# elk-board.net
KiCad netlist of a schematic drawn in EAGLE
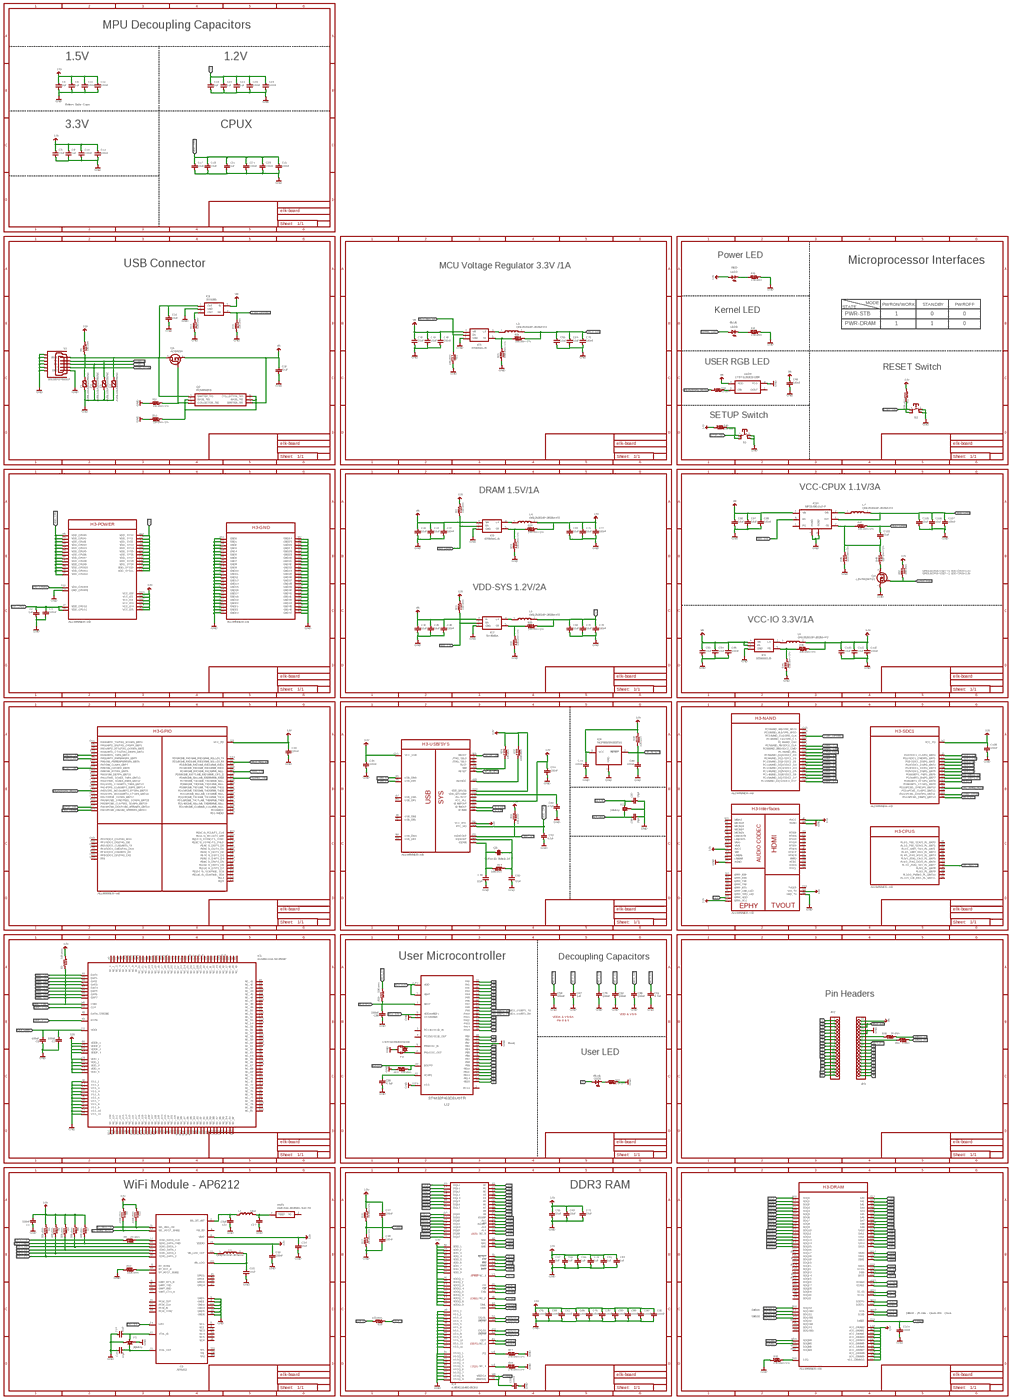
[diagram p0: schematic, sheet 1, overview]
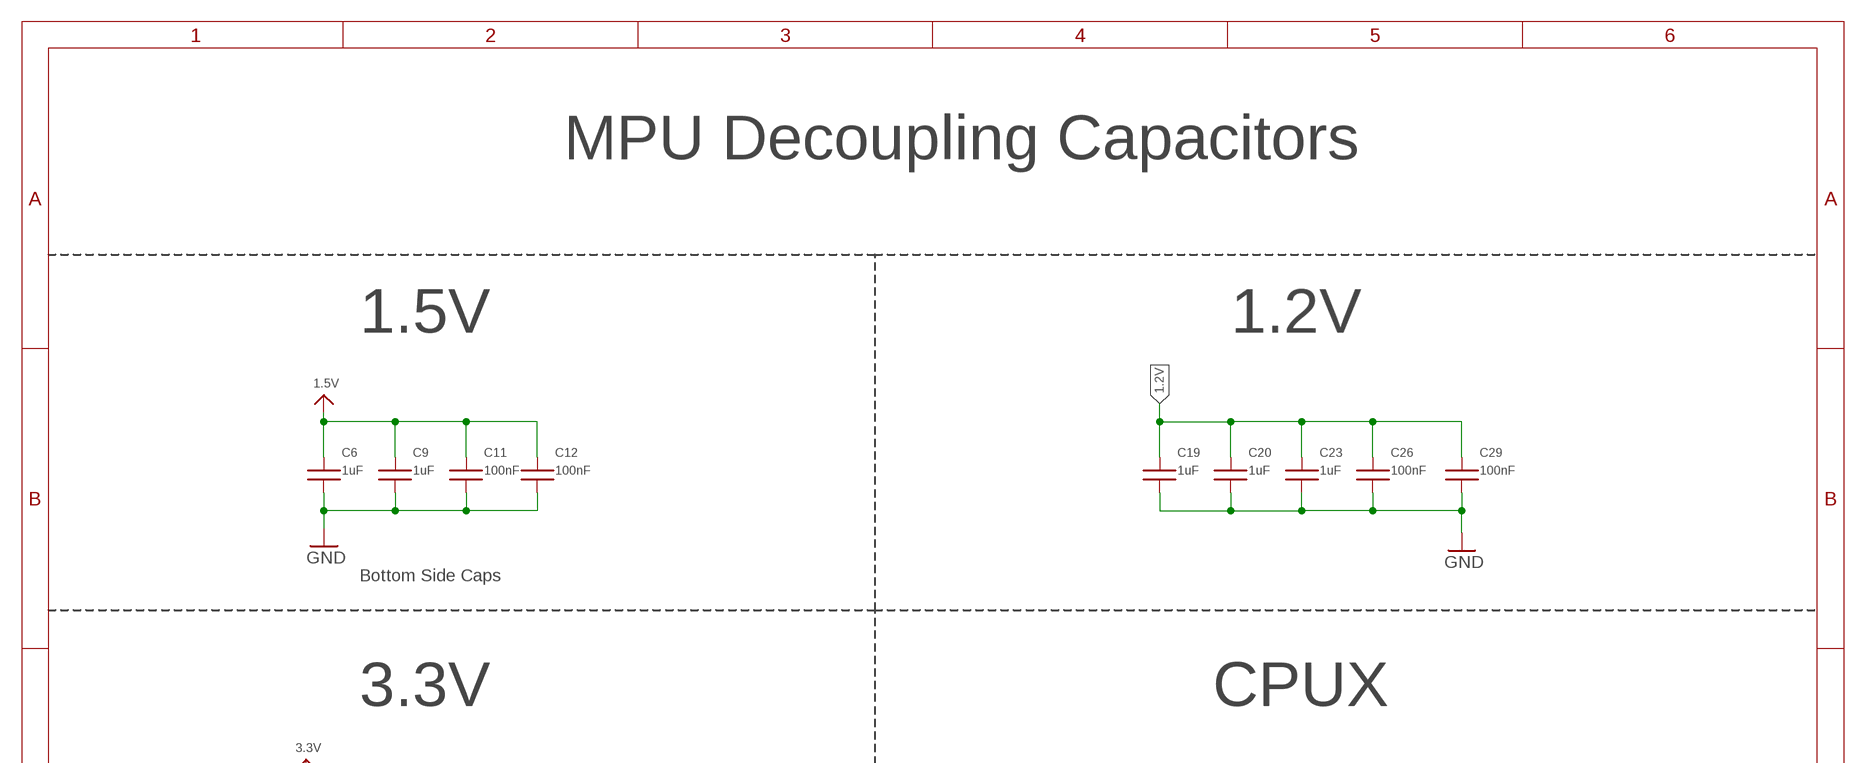
[diagram p1: schematic, sheet 1, part 1 of 7]
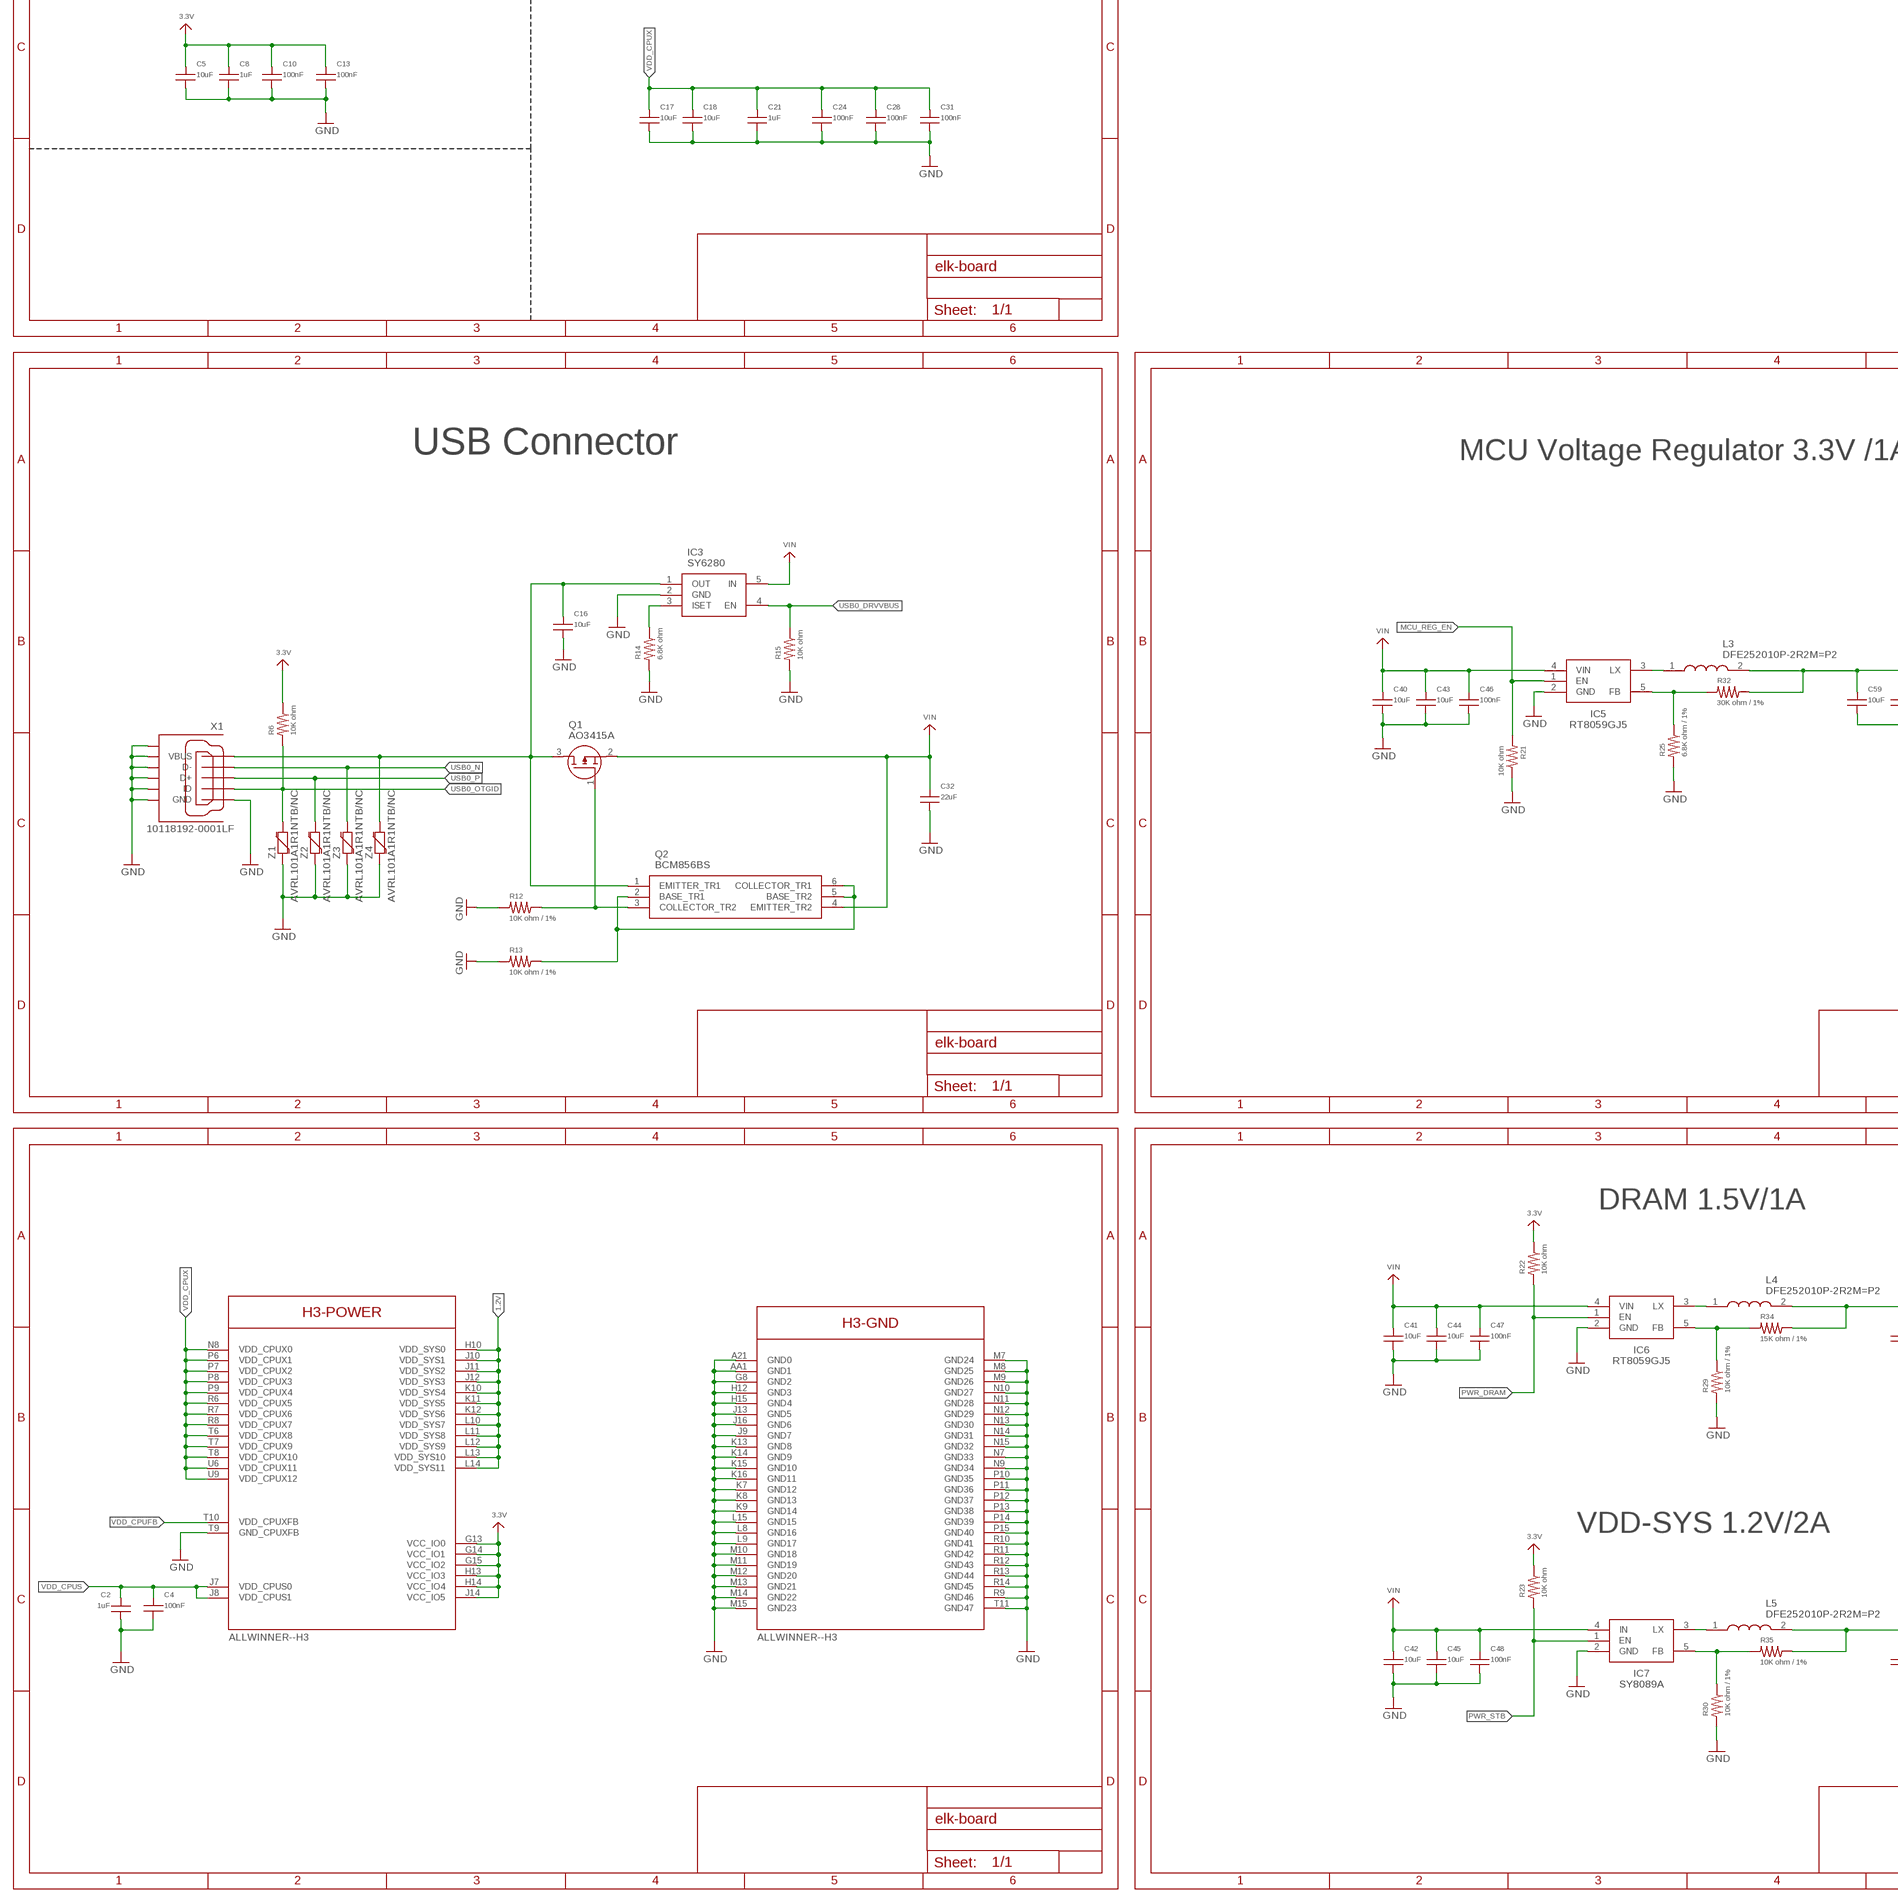
[diagram p2: schematic, sheet 1, part 2 of 7]
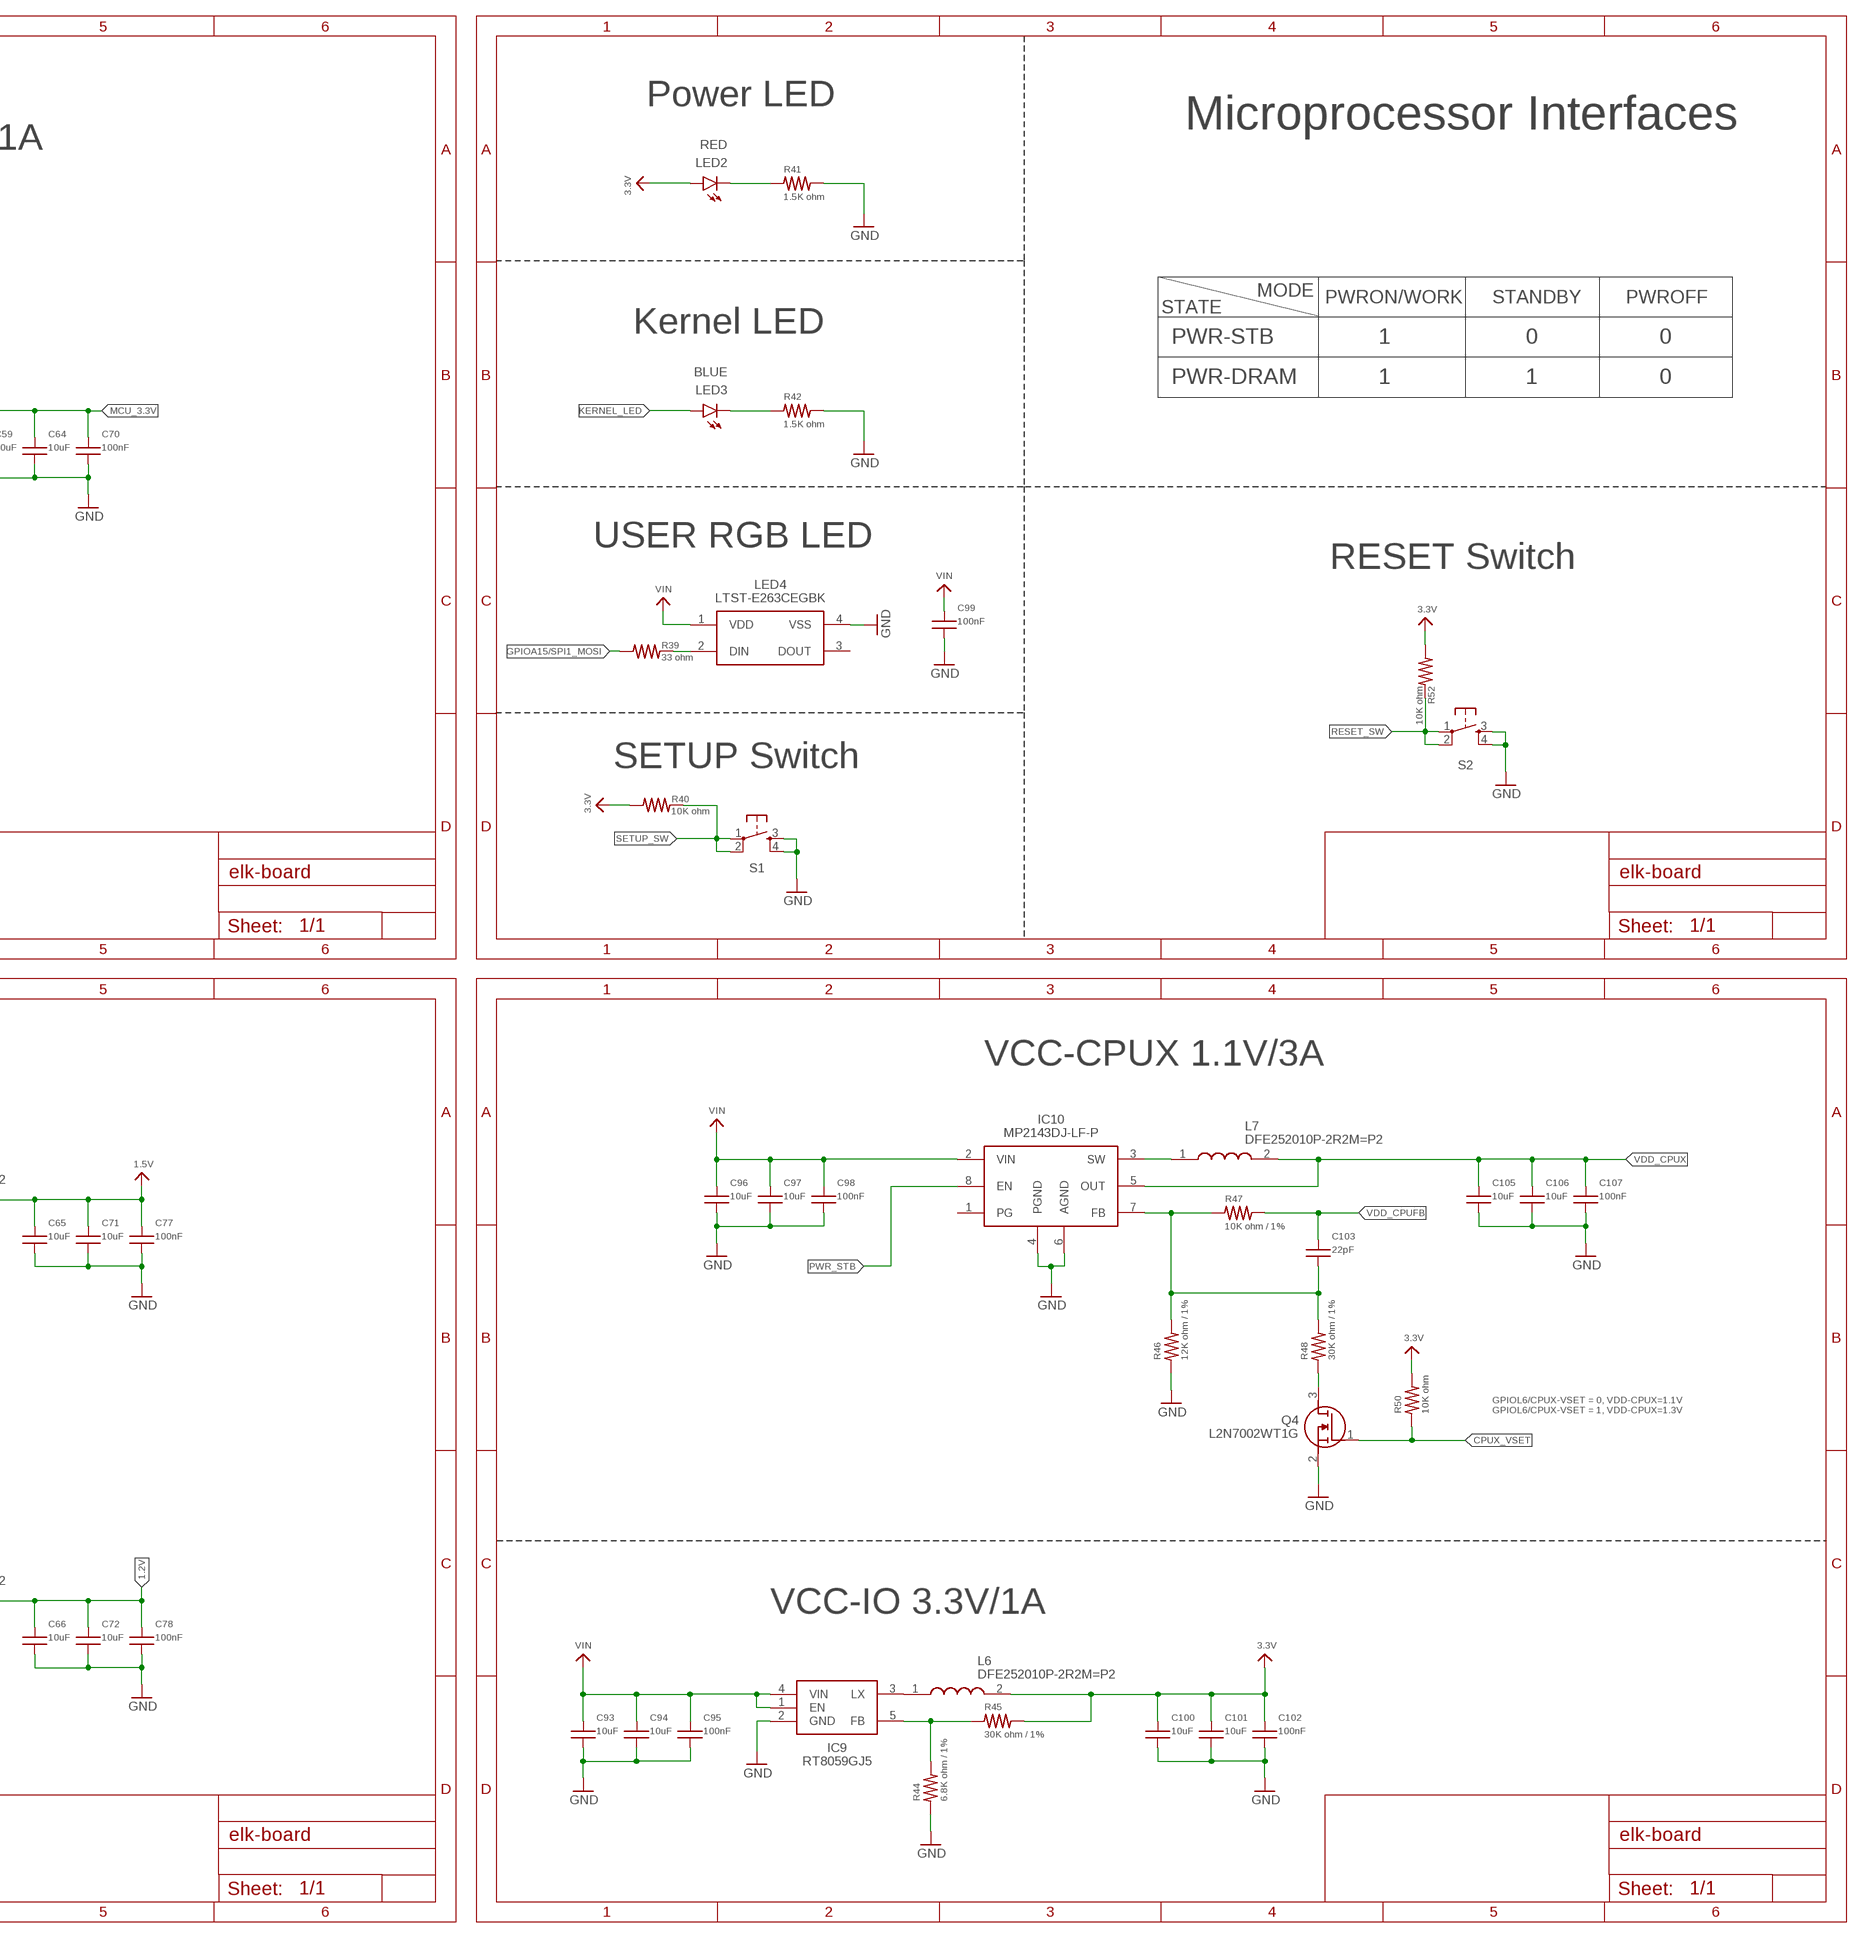
[diagram p3: schematic, sheet 1, part 3 of 7]
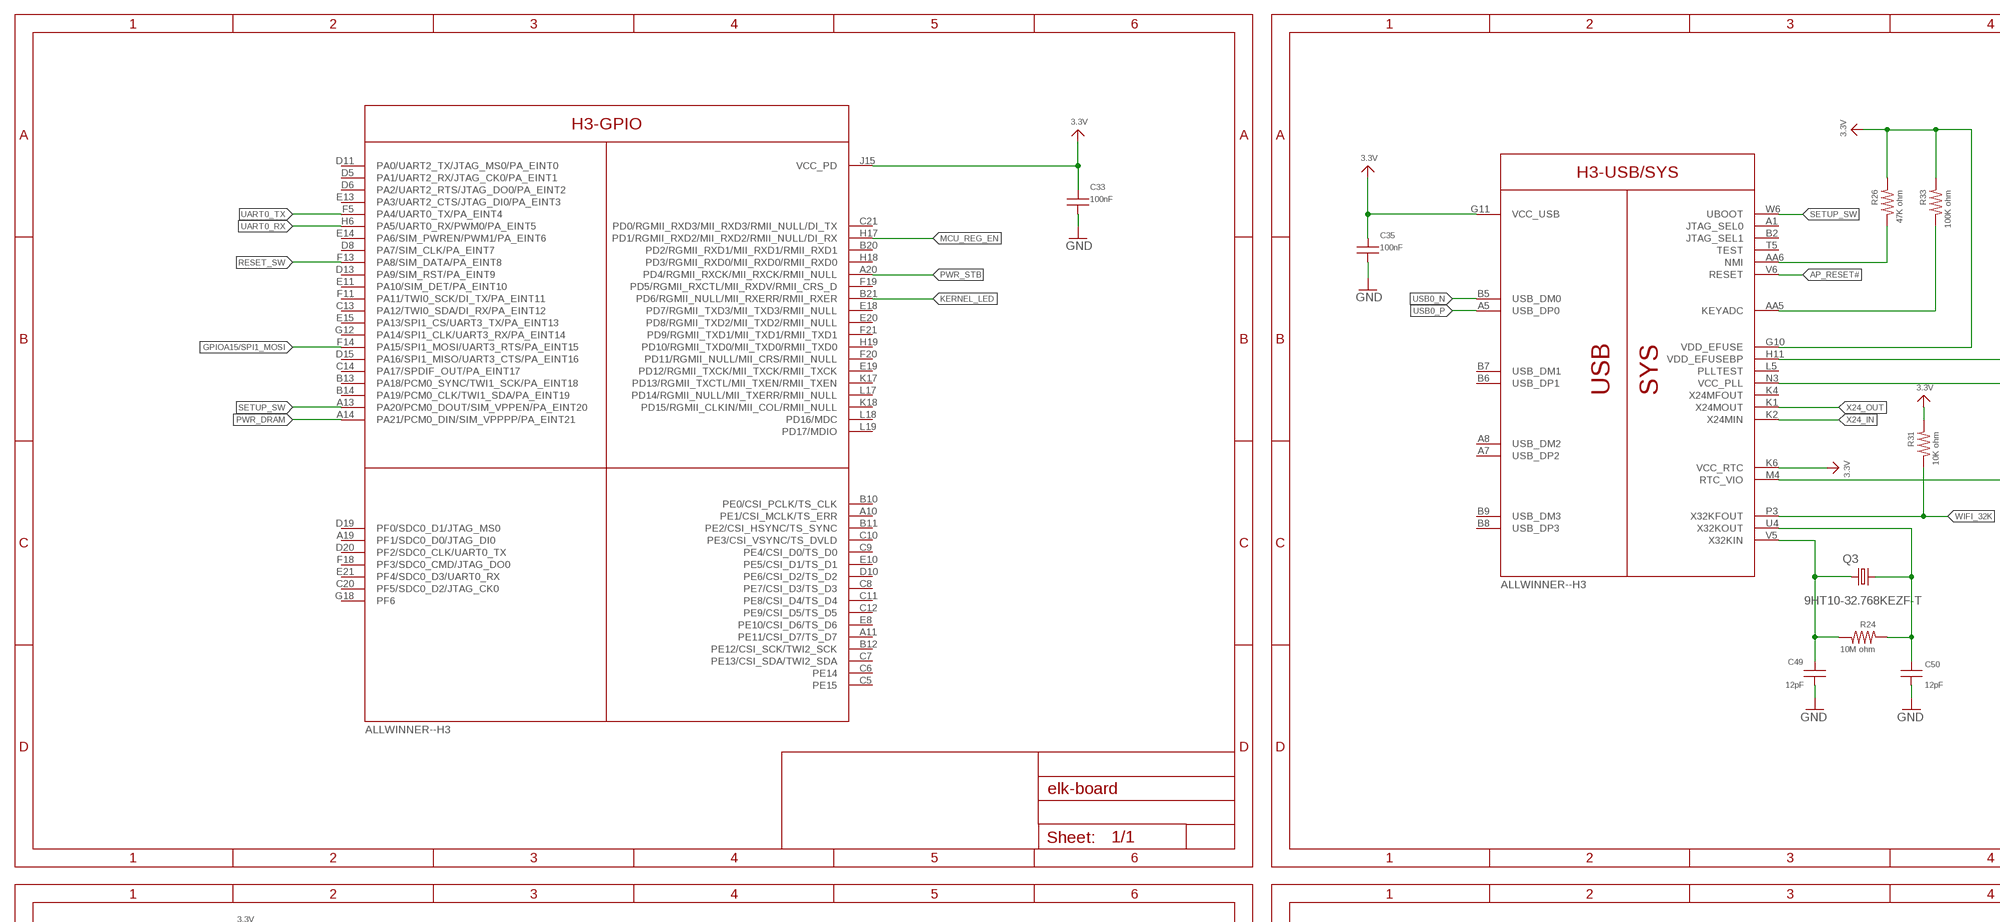
[diagram p4: schematic, sheet 1, part 4 of 7]
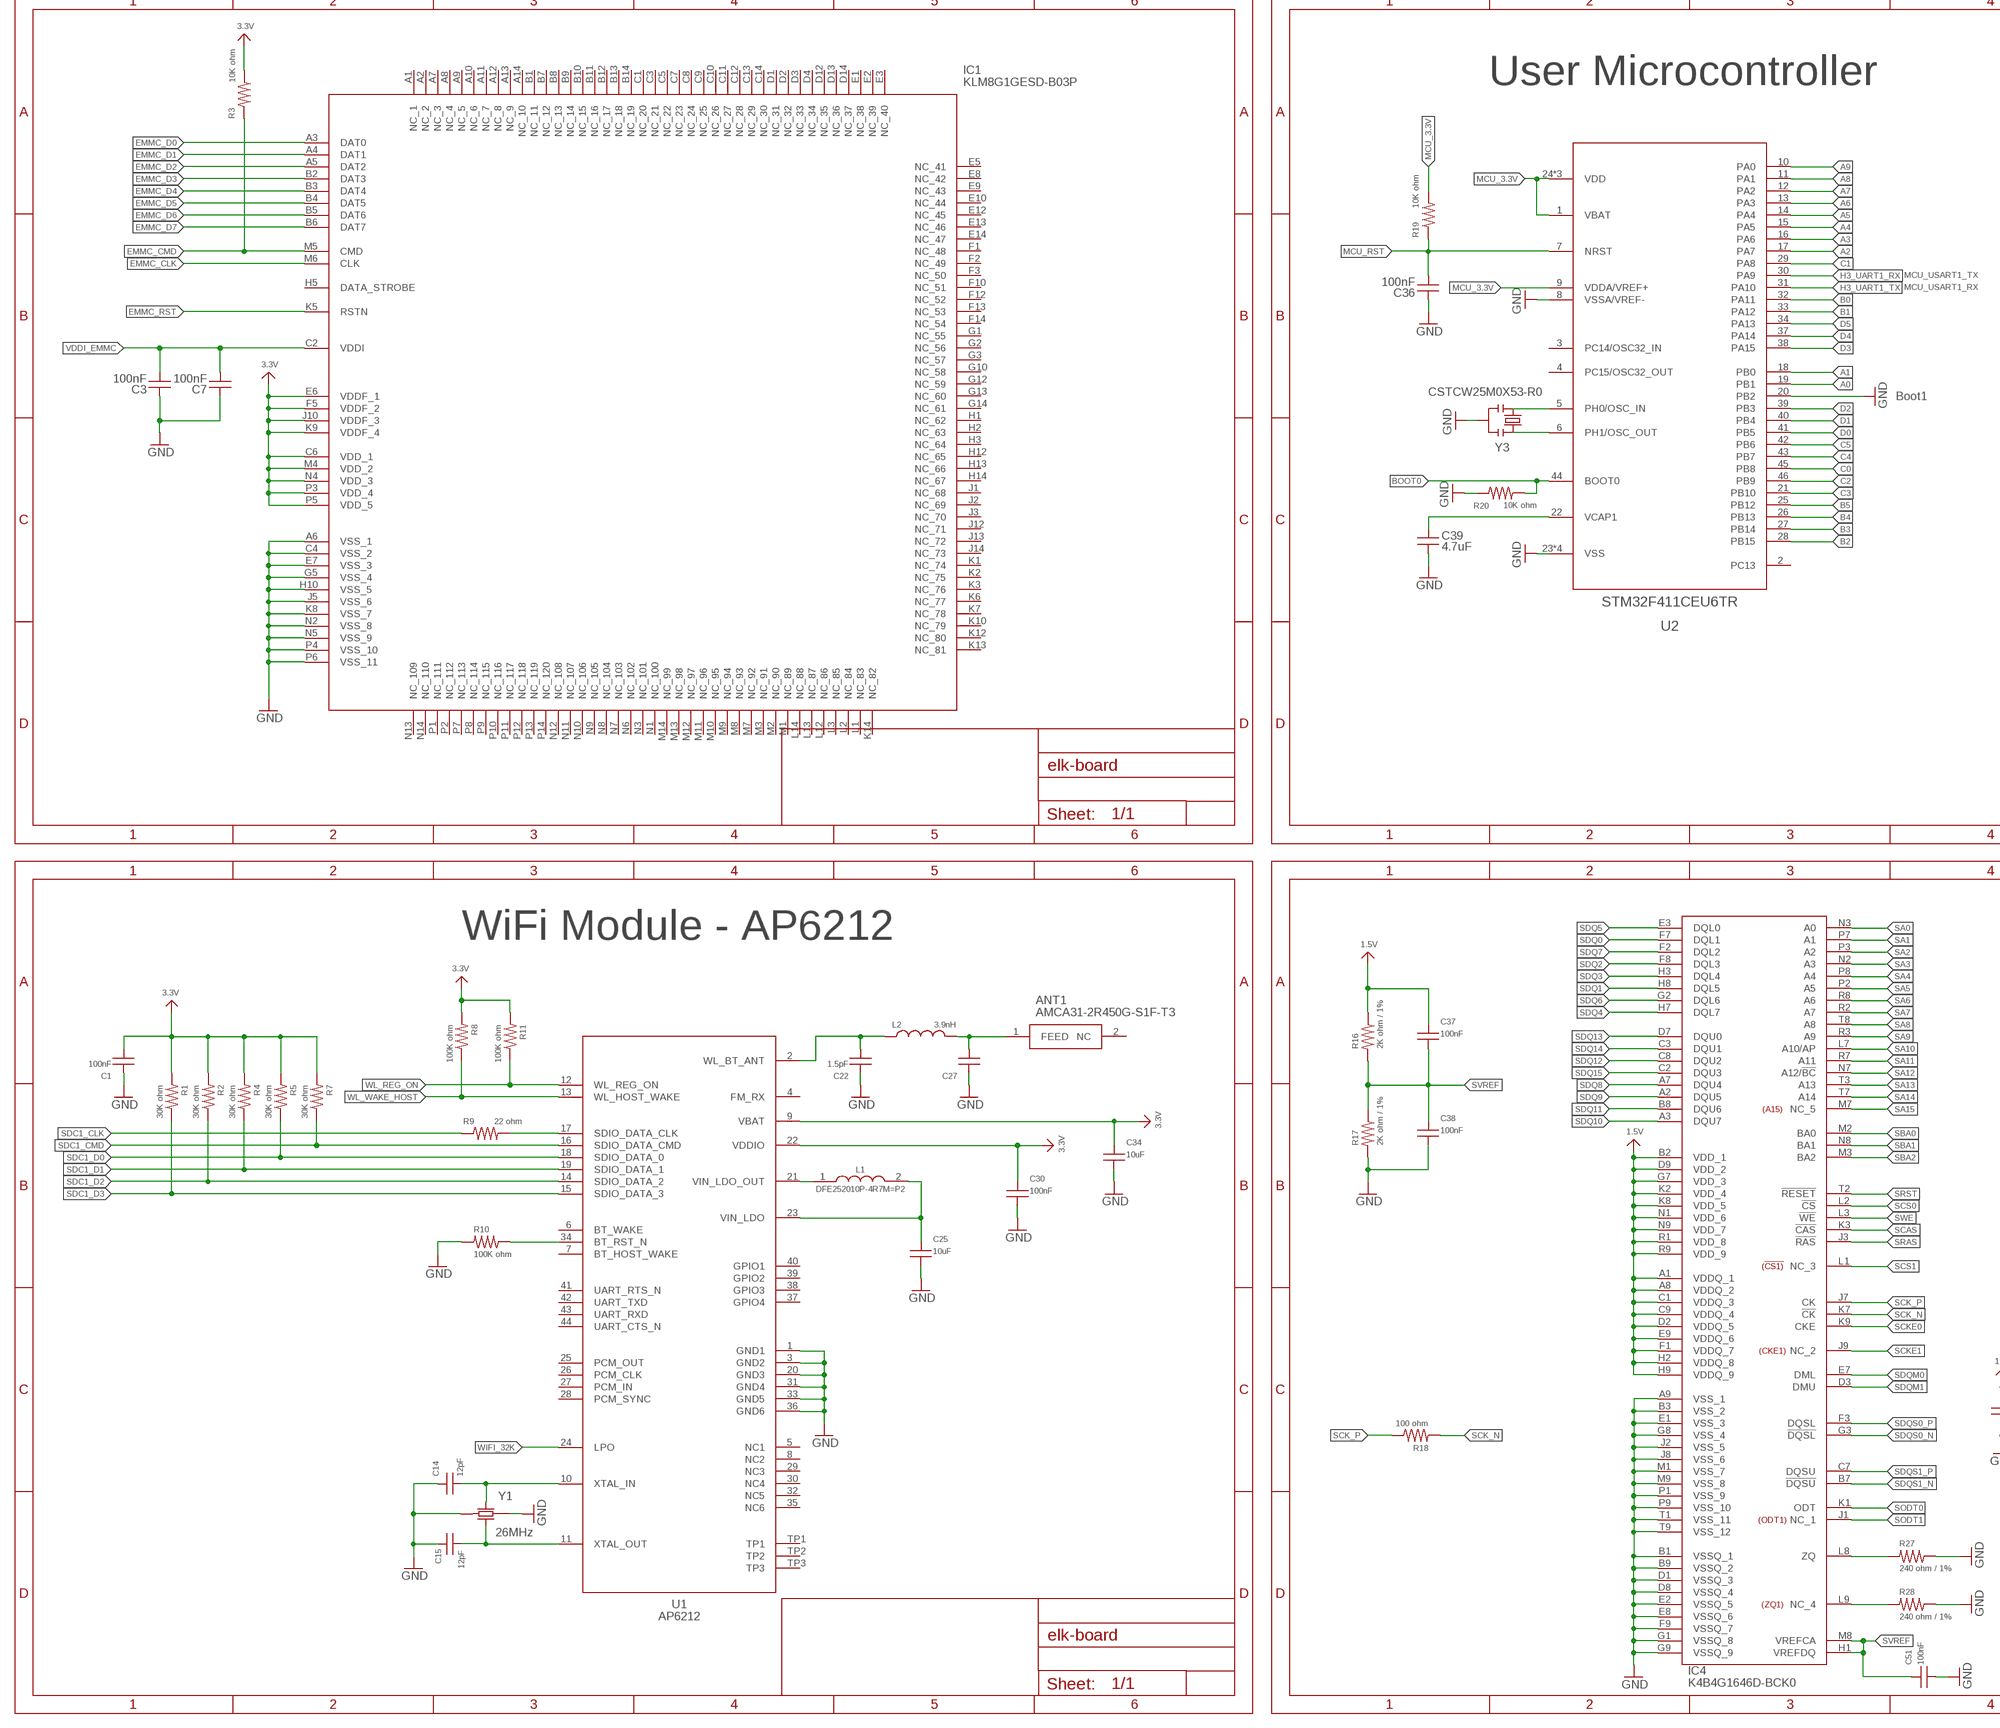
[diagram p5: schematic, sheet 1, part 5 of 7]
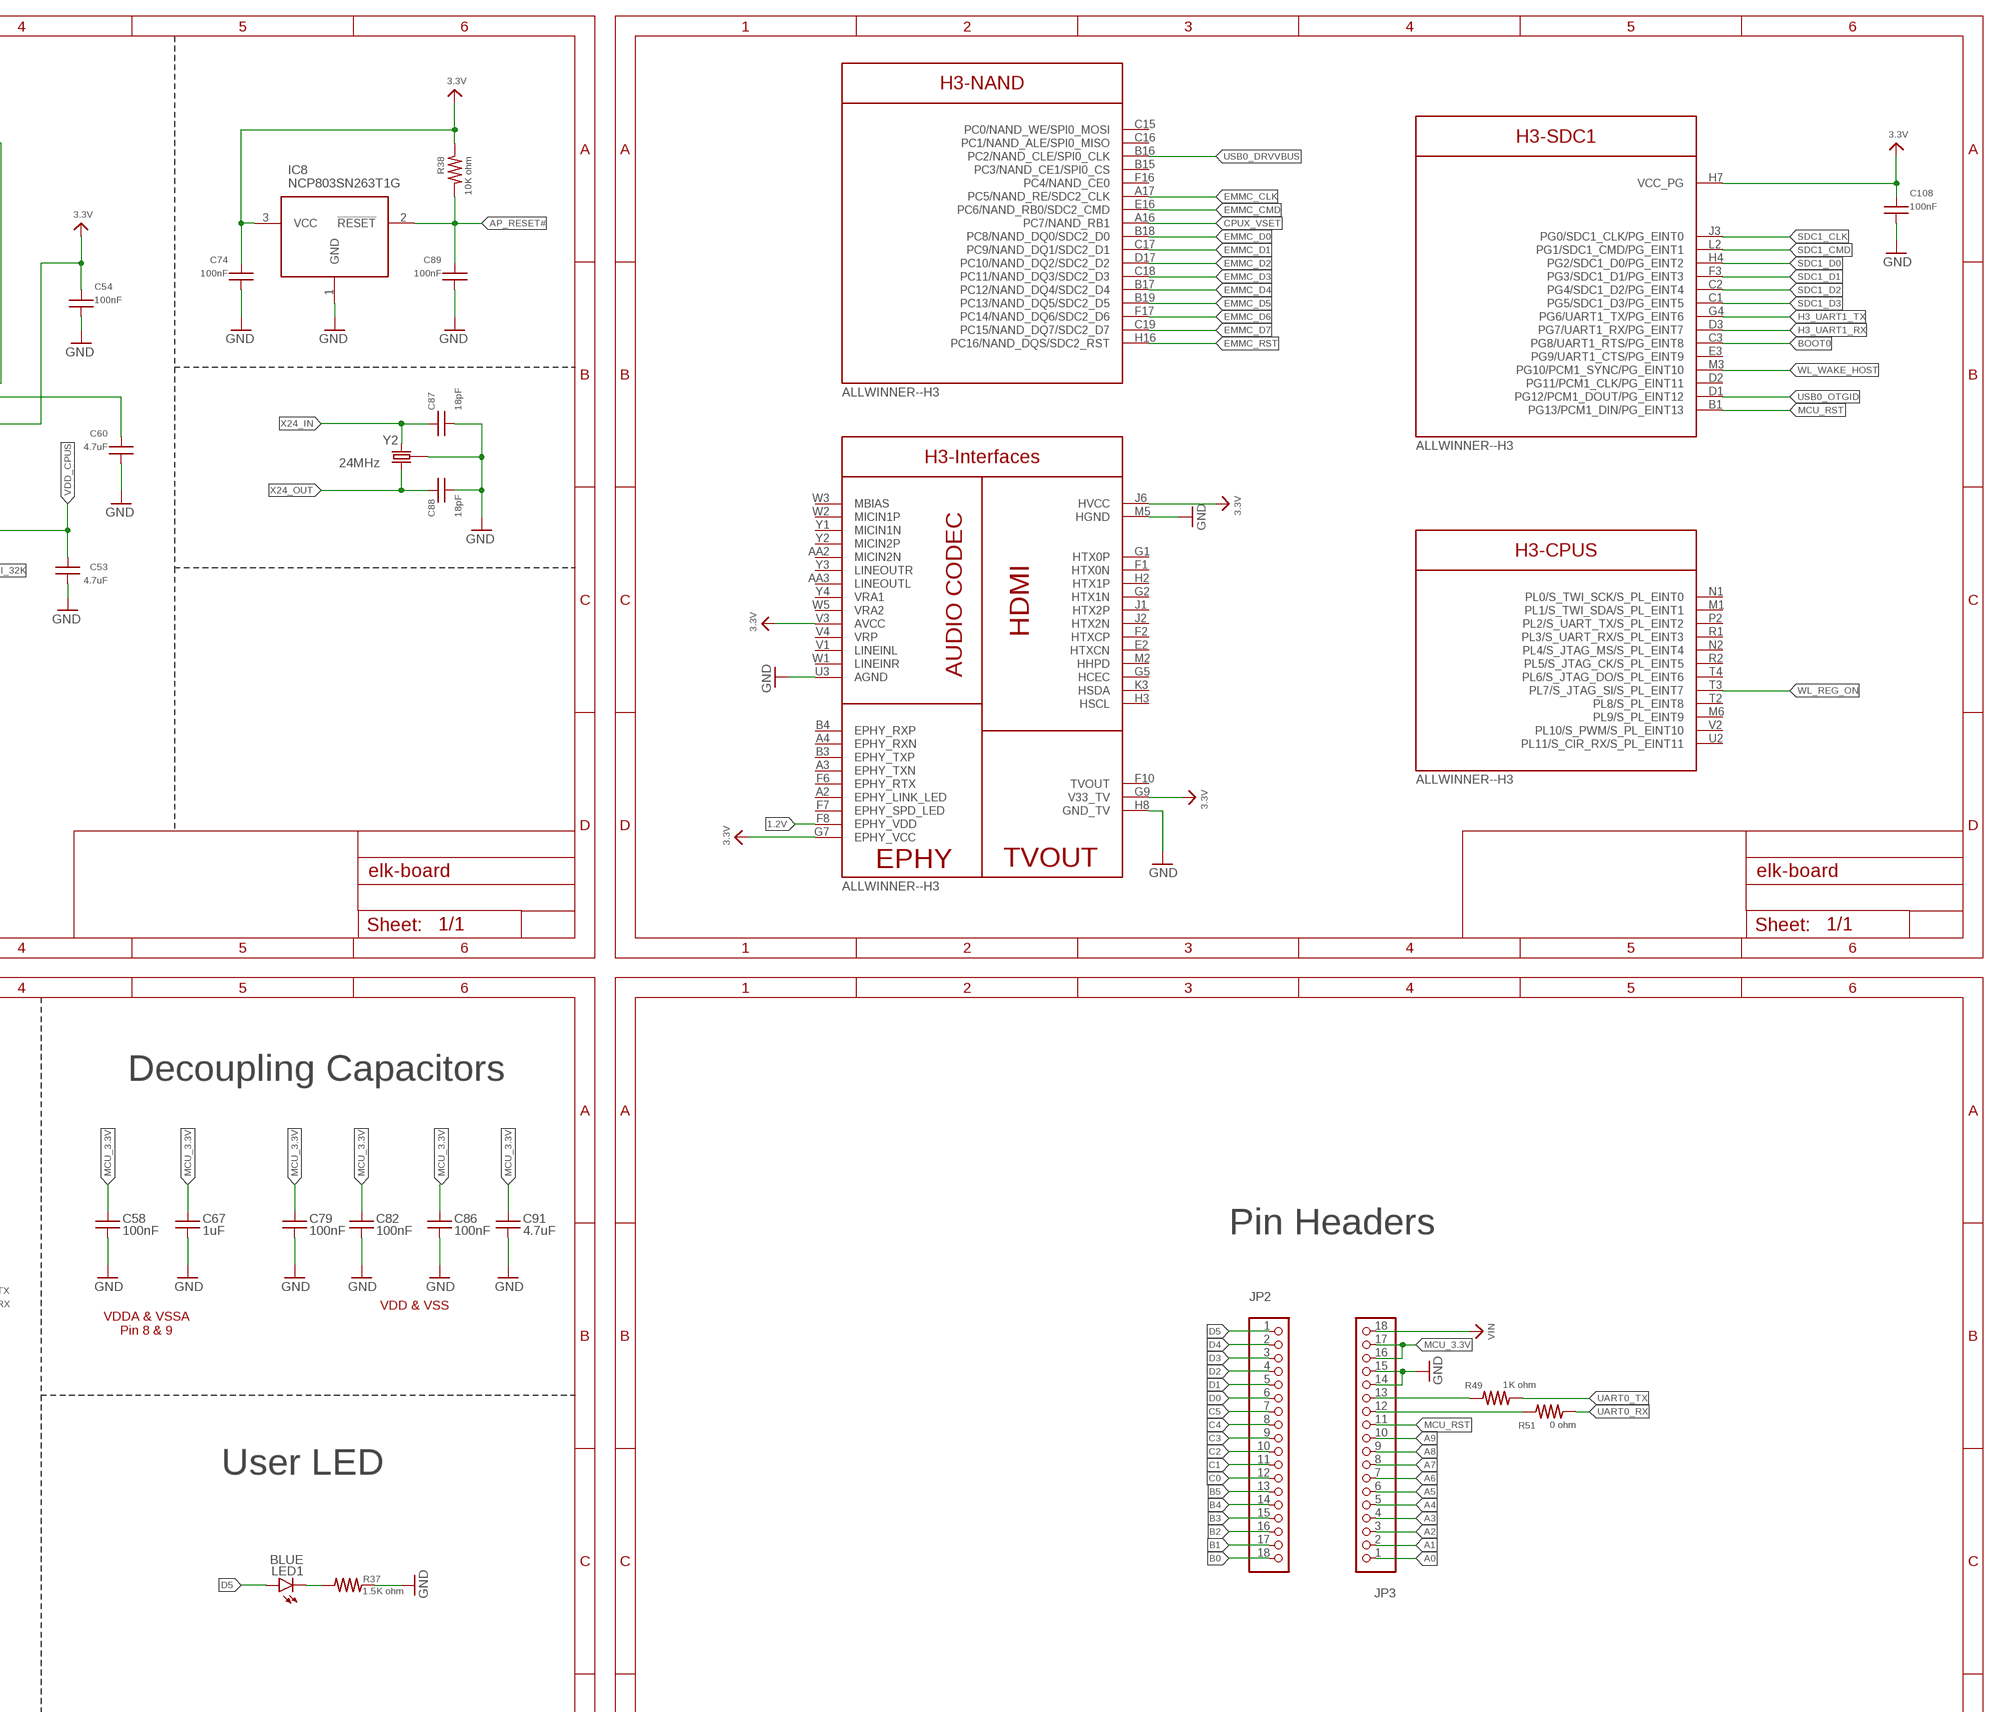
[diagram p6: schematic, sheet 1, part 6 of 7]
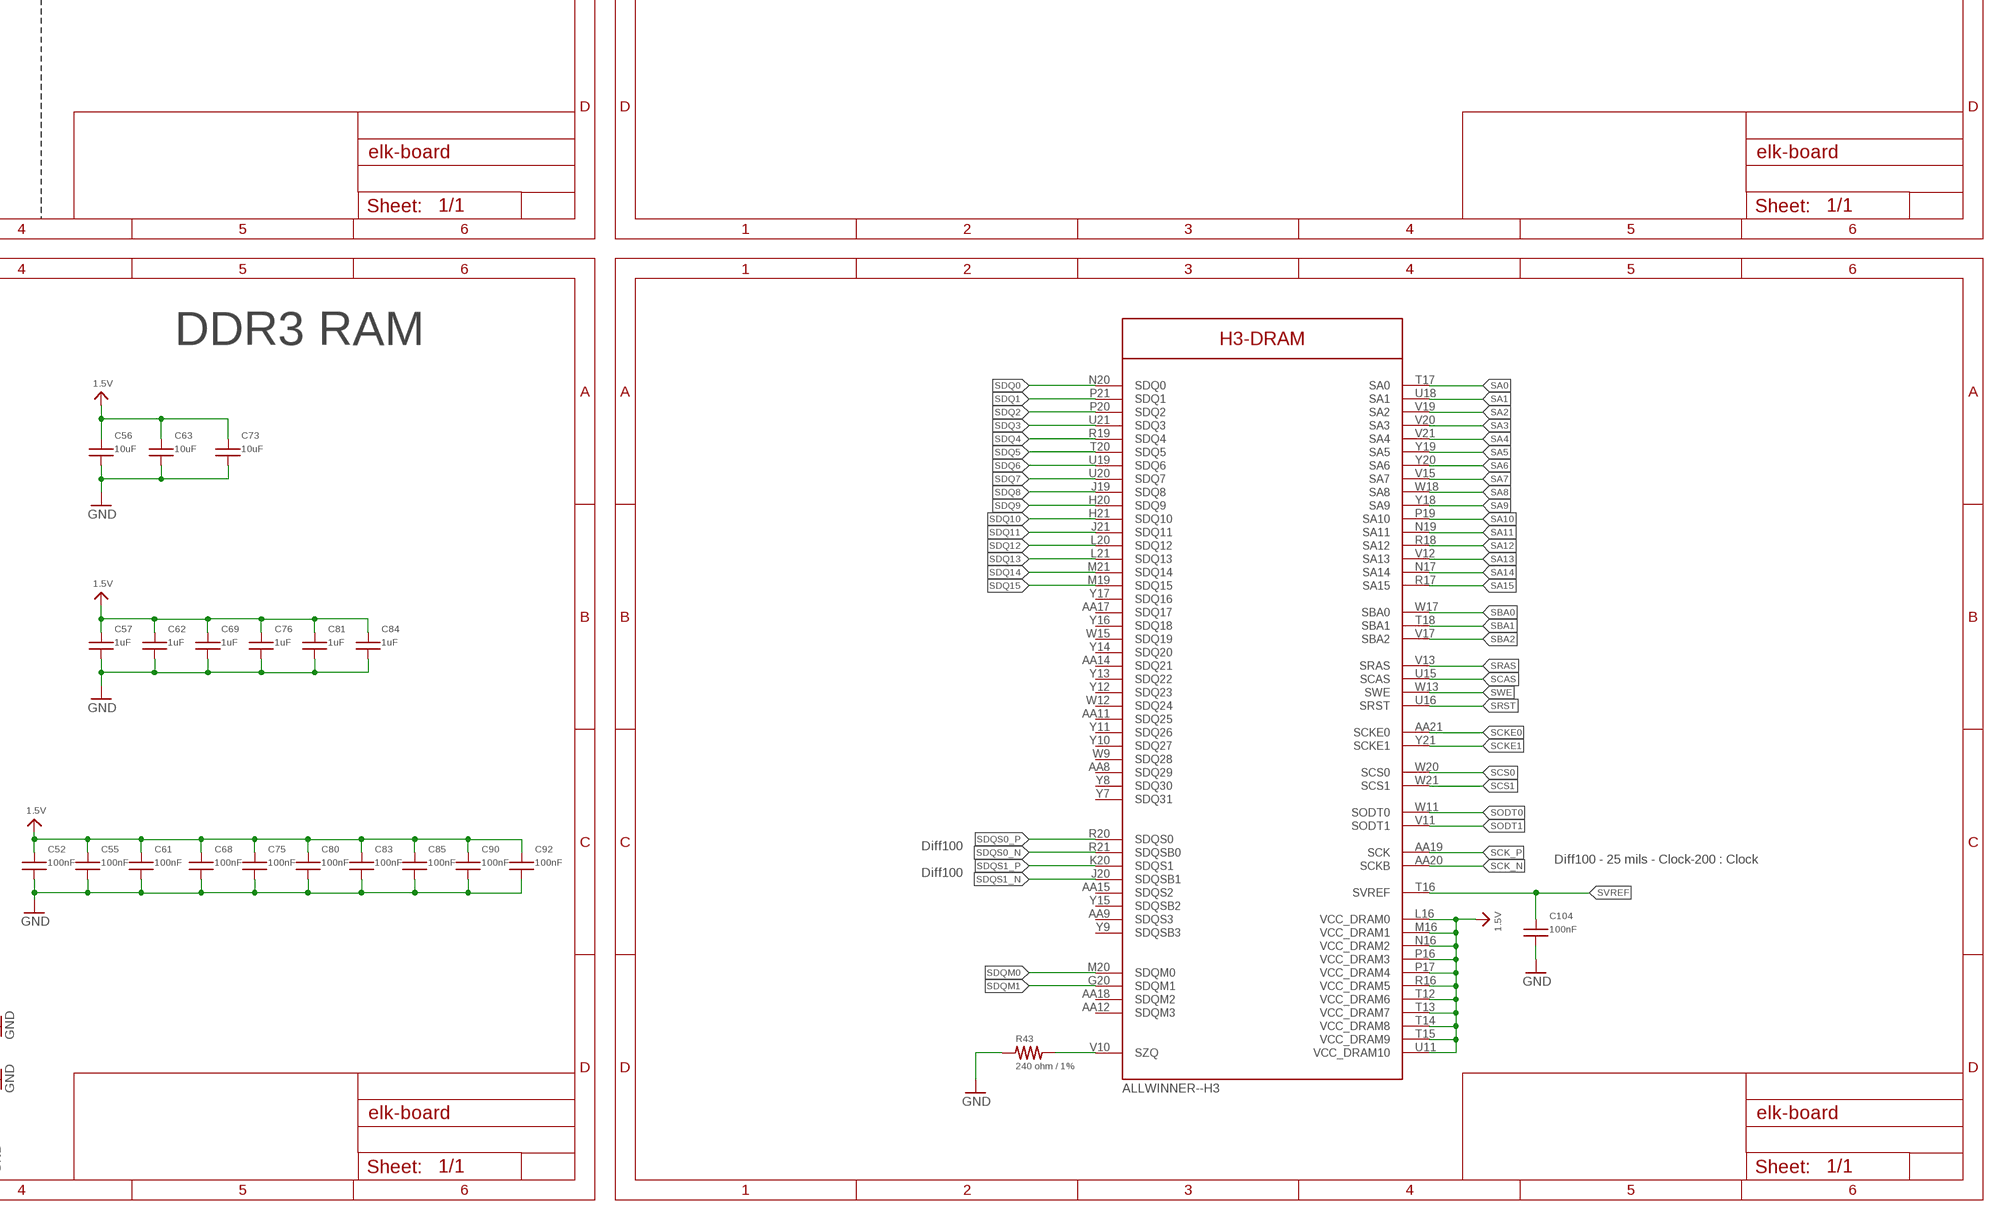
[diagram p7: schematic, sheet 1, part 7 of 7]

(export (version "E")
  (design (tool "Eeschema 10.0.6"))
  (components
    (comp (ref "ANT1")
      (value "AMCA31-2R450G-S1F-T3")
      (footprint "eagle-import:ANTC3216X140N")
      (fields (field (name "MOUSER_PART_NUMBER") "815-CA312R450GS1FT3"))
      (libsource (lib "eagle-import") (part "AMCA31-2R450G-S1F-T3"))
    )
    (comp (ref "C1")
      (value "100nF")
      (footprint "eagle-import:0402")
      (libsource (lib "eagle-import") (part "CAPACITOR-(INCH)-0402"))
    )
    (comp (ref "C2")
      (value "1uF")
      (footprint "eagle-import:0402")
      (libsource (lib "eagle-import") (part "CAPACITOR-(INCH)-0402"))
    )
    (comp (ref "C3")
      (value "100nF")
      (footprint "eagle-import:0402")
      (libsource (lib "eagle-import") (part "CAPACITOR-(INCH)-0402"))
    )
    (comp (ref "C4")
      (value "100nF")
      (footprint "eagle-import:0402")
      (libsource (lib "eagle-import") (part "CAPACITOR-(INCH)-0402"))
    )
    (comp (ref "C5")
      (value "10uF")
      (footprint "eagle-import:0603")
      (libsource (lib "eagle-import") (part "CAPACITOR-(INCH)-0603"))
    )
    (comp (ref "C6")
      (value "1uF")
      (footprint "eagle-import:0402")
      (libsource (lib "eagle-import") (part "CAPACITOR-(INCH)-0402"))
    )
    (comp (ref "C7")
      (value "100nF")
      (footprint "eagle-import:0402")
      (libsource (lib "eagle-import") (part "CAPACITOR-(INCH)-0402"))
    )
    (comp (ref "C8")
      (value "1uF")
      (footprint "eagle-import:0402")
      (libsource (lib "eagle-import") (part "CAPACITOR-(INCH)-0402"))
    )
    (comp (ref "C9")
      (value "1uF")
      (footprint "eagle-import:0402")
      (libsource (lib "eagle-import") (part "CAPACITOR-(INCH)-0402"))
    )
    (comp (ref "C10")
      (value "100nF")
      (footprint "eagle-import:0402")
      (libsource (lib "eagle-import") (part "CAPACITOR-(INCH)-0402"))
    )
    (comp (ref "C11")
      (value "100nF")
      (footprint "eagle-import:0402")
      (libsource (lib "eagle-import") (part "CAPACITOR-(INCH)-0402"))
    )
    (comp (ref "C12")
      (value "100nF")
      (footprint "eagle-import:0402")
      (libsource (lib "eagle-import") (part "CAPACITOR-(INCH)-0402"))
    )
    (comp (ref "C13")
      (value "100nF")
      (footprint "eagle-import:0402")
      (libsource (lib "eagle-import") (part "CAPACITOR-(INCH)-0402"))
    )
    (comp (ref "C14")
      (value "12pF")
      (footprint "eagle-import:0402")
      (libsource (lib "eagle-import") (part "CAPACITOR-(INCH)-0402"))
    )
    (comp (ref "C15")
      (value "12pF")
      (footprint "eagle-import:0402")
      (libsource (lib "eagle-import") (part "CAPACITOR-(INCH)-0402"))
    )
    (comp (ref "C16")
      (value "10uF")
      (footprint "eagle-import:0603")
      (libsource (lib "eagle-import") (part "CAPACITOR-(INCH)-0603"))
    )
    (comp (ref "C17")
      (value "10uF")
      (footprint "eagle-import:TOLBA_0603")
      (libsource (lib "eagle-import") (part "TOLBA_CAP"))
    )
    (comp (ref "C18")
      (value "10uF")
      (footprint "eagle-import:TOLBA_0603")
      (libsource (lib "eagle-import") (part "TOLBA_CAP"))
    )
    (comp (ref "C19")
      (value "1uF")
      (footprint "eagle-import:0402")
      (libsource (lib "eagle-import") (part "CAPACITOR-(INCH)-0402"))
    )
    (comp (ref "C20")
      (value "1uF")
      (footprint "eagle-import:0402")
      (libsource (lib "eagle-import") (part "CAPACITOR-(INCH)-0402"))
    )
    (comp (ref "C21")
      (value "1uF")
      (footprint "eagle-import:0402")
      (libsource (lib "eagle-import") (part "CAPACITOR-(INCH)-0402"))
    )
    (comp (ref "C22")
      (value "1.5pF")
      (footprint "eagle-import:0402")
      (libsource (lib "eagle-import") (part "CAPACITOR-(INCH)-0402"))
    )
    (comp (ref "C23")
      (value "1uF")
      (footprint "eagle-import:0402")
      (libsource (lib "eagle-import") (part "CAPACITOR-(INCH)-0402"))
    )
    (comp (ref "C24")
      (value "100nF")
      (footprint "eagle-import:0402")
      (libsource (lib "eagle-import") (part "CAPACITOR-(INCH)-0402"))
    )
    (comp (ref "C25")
      (value "10uF")
      (footprint "eagle-import:0603")
      (libsource (lib "eagle-import") (part "CAPACITOR-(INCH)-0603"))
    )
    (comp (ref "C26")
      (value "100nF")
      (footprint "eagle-import:0402")
      (libsource (lib "eagle-import") (part "CAPACITOR-(INCH)-0402"))
    )
    (comp (ref "C27")
      (value "CAPACITOR-(INCH)-0402")
      (footprint "eagle-import:0402")
      (libsource (lib "eagle-import") (part "CAPACITOR-(INCH)-0402"))
    )
    (comp (ref "C28")
      (value "100nF")
      (footprint "eagle-import:0402")
      (libsource (lib "eagle-import") (part "CAPACITOR-(INCH)-0402"))
    )
    (comp (ref "C29")
      (value "100nF")
      (footprint "eagle-import:0402")
      (libsource (lib "eagle-import") (part "CAPACITOR-(INCH)-0402"))
    )
    (comp (ref "C30")
      (value "100nF")
      (footprint "eagle-import:0402")
      (libsource (lib "eagle-import") (part "CAPACITOR-(INCH)-0402"))
    )
    (comp (ref "C31")
      (value "100nF")
      (footprint "eagle-import:0402")
      (libsource (lib "eagle-import") (part "CAPACITOR-(INCH)-0402"))
    )
    (comp (ref "C32")
      (value "22uF")
      (footprint "eagle-import:0603")
      (libsource (lib "eagle-import") (part "CAPACITOR-(INCH)-0603"))
    )
    (comp (ref "C33")
      (value "100nF")
      (footprint "eagle-import:0402")
      (libsource (lib "eagle-import") (part "CAPACITOR-(INCH)-0402"))
    )
    (comp (ref "C34")
      (value "10uF")
      (footprint "eagle-import:0603")
      (libsource (lib "eagle-import") (part "CAPACITOR-(INCH)-0603"))
    )
    (comp (ref "C35")
      (value "100nF")
      (footprint "eagle-import:0402")
      (libsource (lib "eagle-import") (part "CAPACITOR-(INCH)-0402"))
    )
    (comp (ref "C36")
      (value "100nF")
      (footprint "eagle-import:0402")
      (libsource (lib "eagle-import") (part "CAPACITOR-(INCH)-0402"))
    )
    (comp (ref "C37")
      (value "100nF")
      (footprint "eagle-import:0402")
      (libsource (lib "eagle-import") (part "CAPACITOR-(INCH)-0402"))
    )
    (comp (ref "C38")
      (value "100nF")
      (footprint "eagle-import:0402")
      (libsource (lib "eagle-import") (part "CAPACITOR-(INCH)-0402"))
    )
    (comp (ref "C39")
      (value "4.7uF")
      (footprint "eagle-import:0402")
      (libsource (lib "eagle-import") (part "CAPACITOR-(INCH)-0402"))
    )
    (comp (ref "C40")
      (value "10uF")
      (footprint "eagle-import:0603")
      (libsource (lib "eagle-import") (part "CAPACITOR-(INCH)-0603"))
    )
    (comp (ref "C41")
      (value "10uF")
      (footprint "eagle-import:0603")
      (libsource (lib "eagle-import") (part "CAPACITOR-(INCH)-0603"))
    )
    (comp (ref "C42")
      (value "10uF")
      (footprint "eagle-import:0603")
      (libsource (lib "eagle-import") (part "CAPACITOR-(INCH)-0603"))
    )
    (comp (ref "C43")
      (value "10uF")
      (footprint "eagle-import:0603")
      (libsource (lib "eagle-import") (part "CAPACITOR-(INCH)-0603"))
    )
    (comp (ref "C44")
      (value "10uF")
      (footprint "eagle-import:0603")
      (libsource (lib "eagle-import") (part "CAPACITOR-(INCH)-0603"))
    )
    (comp (ref "C45")
      (value "10uF")
      (footprint "eagle-import:0603")
      (libsource (lib "eagle-import") (part "CAPACITOR-(INCH)-0603"))
    )
    (comp (ref "C46")
      (value "100nF")
      (footprint "eagle-import:0402")
      (libsource (lib "eagle-import") (part "CAPACITOR-(INCH)-0402"))
    )
    (comp (ref "C47")
      (value "100nF")
      (footprint "eagle-import:0402")
      (libsource (lib "eagle-import") (part "CAPACITOR-(INCH)-0402"))
    )
    (comp (ref "C48")
      (value "100nF")
      (footprint "eagle-import:0402")
      (libsource (lib "eagle-import") (part "CAPACITOR-(INCH)-0402"))
    )
    (comp (ref "C49")
      (value "12pF")
      (footprint "eagle-import:0402")
      (libsource (lib "eagle-import") (part "CAPACITOR-(INCH)-0402"))
    )
    (comp (ref "C50")
      (value "12pF")
      (footprint "eagle-import:0402")
      (libsource (lib "eagle-import") (part "CAPACITOR-(INCH)-0402"))
    )
    (comp (ref "C51")
      (value "100nF")
      (footprint "eagle-import:0402")
      (libsource (lib "eagle-import") (part "CAPACITOR-(INCH)-0402"))
    )
    (comp (ref "C52")
      (value "100nF")
      (footprint "eagle-import:0402")
      (libsource (lib "eagle-import") (part "CAPACITOR-(INCH)-0402"))
    )
    (comp (ref "C53")
      (value "4.7uF")
      (footprint "eagle-import:0402")
      (libsource (lib "eagle-import") (part "CAPACITOR-(INCH)-0402"))
    )
    (comp (ref "C54")
      (value "100nF")
      (footprint "eagle-import:0402")
      (libsource (lib "eagle-import") (part "CAPACITOR-(INCH)-0402"))
    )
    (comp (ref "C55")
      (value "100nF")
      (footprint "eagle-import:0402")
      (libsource (lib "eagle-import") (part "CAPACITOR-(INCH)-0402"))
    )
    (comp (ref "C56")
      (value "10uF")
      (footprint "eagle-import:0603")
      (libsource (lib "eagle-import") (part "CAPACITOR-(INCH)-0603"))
    )
    (comp (ref "C57")
      (value "1uF")
      (footprint "eagle-import:0402")
      (libsource (lib "eagle-import") (part "CAPACITOR-(INCH)-0402"))
    )
    (comp (ref "C58")
      (value "100nF")
      (footprint "eagle-import:0402")
      (libsource (lib "eagle-import") (part "CAPACITOR-(INCH)-0402"))
    )
    (comp (ref "C59")
      (value "10uF")
      (footprint "eagle-import:0603")
      (libsource (lib "eagle-import") (part "CAPACITOR-(INCH)-0603"))
    )
    (comp (ref "C60")
      (value "4.7uF")
      (footprint "eagle-import:0402")
      (libsource (lib "eagle-import") (part "CAPACITOR-(INCH)-0402"))
    )
    (comp (ref "C61")
      (value "100nF")
      (footprint "eagle-import:0402")
      (libsource (lib "eagle-import") (part "CAPACITOR-(INCH)-0402"))
    )
    (comp (ref "C62")
      (value "1uF")
      (footprint "eagle-import:0402")
      (libsource (lib "eagle-import") (part "CAPACITOR-(INCH)-0402"))
    )
    (comp (ref "C63")
      (value "10uF")
      (footprint "eagle-import:0603")
      (libsource (lib "eagle-import") (part "CAPACITOR-(INCH)-0603"))
    )
    (comp (ref "C64")
      (value "10uF")
      (footprint "eagle-import:0603")
      (libsource (lib "eagle-import") (part "CAPACITOR-(INCH)-0603"))
    )
    (comp (ref "C65")
      (value "10uF")
      (footprint "eagle-import:0603")
      (libsource (lib "eagle-import") (part "CAPACITOR-(INCH)-0603"))
    )
    (comp (ref "C66")
      (value "10uF")
      (footprint "eagle-import:0603")
      (libsource (lib "eagle-import") (part "CAPACITOR-(INCH)-0603"))
    )
    (comp (ref "C67")
      (value "1uF")
      (footprint "eagle-import:0402")
      (libsource (lib "eagle-import") (part "CAPACITOR-(INCH)-0402"))
    )
    (comp (ref "C68")
      (value "100nF")
      (footprint "eagle-import:0402")
      (libsource (lib "eagle-import") (part "CAPACITOR-(INCH)-0402"))
    )
    (comp (ref "C69")
      (value "1uF")
      (footprint "eagle-import:0402")
      (libsource (lib "eagle-import") (part "CAPACITOR-(INCH)-0402"))
    )
    (comp (ref "C70")
      (value "100nF")
      (footprint "eagle-import:0402")
      (libsource (lib "eagle-import") (part "CAPACITOR-(INCH)-0402"))
    )
    (comp (ref "C71")
      (value "10uF")
      (footprint "eagle-import:0603")
      (libsource (lib "eagle-import") (part "CAPACITOR-(INCH)-0603"))
    )
    (comp (ref "C72")
      (value "10uF")
      (footprint "eagle-import:0603")
      (libsource (lib "eagle-import") (part "CAPACITOR-(INCH)-0603"))
    )
    (comp (ref "C73")
      (value "10uF")
      (footprint "eagle-import:0603")
      (libsource (lib "eagle-import") (part "CAPACITOR-(INCH)-0603"))
    )
    (comp (ref "C74")
      (value "100nF")
      (footprint "eagle-import:0402")
      (libsource (lib "eagle-import") (part "CAPACITOR-(INCH)-0402"))
    )
    (comp (ref "C75")
      (value "100nF")
      (footprint "eagle-import:0402")
      (libsource (lib "eagle-import") (part "CAPACITOR-(INCH)-0402"))
    )
    (comp (ref "C76")
      (value "1uF")
      (footprint "eagle-import:0402")
      (libsource (lib "eagle-import") (part "CAPACITOR-(INCH)-0402"))
    )
    (comp (ref "C77")
      (value "100nF")
      (footprint "eagle-import:0402")
      (libsource (lib "eagle-import") (part "CAPACITOR-(INCH)-0402"))
    )
    (comp (ref "C78")
      (value "100nF")
      (footprint "eagle-import:0402")
      (libsource (lib "eagle-import") (part "CAPACITOR-(INCH)-0402"))
    )
    (comp (ref "C79")
      (value "100nF")
      (footprint "eagle-import:0402")
      (libsource (lib "eagle-import") (part "CAPACITOR-(INCH)-0402"))
    )
    (comp (ref "C80")
      (value "100nF")
      (footprint "eagle-import:0402")
      (libsource (lib "eagle-import") (part "CAPACITOR-(INCH)-0402"))
    )
    (comp (ref "C81")
      (value "1uF")
      (footprint "eagle-import:0402")
      (libsource (lib "eagle-import") (part "CAPACITOR-(INCH)-0402"))
    )
    (comp (ref "C82")
      (value "100nF")
      (footprint "eagle-import:0402")
      (libsource (lib "eagle-import") (part "CAPACITOR-(INCH)-0402"))
    )
    (comp (ref "C83")
      (value "100nF")
      (footprint "eagle-import:0402")
      (libsource (lib "eagle-import") (part "CAPACITOR-(INCH)-0402"))
    )
    (comp (ref "C84")
      (value "1uF")
      (footprint "eagle-import:0402")
      (libsource (lib "eagle-import") (part "CAPACITOR-(INCH)-0402"))
    )
    (comp (ref "C85")
      (value "100nF")
      (footprint "eagle-import:0402")
      (libsource (lib "eagle-import") (part "CAPACITOR-(INCH)-0402"))
    )
    (comp (ref "C86")
      (value "100nF")
      (footprint "eagle-import:0402")
      (libsource (lib "eagle-import") (part "CAPACITOR-(INCH)-0402"))
    )
    (comp (ref "C87")
      (value "18pF")
      (footprint "eagle-import:0402")
      (libsource (lib "eagle-import") (part "CAPACITOR-(INCH)-0402"))
    )
    (comp (ref "C88")
      (value "18pF")
      (footprint "eagle-import:0402")
      (libsource (lib "eagle-import") (part "CAPACITOR-(INCH)-0402"))
    )
    (comp (ref "C89")
      (value "100nF")
      (footprint "eagle-import:0402")
      (libsource (lib "eagle-import") (part "CAPACITOR-(INCH)-0402"))
    )
    (comp (ref "C90")
      (value "100nF")
      (footprint "eagle-import:0402")
      (libsource (lib "eagle-import") (part "CAPACITOR-(INCH)-0402"))
    )
    (comp (ref "C91")
      (value "4.7uF")
      (footprint "eagle-import:0402")
      (libsource (lib "eagle-import") (part "CAPACITOR-(INCH)-0402"))
    )
    (comp (ref "C92")
      (value "100nF")
      (footprint "eagle-import:0402")
      (libsource (lib "eagle-import") (part "CAPACITOR-(INCH)-0402"))
    )
    (comp (ref "C93")
      (value "10uF")
      (footprint "eagle-import:0603")
      (libsource (lib "eagle-import") (part "CAPACITOR-(INCH)-0603"))
    )
    (comp (ref "C94")
      (value "10uF")
      (footprint "eagle-import:0603")
      (libsource (lib "eagle-import") (part "CAPACITOR-(INCH)-0603"))
    )
    (comp (ref "C95")
      (value "100nF")
      (footprint "eagle-import:0402")
      (libsource (lib "eagle-import") (part "CAPACITOR-(INCH)-0402"))
    )
    (comp (ref "C96")
      (value "10uF")
      (footprint "eagle-import:0603")
      (libsource (lib "eagle-import") (part "CAPACITOR-(INCH)-0603"))
    )
    (comp (ref "C97")
      (value "10uF")
      (footprint "eagle-import:0603")
      (libsource (lib "eagle-import") (part "CAPACITOR-(INCH)-0603"))
    )
    (comp (ref "C98")
      (value "100nF")
      (footprint "eagle-import:0402")
      (libsource (lib "eagle-import") (part "CAPACITOR-(INCH)-0402"))
    )
    (comp (ref "C99")
      (value "100nF")
      (footprint "eagle-import:0402")
      (libsource (lib "eagle-import") (part "CAPACITOR-(INCH)-0402"))
    )
    (comp (ref "C100")
      (value "10uF")
      (footprint "eagle-import:0603")
      (libsource (lib "eagle-import") (part "CAPACITOR-(INCH)-0603"))
    )
    (comp (ref "C101")
      (value "10uF")
      (footprint "eagle-import:0603")
      (libsource (lib "eagle-import") (part "CAPACITOR-(INCH)-0603"))
    )
    (comp (ref "C102")
      (value "100nF")
      (footprint "eagle-import:0402")
      (libsource (lib "eagle-import") (part "CAPACITOR-(INCH)-0402"))
    )
    (comp (ref "C103")
      (value "22pF")
      (footprint "eagle-import:0402")
      (libsource (lib "eagle-import") (part "CAPACITOR-(INCH)-0402"))
    )
    (comp (ref "C104")
      (value "100nF")
      (footprint "eagle-import:0402")
      (libsource (lib "eagle-import") (part "CAPACITOR-(INCH)-0402"))
    )
    (comp (ref "C105")
      (value "10uF")
      (footprint "eagle-import:TOLBA_0603")
      (libsource (lib "eagle-import") (part "TOLBA_CAP"))
    )
    (comp (ref "C106")
      (value "10uF")
      (footprint "eagle-import:TOLBA_0603")
      (libsource (lib "eagle-import") (part "TOLBA_CAP"))
    )
    (comp (ref "C107")
      (value "100nF")
      (footprint "eagle-import:0402")
      (libsource (lib "eagle-import") (part "CAPACITOR-(INCH)-0402"))
    )
    (comp (ref "C108")
      (value "100nF")
      (footprint "eagle-import:0402")
      (libsource (lib "eagle-import") (part "CAPACITOR-(INCH)-0402"))
    )
    (comp (ref "IC1")
      (value "KLM8G1GESD-B03P")
      (footprint "eagle-import:BGA153C50P14X14_1150X1300X80")
      (libsource (lib "eagle-import") (part "KLM8G1GESD-B03P"))
    )
    (comp (ref "IC2")
      (value "ALLWINNER--H3")
      (footprint "eagle-import:BGA347C65P21X21_1400X1400X118")
      (fields (field (name "MANUFACTURER_PART_NUMBER") "Allwinner H3"))
      (libsource (lib "eagle-import") (part "ALLWINNER--H3"))
    )
    (comp (ref "IC3")
      (value "SY6280")
      (footprint "eagle-import:SOT95P285X140-5N")
      (libsource (lib "eagle-import") (part "SY6280"))
    )
    (comp (ref "IC4")
      (value "K4B4G1646D-BCK0")
      (footprint "eagle-import:BGA96C80P9X16_1000X1330X120")
      (fields (field (name "MANUFACTURER_PART_NUMBER") "K4B4G1646B-BCK0"))
      (libsource (lib "eagle-import") (part "K4B4G1646B-BCK0"))
    )
    (comp (ref "IC5")
      (value "RT8059GJ5")
      (footprint "eagle-import:SOT94P280X100-5N")
      (libsource (lib "eagle-import") (part "RT8059GJ5"))
    )
    (comp (ref "IC6")
      (value "RT8059GJ5")
      (footprint "eagle-import:SOT94P280X100-5N")
      (libsource (lib "eagle-import") (part "RT8059GJ5"))
    )
    (comp (ref "IC7")
      (value "SY8089A")
      (footprint "eagle-import:SOT95P285X140-5N")
      (libsource (lib "eagle-import") (part "SY8089A"))
    )
    (comp (ref "IC8")
      (value "NCP803SN263T1G")
      (footprint "eagle-import:SOT96P237X111-3N")
      (fields
        (field (name "MOUSER_PART_NUMBER") "863-NCP803SN263T1G")
        (field (name "RS_PART_NUMBER") "8024341P")
      )
      (libsource (lib "eagle-import") (part "NCP803SN263T1G"))
    )
    (comp (ref "IC9")
      (value "RT8059GJ5")
      (footprint "eagle-import:SOT94P280X100-5N")
      (libsource (lib "eagle-import") (part "RT8059GJ5"))
    )
    (comp (ref "IC10")
      (value "MP2143DJ-LF-P")
      (footprint "eagle-import:SOT65P280X100-8N")
      (fields (field (name "MOUSER_PART_NUMBER") "946-MP2143DJLFP"))
      (libsource (lib "eagle-import") (part "MP2143DJ-LF-P"))
    )
    (comp (ref "JP2")
      (value "PINHD-1X18_2.54-S")
      (footprint "eagle-import:1X18-S")
      (libsource (lib "eagle-import") (part "PINHD-1X18_2.54-S"))
    )
    (comp (ref "JP3")
      (value "PINHD-1X18_2.54-S")
      (footprint "eagle-import:1X18-S")
      (libsource (lib "eagle-import") (part "PINHD-1X18_2.54-S"))
    )
    (comp (ref "L1")
      (value "DFE252010P-4R7M=P2")
      (footprint "eagle-import:INDC2520X100N")
      (libsource (lib "eagle-import") (part "DFE252010P-4R7M=P2"))
    )
    (comp (ref "L2")
      (value "3.9nH")
      (footprint "eagle-import:RESC0402_L")
      (libsource (lib "eagle-import") (part "INDUCTOR_0402_L"))
    )
    (comp (ref "L3")
      (value "DFE252010P-2R2M=P2")
      (footprint "eagle-import:INDC2520X100N")
      (fields
        (field (name "MOUSER_PART_NUMBER") "81-DFE252010P-2R2MP2")
        (field (name "RS_PART_NUMBER") "1670595")
      )
      (libsource (lib "eagle-import") (part "DFE252010P-2R2M=P2"))
    )
    (comp (ref "L4")
      (value "DFE252010P-2R2M=P2")
      (footprint "eagle-import:INDC2520X100N")
      (fields
        (field (name "MOUSER_PART_NUMBER") "81-DFE252010P-2R2MP2")
        (field (name "RS_PART_NUMBER") "1670595")
      )
      (libsource (lib "eagle-import") (part "DFE252010P-2R2M=P2"))
    )
    (comp (ref "L5")
      (value "DFE252010P-2R2M=P2")
      (footprint "eagle-import:INDC2520X100N")
      (fields
        (field (name "MOUSER_PART_NUMBER") "81-DFE252010P-2R2MP2")
        (field (name "RS_PART_NUMBER") "1670595")
      )
      (libsource (lib "eagle-import") (part "DFE252010P-2R2M=P2"))
    )
    (comp (ref "L6")
      (value "DFE252010P-2R2M=P2")
      (footprint "eagle-import:INDC2520X100N")
      (fields
        (field (name "MOUSER_PART_NUMBER") "81-DFE252010P-2R2MP2")
        (field (name "RS_PART_NUMBER") "1670595")
      )
      (libsource (lib "eagle-import") (part "DFE252010P-2R2M=P2"))
    )
    (comp (ref "L7")
      (value "DFE252010P-2R2M=P2")
      (footprint "eagle-import:INDC2520X100N")
      (fields
        (field (name "MOUSER_PART_NUMBER") "81-DFE252010P-2R2MP2")
        (field (name "RS_PART_NUMBER") "1670595")
      )
      (libsource (lib "eagle-import") (part "DFE252010P-2R2M=P2"))
    )
    (comp (ref "LED1")
      (value "BLUE")
      (footprint "eagle-import:0603-LED")
      (libsource (lib "eagle-import") (part "LED-(INCH)-0603"))
    )
    (comp (ref "LED2")
      (value "RED")
      (footprint "eagle-import:0603-LED")
      (libsource (lib "eagle-import") (part "LED-(INCH)-0603"))
    )
    (comp (ref "LED3")
      (value "BLUE")
      (footprint "eagle-import:0603-LED")
      (libsource (lib "eagle-import") (part "LED-(INCH)-0603"))
    )
    (comp (ref "LED4")
      (value "LTST-E263CEGBK")
      (footprint "eagle-import:LTST-E263CEGBK")
      (libsource (lib "eagle-import") (part "LTST-E263CEGBK"))
    )
    (comp (ref "Q1")
      (value "AO3415A")
      (footprint "eagle-import:SOT95P280X125-3N")
      (libsource (lib "eagle-import") (part "AO3415A"))
    )
    (comp (ref "Q2")
      (value "BCM856BS")
      (footprint "eagle-import:SOT65P210X110-6N")
      (fields (field (name "RS_PART_NUMBER") "7816736"))
      (libsource (lib "eagle-import") (part "BCM856BS"))
    )
    (comp (ref "Q3")
      (value "9HT10-32.768KEZF-T")
      (footprint "eagle-import:3.2X1.5")
      (libsource (lib "eagle-import") (part "KX-327-NHT"))
    )
    (comp (ref "Q4")
      (value "L2N7002WT1G")
      (footprint "eagle-import:SOT65P220X100-3N")
      (libsource (lib "eagle-import") (part "L2N7002WT1G"))
    )
    (comp (ref "R1")
      (value "30K ohm")
      (footprint "eagle-import:0402")
      (libsource (lib "eagle-import") (part "RESISTOR-(INCH)-0402"))
    )
    (comp (ref "R2")
      (value "30K ohm")
      (footprint "eagle-import:0402")
      (libsource (lib "eagle-import") (part "RESISTOR-(INCH)-0402"))
    )
    (comp (ref "R3")
      (value "10K ohm")
      (footprint "eagle-import:0402")
      (libsource (lib "eagle-import") (part "RESISTOR-(INCH)-0402"))
    )
    (comp (ref "R4")
      (value "30K ohm")
      (footprint "eagle-import:0402")
      (libsource (lib "eagle-import") (part "RESISTOR-(INCH)-0402"))
    )
    (comp (ref "R5")
      (value "30K ohm")
      (footprint "eagle-import:0402")
      (libsource (lib "eagle-import") (part "RESISTOR-(INCH)-0402"))
    )
    (comp (ref "R6")
      (value "10K ohm")
      (footprint "eagle-import:0402")
      (libsource (lib "eagle-import") (part "RESISTOR-(INCH)-0402"))
    )
    (comp (ref "R7")
      (value "30K ohm")
      (footprint "eagle-import:0402")
      (libsource (lib "eagle-import") (part "RESISTOR-(INCH)-0402"))
    )
    (comp (ref "R8")
      (value "100K ohm")
      (footprint "eagle-import:0402")
      (libsource (lib "eagle-import") (part "RESISTOR-(INCH)-0402"))
    )
    (comp (ref "R9")
      (value "22 ohm")
      (footprint "eagle-import:0402")
      (libsource (lib "eagle-import") (part "RESISTOR-(INCH)-0402"))
    )
    (comp (ref "R10")
      (value "100K ohm")
      (footprint "eagle-import:0402")
      (libsource (lib "eagle-import") (part "RESISTOR-(INCH)-0402"))
    )
    (comp (ref "R11")
      (value "100K ohm")
      (footprint "eagle-import:0402")
      (libsource (lib "eagle-import") (part "RESISTOR-(INCH)-0402"))
    )
    (comp (ref "R12")
      (value "10K ohm / 1%")
      (footprint "eagle-import:0402")
      (libsource (lib "eagle-import") (part "RESISTOR-(INCH)-0402"))
    )
    (comp (ref "R13")
      (value "10K ohm / 1%")
      (footprint "eagle-import:0402")
      (libsource (lib "eagle-import") (part "RESISTOR-(INCH)-0402"))
    )
    (comp (ref "R14")
      (value "6.8K ohm")
      (footprint "eagle-import:0402")
      (libsource (lib "eagle-import") (part "RESISTOR-(INCH)-0402"))
    )
    (comp (ref "R15")
      (value "10K ohm")
      (footprint "eagle-import:0402")
      (libsource (lib "eagle-import") (part "RESISTOR-(INCH)-0402"))
    )
    (comp (ref "R16")
      (value "2K ohm / 1%")
      (footprint "eagle-import:0402")
      (libsource (lib "eagle-import") (part "RESISTOR-(INCH)-0402"))
    )
    (comp (ref "R17")
      (value "2K ohm / 1%")
      (footprint "eagle-import:0402")
      (libsource (lib "eagle-import") (part "RESISTOR-(INCH)-0402"))
    )
    (comp (ref "R18")
      (value "100 ohm")
      (footprint "eagle-import:0402")
      (libsource (lib "eagle-import") (part "RESISTOR-(INCH)-0402"))
    )
    (comp (ref "R19")
      (value "10K ohm")
      (footprint "eagle-import:0402")
      (libsource (lib "eagle-import") (part "RESISTOR-(INCH)-0402"))
    )
    (comp (ref "R20")
      (value "10K ohm")
      (footprint "eagle-import:0402")
      (libsource (lib "eagle-import") (part "RESISTOR-(INCH)-0402"))
    )
    (comp (ref "R21")
      (value "10K ohm")
      (footprint "eagle-import:0402")
      (libsource (lib "eagle-import") (part "RESISTOR-(INCH)-0402"))
    )
    (comp (ref "R22")
      (value "10K ohm")
      (footprint "eagle-import:0402")
      (libsource (lib "eagle-import") (part "RESISTOR-(INCH)-0402"))
    )
    (comp (ref "R23")
      (value "10K ohm")
      (footprint "eagle-import:0402")
      (libsource (lib "eagle-import") (part "RESISTOR-(INCH)-0402"))
    )
    (comp (ref "R24")
      (value "10M ohm")
      (footprint "eagle-import:0402")
      (libsource (lib "eagle-import") (part "RESISTOR-(INCH)-0402"))
    )
    (comp (ref "R25")
      (value "6.8K ohm / 1%")
      (footprint "eagle-import:0402")
      (libsource (lib "eagle-import") (part "RESISTOR-(INCH)-0402"))
    )
    (comp (ref "R26")
      (value "47K ohm")
      (footprint "eagle-import:0402")
      (libsource (lib "eagle-import") (part "RESISTOR-(INCH)-0402"))
    )
    (comp (ref "R27")
      (value "240 ohm / 1%")
      (footprint "eagle-import:0402")
      (libsource (lib "eagle-import") (part "RESISTOR-(INCH)-0402"))
    )
    (comp (ref "R28")
      (value "240 ohm / 1%")
      (footprint "eagle-import:0402")
      (libsource (lib "eagle-import") (part "RESISTOR-(INCH)-0402"))
    )
    (comp (ref "R29")
      (value "10K ohm / 1%")
      (footprint "eagle-import:0402")
      (libsource (lib "eagle-import") (part "RESISTOR-(INCH)-0402"))
    )
    (comp (ref "R30")
      (value "10K ohm / 1%")
      (footprint "eagle-import:0402")
      (libsource (lib "eagle-import") (part "RESISTOR-(INCH)-0402"))
    )
    (comp (ref "R31")
      (value "10K ohm")
      (footprint "eagle-import:0402")
      (libsource (lib "eagle-import") (part "RESISTOR-(INCH)-0402"))
    )
    (comp (ref "R32")
      (value "30K ohm / 1%")
      (footprint "eagle-import:0402")
      (libsource (lib "eagle-import") (part "RESISTOR-(INCH)-0402"))
    )
    (comp (ref "R33")
      (value "100K ohm")
      (footprint "eagle-import:0402")
      (libsource (lib "eagle-import") (part "RESISTOR-(INCH)-0402"))
    )
    (comp (ref "R34")
      (value "15K ohm / 1%")
      (footprint "eagle-import:0402")
      (libsource (lib "eagle-import") (part "RESISTOR-(INCH)-0402"))
    )
    (comp (ref "R35")
      (value "10K ohm / 1%")
      (footprint "eagle-import:0402")
      (libsource (lib "eagle-import") (part "RESISTOR-(INCH)-0402"))
    )
    (comp (ref "R37")
      (value "1.5K ohm")
      (footprint "eagle-import:0402")
      (libsource (lib "eagle-import") (part "RESISTOR-(INCH)-0402"))
    )
    (comp (ref "R38")
      (value "10K ohm")
      (footprint "eagle-import:0402")
      (libsource (lib "eagle-import") (part "RESISTOR-(INCH)-0402"))
    )
    (comp (ref "R39")
      (value "33 ohm")
      (footprint "eagle-import:0402")
      (libsource (lib "eagle-import") (part "RESISTOR-(INCH)-0402"))
    )
    (comp (ref "R40")
      (value "10K ohm")
      (footprint "eagle-import:0402")
      (libsource (lib "eagle-import") (part "RESISTOR-(INCH)-0402"))
    )
    (comp (ref "R41")
      (value "1.5K ohm")
      (footprint "eagle-import:0402")
      (libsource (lib "eagle-import") (part "RESISTOR-(INCH)-0402"))
    )
    (comp (ref "R42")
      (value "1.5K ohm")
      (footprint "eagle-import:0402")
      (libsource (lib "eagle-import") (part "RESISTOR-(INCH)-0402"))
    )
    (comp (ref "R43")
      (value "240 ohm / 1%")
      (footprint "eagle-import:0402")
      (libsource (lib "eagle-import") (part "RESISTOR-(INCH)-0402"))
    )
    (comp (ref "R44")
      (value "6.8K ohm / 1%")
      (footprint "eagle-import:0402")
      (libsource (lib "eagle-import") (part "RESISTOR-(INCH)-0402"))
    )
    (comp (ref "R45")
      (value "30K ohm / 1%")
      (footprint "eagle-import:0402")
      (libsource (lib "eagle-import") (part "RESISTOR-(INCH)-0402"))
    )
    (comp (ref "R46")
      (value "12K ohm / 1%")
      (footprint "eagle-import:0402")
      (libsource (lib "eagle-import") (part "RESISTOR-(INCH)-0402"))
    )
    (comp (ref "R47")
      (value "10K ohm / 1%")
      (footprint "eagle-import:0402")
      (libsource (lib "eagle-import") (part "RESISTOR-(INCH)-0402"))
    )
    (comp (ref "R48")
      (value "30K ohm / 1%")
      (footprint "eagle-import:0402")
      (libsource (lib "eagle-import") (part "RESISTOR-(INCH)-0402"))
    )
    (comp (ref "R49")
      (value "1K ohm")
      (footprint "eagle-import:0402")
      (libsource (lib "eagle-import") (part "RESISTOR-(INCH)-0402"))
    )
    (comp (ref "R50")
      (value "10K ohm")
      (footprint "eagle-import:0402")
      (libsource (lib "eagle-import") (part "RESISTOR-(INCH)-0402"))
    )
    (comp (ref "R51")
      (value "0 ohm")
      (footprint "eagle-import:0402")
      (libsource (lib "eagle-import") (part "RESISTOR-(INCH)-0402"))
    )
    (comp (ref "R52")
      (value "10K ohm")
      (footprint "eagle-import:0402")
      (libsource (lib "eagle-import") (part "RESISTOR-(INCH)-0402"))
    )
    (comp (ref "S1")
      (value "KMR231GLFS")
      (footprint "eagle-import:TACTILE_SWITCH_SMD")
      (libsource (lib "eagle-import") (part "TAC_SWITCHSMD"))
    )
    (comp (ref "S2")
      (value "KMR231GLFS")
      (footprint "eagle-import:TACTILE_SWITCH_SMD")
      (libsource (lib "eagle-import") (part "TAC_SWITCHSMD"))
    )
    (comp (ref "U1")
      (value "AP6212")
      (footprint "eagle-import:AP6212")
      (libsource (lib "eagle-import") (part "AP6212"))
    )
    (comp (ref "U2")
      (value "STM32F411CEU6TR")
      (footprint "eagle-import:UFQFPN-48")
      (libsource (lib "eagle-import") (part "STM32F411CEU6"))
    )
    (comp (ref "X1")
      (value "10118192-0001LF")
      (footprint "eagle-import:10118192-0001LF(MICRO-USB-B-AMPHENOL-FCI)")
      (libsource (lib "eagle-import") (part "10118192-0001LF"))
    )
    (comp (ref "Y1")
      (value "26MHz")
      (footprint "eagle-import:4-SMD-2X1.6MM")
      (libsource (lib "eagle-import") (part "FA-12826.0000MF10Z-W5"))
    )
    (comp (ref "Y2")
      (value "24MHz")
      (footprint "eagle-import:CRYSTAL-SMD-3.2X2.5MM-EPSON-TSX-3225")
      (libsource (lib "eagle-import") (part "CRYSTAL-24MHZ-EPSON-TSX-3225"))
    )
    (comp (ref "Y3")
      (value "CSTCW25M0X53-R0")
      (footprint "eagle-import:CSTCW25M0X53-R0")
      (libsource (lib "eagle-import") (part "CSTCW25M0X53-R0"))
    )
    (comp (ref "Z1")
      (value "AVRL101A1R1NTB/NC")
      (footprint "eagle-import:0402-RES")
      (libsource (lib "eagle-import") (part "VARISTOR-0402"))
    )
    (comp (ref "Z2")
      (value "AVRL101A1R1NTB/NC")
      (footprint "eagle-import:0402-RES")
      (libsource (lib "eagle-import") (part "VARISTOR-0402"))
    )
    (comp (ref "Z3")
      (value "AVRL101A1R1NTB/NC")
      (footprint "eagle-import:0402-RES")
      (libsource (lib "eagle-import") (part "VARISTOR-0402"))
    )
    (comp (ref "Z4")
      (value "AVRL101A1R1NTB/NC")
      (footprint "eagle-import:0402-RES")
      (libsource (lib "eagle-import") (part "VARISTOR-0402"))
    )
  )
  (nets
    (net (code "1") (name "1.2V") (class "Default")
      (node (ref "C19") (pin "1") (pinfunction "P$1_1") (pintype "bidirectional"))
      (node (ref "C20") (pin "1") (pinfunction "P$1_1") (pintype "bidirectional"))
      (node (ref "C23") (pin "1") (pinfunction "P$1_1") (pintype "bidirectional"))
      (node (ref "C26") (pin "1") (pinfunction "P$1_1") (pintype "bidirectional"))
      (node (ref "C29") (pin "1") (pinfunction "P$1_1") (pintype "bidirectional"))
      (node (ref "C66") (pin "1") (pinfunction "P$1_1") (pintype "bidirectional"))
      (node (ref "C72") (pin "1") (pinfunction "P$1_1") (pintype "bidirectional"))
      (node (ref "C78") (pin "1") (pinfunction "P$1_1") (pintype "bidirectional"))
      (node (ref "IC2") (pin "F8") (pinfunction "EPHY_VDD_F8") (pintype "bidirectional"))
      (node (ref "IC2") (pin "H10") (pinfunction "VDD_SYS0_H10") (pintype "bidirectional"))
      (node (ref "IC2") (pin "J10") (pinfunction "VDD_SYS1_J10") (pintype "bidirectional"))
      (node (ref "IC2") (pin "J11") (pinfunction "VDD_SYS2_J11") (pintype "bidirectional"))
      (node (ref "IC2") (pin "J12") (pinfunction "VDD_SYS3_J12") (pintype "bidirectional"))
      (node (ref "IC2") (pin "K10") (pinfunction "VDD_SYS4_K10") (pintype "bidirectional"))
      (node (ref "IC2") (pin "K11") (pinfunction "VDD_SYS5_K11") (pintype "bidirectional"))
      (node (ref "IC2") (pin "K12") (pinfunction "VDD_SYS6_K12") (pintype "bidirectional"))
      (node (ref "IC2") (pin "L10") (pinfunction "VDD_SYS7_L10") (pintype "bidirectional"))
      (node (ref "IC2") (pin "L11") (pinfunction "VDD_SYS8_L11") (pintype "bidirectional"))
      (node (ref "IC2") (pin "L12") (pinfunction "VDD_SYS9_L12") (pintype "bidirectional"))
      (node (ref "IC2") (pin "L13") (pinfunction "VDD_SYS10_L13") (pintype "bidirectional"))
      (node (ref "IC2") (pin "L14") (pinfunction "VDD_SYS11_L14") (pintype "bidirectional"))
      (node (ref "L5") (pin "2") (pinfunction "2_2") (pintype "bidirectional"))
      (node (ref "R35") (pin "2") (pinfunction "2_2") (pintype "bidirectional"))
    )
    (net (code "2") (name "1.5V") (class "Default")
      (node (ref "C11") (pin "1") (pinfunction "P$1_1") (pintype "bidirectional"))
      (node (ref "C12") (pin "1") (pinfunction "P$1_1") (pintype "bidirectional"))
      (node (ref "C37") (pin "1") (pinfunction "P$1_1") (pintype "bidirectional"))
      (node (ref "C52") (pin "1") (pinfunction "P$1_1") (pintype "bidirectional"))
      (node (ref "C55") (pin "1") (pinfunction "P$1_1") (pintype "bidirectional"))
      (node (ref "C56") (pin "1") (pinfunction "P$1_1") (pintype "bidirectional"))
      (node (ref "C57") (pin "1") (pinfunction "P$1_1") (pintype "bidirectional"))
      (node (ref "C6") (pin "1") (pinfunction "P$1_1") (pintype "bidirectional"))
      (node (ref "C61") (pin "1") (pinfunction "P$1_1") (pintype "bidirectional"))
      (node (ref "C62") (pin "1") (pinfunction "P$1_1") (pintype "bidirectional"))
      (node (ref "C63") (pin "1") (pinfunction "P$1_1") (pintype "bidirectional"))
      (node (ref "C65") (pin "1") (pinfunction "P$1_1") (pintype "bidirectional"))
      (node (ref "C68") (pin "1") (pinfunction "P$1_1") (pintype "bidirectional"))
      (node (ref "C69") (pin "1") (pinfunction "P$1_1") (pintype "bidirectional"))
      (node (ref "C71") (pin "1") (pinfunction "P$1_1") (pintype "bidirectional"))
      (node (ref "C73") (pin "1") (pinfunction "P$1_1") (pintype "bidirectional"))
      (node (ref "C75") (pin "1") (pinfunction "P$1_1") (pintype "bidirectional"))
      (node (ref "C76") (pin "1") (pinfunction "P$1_1") (pintype "bidirectional"))
      (node (ref "C77") (pin "1") (pinfunction "P$1_1") (pintype "bidirectional"))
      (node (ref "C80") (pin "1") (pinfunction "P$1_1") (pintype "bidirectional"))
      (node (ref "C81") (pin "1") (pinfunction "P$1_1") (pintype "bidirectional"))
      (node (ref "C83") (pin "1") (pinfunction "P$1_1") (pintype "bidirectional"))
      (node (ref "C84") (pin "1") (pinfunction "P$1_1") (pintype "bidirectional"))
      (node (ref "C85") (pin "1") (pinfunction "P$1_1") (pintype "bidirectional"))
      (node (ref "C9") (pin "1") (pinfunction "P$1_1") (pintype "bidirectional"))
      (node (ref "C90") (pin "1") (pinfunction "P$1_1") (pintype "bidirectional"))
      (node (ref "C92") (pin "1") (pinfunction "P$1_1") (pintype "bidirectional"))
      (node (ref "IC2") (pin "L16") (pinfunction "VCC_DRAM0_L16") (pintype "bidirectional"))
      (node (ref "IC2") (pin "M16") (pinfunction "VCC_DRAM1_M16") (pintype "bidirectional"))
      (node (ref "IC2") (pin "N16") (pinfunction "VCC_DRAM2_N16") (pintype "bidirectional"))
      (node (ref "IC2") (pin "P16") (pinfunction "VCC_DRAM3_P16") (pintype "bidirectional"))
      (node (ref "IC2") (pin "P17") (pinfunction "VCC_DRAM4_P17") (pintype "bidirectional"))
      (node (ref "IC2") (pin "R16") (pinfunction "VCC_DRAM5_R16") (pintype "bidirectional"))
      (node (ref "IC2") (pin "T12") (pinfunction "VCC_DRAM6_T12") (pintype "bidirectional"))
      (node (ref "IC2") (pin "T13") (pinfunction "VCC_DRAM7_T13") (pintype "bidirectional"))
      (node (ref "IC2") (pin "T14") (pinfunction "VCC_DRAM8_T14") (pintype "bidirectional"))
      (node (ref "IC2") (pin "T15") (pinfunction "VCC_DRAM9_T15") (pintype "bidirectional"))
      (node (ref "IC2") (pin "U11") (pinfunction "VCC_DRAM10_U11") (pintype "bidirectional"))
      (node (ref "IC4") (pin "A1") (pinfunction "VDDQ_1_A1") (pintype "bidirectional"))
      (node (ref "IC4") (pin "A8") (pinfunction "VDDQ_2_A8") (pintype "bidirectional"))
      (node (ref "IC4") (pin "B2") (pinfunction "VDD_1_B2") (pintype "bidirectional"))
      (node (ref "IC4") (pin "C1") (pinfunction "VDDQ_3_C1") (pintype "bidirectional"))
      (node (ref "IC4") (pin "C9") (pinfunction "VDDQ_4_C9") (pintype "bidirectional"))
      (node (ref "IC4") (pin "D2") (pinfunction "VDDQ_5_D2") (pintype "bidirectional"))
      (node (ref "IC4") (pin "D9") (pinfunction "VDD_2_D9") (pintype "bidirectional"))
      (node (ref "IC4") (pin "E9") (pinfunction "VDDQ_6_E9") (pintype "bidirectional"))
      (node (ref "IC4") (pin "F1") (pinfunction "VDDQ_7_F1") (pintype "bidirectional"))
      (node (ref "IC4") (pin "G7") (pinfunction "VDD_3_G7") (pintype "bidirectional"))
      (node (ref "IC4") (pin "H2") (pinfunction "VDDQ_8_H2") (pintype "bidirectional"))
      (node (ref "IC4") (pin "H9") (pinfunction "VDDQ_9_H9") (pintype "bidirectional"))
      (node (ref "IC4") (pin "K2") (pinfunction "VDD_4_K2") (pintype "bidirectional"))
      (node (ref "IC4") (pin "K8") (pinfunction "VDD_5_K8") (pintype "bidirectional"))
      (node (ref "IC4") (pin "N1") (pinfunction "VDD_6_N1") (pintype "bidirectional"))
      (node (ref "IC4") (pin "N9") (pinfunction "VDD_7_N9") (pintype "bidirectional"))
      (node (ref "IC4") (pin "R1") (pinfunction "VDD_8_R1") (pintype "bidirectional"))
      (node (ref "IC4") (pin "R9") (pinfunction "VDD_9_R9") (pintype "bidirectional"))
      (node (ref "L4") (pin "2") (pinfunction "2_2") (pintype "bidirectional"))
      (node (ref "R16") (pin "2") (pinfunction "2_2") (pintype "bidirectional"))
      (node (ref "R34") (pin "2") (pinfunction "2_2") (pintype "bidirectional"))
    )
    (net (code "3") (name "3.3V") (class "Default")
      (node (ref "C1") (pin "2") (pinfunction "P$2_2") (pintype "bidirectional"))
      (node (ref "C10") (pin "1") (pinfunction "P$1_1") (pintype "bidirectional"))
      (node (ref "C100") (pin "1") (pinfunction "P$1_1") (pintype "bidirectional"))
      (node (ref "C101") (pin "1") (pinfunction "P$1_1") (pintype "bidirectional"))
      (node (ref "C102") (pin "1") (pinfunction "P$1_1") (pintype "bidirectional"))
      (node (ref "C108") (pin "1") (pinfunction "P$1_1") (pintype "bidirectional"))
      (node (ref "C13") (pin "1") (pinfunction "P$1_1") (pintype "bidirectional"))
      (node (ref "C30") (pin "1") (pinfunction "P$1_1") (pintype "bidirectional"))
      (node (ref "C33") (pin "1") (pinfunction "P$1_1") (pintype "bidirectional"))
      (node (ref "C34") (pin "1") (pinfunction "P$1_1") (pintype "bidirectional"))
      (node (ref "C35") (pin "1") (pinfunction "P$1_1") (pintype "bidirectional"))
      (node (ref "C5") (pin "1") (pinfunction "P$1_1") (pintype "bidirectional"))
      (node (ref "C54") (pin "1") (pinfunction "P$1_1") (pintype "bidirectional"))
      (node (ref "C74") (pin "1") (pinfunction "P$1_1") (pintype "bidirectional"))
      (node (ref "C8") (pin "1") (pinfunction "P$1_1") (pintype "bidirectional"))
      (node (ref "IC1") (pin "C6") (pinfunction "VDD_1_C6") (pintype "bidirectional"))
      (node (ref "IC1") (pin "E6") (pinfunction "VDDF_1_E6") (pintype "bidirectional"))
      (node (ref "IC1") (pin "F5") (pinfunction "VDDF_2_F5") (pintype "bidirectional"))
      (node (ref "IC1") (pin "J10") (pinfunction "VDDF_3_J10") (pintype "bidirectional"))
      (node (ref "IC1") (pin "K9") (pinfunction "VDDF_4_K9") (pintype "bidirectional"))
      (node (ref "IC1") (pin "M4") (pinfunction "VDD_2_M4") (pintype "bidirectional"))
      (node (ref "IC1") (pin "N4") (pinfunction "VDD_3_N4") (pintype "bidirectional"))
      (node (ref "IC1") (pin "P3") (pinfunction "VDD_4_P3") (pintype "bidirectional"))
      (node (ref "IC1") (pin "P5") (pinfunction "VDD_5_P5") (pintype "bidirectional"))
      (node (ref "IC2") (pin "G10") (pinfunction "VDD_EFUSE_G10") (pintype "bidirectional"))
      (node (ref "IC2") (pin "G11") (pinfunction "VCC_USB_G11") (pintype "bidirectional"))
      (node (ref "IC2") (pin "G13") (pinfunction "VCC_IO0_G13") (pintype "bidirectional"))
      (node (ref "IC2") (pin "G14") (pinfunction "VCC_IO1_G14") (pintype "bidirectional"))
      (node (ref "IC2") (pin "G15") (pinfunction "VCC_IO2_G15") (pintype "bidirectional"))
      (node (ref "IC2") (pin "G7") (pinfunction "EPHY_VCC_G7") (pintype "bidirectional"))
      (node (ref "IC2") (pin "G9") (pinfunction "V33_TV_G9") (pintype "bidirectional"))
      (node (ref "IC2") (pin "H13") (pinfunction "VCC_IO3_H13") (pintype "bidirectional"))
      (node (ref "IC2") (pin "H14") (pinfunction "VCC_IO4_H14") (pintype "bidirectional"))
      (node (ref "IC2") (pin "H7") (pinfunction "VCC_PG_H7") (pintype "bidirectional"))
      (node (ref "IC2") (pin "J14") (pinfunction "VCC_IO5_J14") (pintype "bidirectional"))
      (node (ref "IC2") (pin "J15") (pinfunction "VCC_PD_J15") (pintype "bidirectional"))
      (node (ref "IC2") (pin "J6") (pinfunction "HVCC_J6") (pintype "bidirectional"))
      (node (ref "IC2") (pin "K6") (pinfunction "VCC_RTC_K6") (pintype "bidirectional"))
      (node (ref "IC2") (pin "N3") (pinfunction "VCC_PLL_N3") (pintype "bidirectional"))
      (node (ref "IC2") (pin "V3") (pinfunction "AVCC_V3") (pintype "bidirectional"))
      (node (ref "IC8") (pin "3") (pinfunction "VCC_3") (pintype "power_in"))
      (node (ref "L6") (pin "2") (pinfunction "2_2") (pintype "bidirectional"))
      (node (ref "LED2") (pin "A") (pinfunction "A_A") (pintype "passive"))
      (node (ref "R1") (pin "1") (pinfunction "1_1") (pintype "bidirectional"))
      (node (ref "R11") (pin "1") (pinfunction "1_1") (pintype "bidirectional"))
      (node (ref "R2") (pin "1") (pinfunction "1_1") (pintype "bidirectional"))
      (node (ref "R22") (pin "2") (pinfunction "2_2") (pintype "bidirectional"))
      (node (ref "R23") (pin "2") (pinfunction "2_2") (pintype "bidirectional"))
      (node (ref "R26") (pin "1") (pinfunction "1_1") (pintype "bidirectional"))
      (node (ref "R3") (pin "2") (pinfunction "2_2") (pintype "bidirectional"))
      (node (ref "R31") (pin "1") (pinfunction "1_1") (pintype "bidirectional"))
      (node (ref "R33") (pin "1") (pinfunction "1_1") (pintype "bidirectional"))
      (node (ref "R38") (pin "1") (pinfunction "1_1") (pintype "bidirectional"))
      (node (ref "R4") (pin "1") (pinfunction "1_1") (pintype "bidirectional"))
      (node (ref "R40") (pin "1") (pinfunction "1_1") (pintype "bidirectional"))
      (node (ref "R45") (pin "2") (pinfunction "2_2") (pintype "bidirectional"))
      (node (ref "R5") (pin "1") (pinfunction "1_1") (pintype "bidirectional"))
      (node (ref "R50") (pin "2") (pinfunction "2_2") (pintype "bidirectional"))
      (node (ref "R52") (pin "1") (pinfunction "1_1") (pintype "bidirectional"))
      (node (ref "R6") (pin "2") (pinfunction "2_2") (pintype "bidirectional"))
      (node (ref "R7") (pin "1") (pinfunction "1_1") (pintype "bidirectional"))
      (node (ref "R8") (pin "1") (pinfunction "1_1") (pintype "bidirectional"))
      (node (ref "U1") (pin "22") (pinfunction "VDDIO_22") (pintype "bidirectional"))
      (node (ref "U1") (pin "9") (pinfunction "VBAT_9") (pintype "bidirectional"))
    )
    (net (code "4") (name "A0") (class "Default")
      (node (ref "JP3") (pin "1") (pinfunction "1_1") (pintype "passive"))
      (node (ref "U2") (pin "19") (pinfunction "PB1_19") (pintype "bidirectional"))
    )
    (net (code "5") (name "A1") (class "Default")
      (node (ref "JP3") (pin "2") (pinfunction "2_2") (pintype "passive"))
      (node (ref "U2") (pin "18") (pinfunction "PB0_18") (pintype "bidirectional"))
    )
    (net (code "6") (name "A2") (class "Default")
      (node (ref "JP3") (pin "3") (pinfunction "3_3") (pintype "passive"))
      (node (ref "U2") (pin "17") (pinfunction "PA7_17") (pintype "bidirectional"))
    )
    (net (code "7") (name "A3") (class "Default")
      (node (ref "JP3") (pin "4") (pinfunction "4_4") (pintype "passive"))
      (node (ref "U2") (pin "16") (pinfunction "PA6_16") (pintype "bidirectional"))
    )
    (net (code "8") (name "A4") (class "Default")
      (node (ref "JP3") (pin "5") (pinfunction "5_5") (pintype "passive"))
      (node (ref "U2") (pin "15") (pinfunction "PA5_15") (pintype "bidirectional"))
    )
    (net (code "9") (name "A5") (class "Default")
      (node (ref "JP3") (pin "6") (pinfunction "6_6") (pintype "passive"))
      (node (ref "U2") (pin "14") (pinfunction "PA4_14") (pintype "bidirectional"))
    )
    (net (code "10") (name "A6") (class "Default")
      (node (ref "JP3") (pin "7") (pinfunction "7_7") (pintype "passive"))
      (node (ref "U2") (pin "13") (pinfunction "PA3_13") (pintype "bidirectional"))
    )
    (net (code "11") (name "A7") (class "Default")
      (node (ref "JP3") (pin "8") (pinfunction "8_8") (pintype "passive"))
      (node (ref "U2") (pin "12") (pinfunction "PA2_12") (pintype "bidirectional"))
    )
    (net (code "12") (name "A8") (class "Default")
      (node (ref "JP3") (pin "9") (pinfunction "9_9") (pintype "passive"))
      (node (ref "U2") (pin "11") (pinfunction "PA1_11") (pintype "bidirectional"))
    )
    (net (code "13") (name "A9") (class "Default")
      (node (ref "JP3") (pin "10") (pinfunction "10_10") (pintype "passive"))
      (node (ref "U2") (pin "10") (pinfunction "PA0_10") (pintype "bidirectional"))
    )
    (net (code "14") (name "AP_RESET#") (class "Default")
      (node (ref "C89") (pin "1") (pinfunction "P$1_1") (pintype "bidirectional"))
      (node (ref "IC2") (pin "V6") (pinfunction "RESET_V6") (pintype "bidirectional"))
      (node (ref "IC8") (pin "2") (pinfunction "~{RESET}_2") (pintype "bidirectional"))
      (node (ref "R38") (pin "2") (pinfunction "2_2") (pintype "bidirectional"))
    )
    (net (code "15") (name "B0") (class "Default")
      (node (ref "JP2") (pin "18") (pinfunction "18_18") (pintype "passive"))
      (node (ref "U2") (pin "32") (pinfunction "PA11_32") (pintype "bidirectional"))
    )
    (net (code "16") (name "B1") (class "Default")
      (node (ref "JP2") (pin "17") (pinfunction "17_17") (pintype "passive"))
      (node (ref "U2") (pin "33") (pinfunction "PA12_33") (pintype "bidirectional"))
    )
    (net (code "17") (name "B2") (class "Default")
      (node (ref "JP2") (pin "16") (pinfunction "16_16") (pintype "passive"))
      (node (ref "U2") (pin "28") (pinfunction "PB15_28") (pintype "bidirectional"))
    )
    (net (code "18") (name "B3") (class "Default")
      (node (ref "JP2") (pin "15") (pinfunction "15_15") (pintype "passive"))
      (node (ref "U2") (pin "27") (pinfunction "PB14_27") (pintype "bidirectional"))
    )
    (net (code "19") (name "B4") (class "Default")
      (node (ref "JP2") (pin "14") (pinfunction "14_14") (pintype "passive"))
      (node (ref "U2") (pin "26") (pinfunction "PB13_26") (pintype "bidirectional"))
    )
    (net (code "20") (name "B5") (class "Default")
      (node (ref "JP2") (pin "13") (pinfunction "13_13") (pintype "passive"))
      (node (ref "U2") (pin "25") (pinfunction "PB12_25") (pintype "bidirectional"))
    )
    (net (code "21") (name "BOOT0") (class "Default")
      (node (ref "IC2") (pin "C3") (pinfunction "PG8/UART1_RTS/PG_EINT8_C3") (pintype "bidirectional"))
      (node (ref "R20") (pin "1") (pinfunction "1_1") (pintype "bidirectional"))
      (node (ref "U2") (pin "44") (pinfunction "BOOT0_44") (pintype "bidirectional"))
    )
    (net (code "22") (name "C0") (class "Default")
      (node (ref "JP2") (pin "12") (pinfunction "12_12") (pintype "passive"))
      (node (ref "U2") (pin "45") (pinfunction "PB8_45") (pintype "bidirectional"))
    )
    (net (code "23") (name "C1") (class "Default")
      (node (ref "JP2") (pin "11") (pinfunction "11_11") (pintype "passive"))
      (node (ref "U2") (pin "29") (pinfunction "PA8_29") (pintype "bidirectional"))
    )
    (net (code "24") (name "C2") (class "Default")
      (node (ref "JP2") (pin "10") (pinfunction "10_10") (pintype "passive"))
      (node (ref "U2") (pin "46") (pinfunction "PB9_46") (pintype "bidirectional"))
    )
    (net (code "25") (name "C3") (class "Default")
      (node (ref "JP2") (pin "9") (pinfunction "9_9") (pintype "passive"))
      (node (ref "U2") (pin "21") (pinfunction "PB10_21") (pintype "bidirectional"))
    )
    (net (code "26") (name "C4") (class "Default")
      (node (ref "JP2") (pin "8") (pinfunction "8_8") (pintype "passive"))
      (node (ref "U2") (pin "43") (pinfunction "PB7_43") (pintype "bidirectional"))
    )
    (net (code "27") (name "C5") (class "Default")
      (node (ref "JP2") (pin "7") (pinfunction "7_7") (pintype "passive"))
      (node (ref "U2") (pin "42") (pinfunction "PB6_42") (pintype "bidirectional"))
    )
    (net (code "28") (name "CPUX_VSET") (class "Default")
      (node (ref "IC2") (pin "A16") (pinfunction "PC7/NAND_RB1_A16") (pintype "bidirectional"))
      (node (ref "Q4") (pin "1") (pinfunction "G_1") (pintype "bidirectional"))
      (node (ref "R50") (pin "1") (pinfunction "1_1") (pintype "bidirectional"))
    )
    (net (code "29") (name "D0") (class "Default")
      (node (ref "JP2") (pin "6") (pinfunction "6_6") (pintype "passive"))
      (node (ref "U2") (pin "41") (pinfunction "PB5_41") (pintype "bidirectional"))
    )
    (net (code "30") (name "D1") (class "Default")
      (node (ref "JP2") (pin "5") (pinfunction "5_5") (pintype "passive"))
      (node (ref "U2") (pin "40") (pinfunction "PB4_40") (pintype "bidirectional"))
    )
    (net (code "31") (name "D2") (class "Default")
      (node (ref "JP2") (pin "4") (pinfunction "4_4") (pintype "passive"))
      (node (ref "U2") (pin "39") (pinfunction "PB3_39") (pintype "bidirectional"))
    )
    (net (code "32") (name "D3") (class "Default")
      (node (ref "JP2") (pin "3") (pinfunction "3_3") (pintype "passive"))
      (node (ref "U2") (pin "38") (pinfunction "PA15_38") (pintype "bidirectional"))
    )
    (net (code "33") (name "D4") (class "Default")
      (node (ref "JP2") (pin "2") (pinfunction "2_2") (pintype "passive"))
      (node (ref "U2") (pin "37") (pinfunction "PA14_37") (pintype "bidirectional"))
    )
    (net (code "34") (name "D5") (class "Default")
      (node (ref "JP2") (pin "1") (pinfunction "1_1") (pintype "passive"))
      (node (ref "LED1") (pin "A") (pinfunction "A_A") (pintype "passive"))
      (node (ref "U2") (pin "34") (pinfunction "PA13_34") (pintype "bidirectional"))
    )
    (net (code "35") (name "EMMC_CLK") (class "Default")
      (node (ref "IC1") (pin "M6") (pinfunction "CLK_M6") (pintype "bidirectional"))
      (node (ref "IC2") (pin "A17") (pinfunction "PC5/NAND_RE/SDC2_CLK_A17") (pintype "bidirectional"))
    )
    (net (code "36") (name "EMMC_CMD") (class "Default")
      (node (ref "IC1") (pin "M5") (pinfunction "CMD_M5") (pintype "bidirectional"))
      (node (ref "IC2") (pin "E16") (pinfunction "PC6/NAND_RB0/SDC2_CMD_E16") (pintype "bidirectional"))
      (node (ref "R3") (pin "1") (pinfunction "1_1") (pintype "bidirectional"))
    )
    (net (code "37") (name "EMMC_D0") (class "Default")
      (node (ref "IC1") (pin "A3") (pinfunction "DAT0_A3") (pintype "bidirectional"))
      (node (ref "IC2") (pin "B18") (pinfunction "PC8/NAND_DQ0/SDC2_D0_B18") (pintype "bidirectional"))
    )
    (net (code "38") (name "EMMC_D1") (class "Default")
      (node (ref "IC1") (pin "A4") (pinfunction "DAT1_A4") (pintype "bidirectional"))
      (node (ref "IC2") (pin "C17") (pinfunction "PC9/NAND_DQ1/SDC2_D1_C17") (pintype "bidirectional"))
    )
    (net (code "39") (name "EMMC_D2") (class "Default")
      (node (ref "IC1") (pin "A5") (pinfunction "DAT2_A5") (pintype "bidirectional"))
      (node (ref "IC2") (pin "D17") (pinfunction "PC10/NAND_DQ2/SDC2_D2_D17") (pintype "bidirectional"))
    )
    (net (code "40") (name "EMMC_D3") (class "Default")
      (node (ref "IC1") (pin "B2") (pinfunction "DAT3_B2") (pintype "bidirectional"))
      (node (ref "IC2") (pin "C18") (pinfunction "PC11/NAND_DQ3/SDC2_D3_C18") (pintype "bidirectional"))
    )
    (net (code "41") (name "EMMC_D4") (class "Default")
      (node (ref "IC1") (pin "B3") (pinfunction "DAT4_B3") (pintype "bidirectional"))
      (node (ref "IC2") (pin "B17") (pinfunction "PC12/NAND_DQ4/SDC2_D4_B17") (pintype "bidirectional"))
    )
    (net (code "42") (name "EMMC_D5") (class "Default")
      (node (ref "IC1") (pin "B4") (pinfunction "DAT5_B4") (pintype "bidirectional"))
      (node (ref "IC2") (pin "B19") (pinfunction "PC13/NAND_DQ5/SDC2_D5_B19") (pintype "bidirectional"))
    )
    (net (code "43") (name "EMMC_D6") (class "Default")
      (node (ref "IC1") (pin "B5") (pinfunction "DAT6_B5") (pintype "bidirectional"))
      (node (ref "IC2") (pin "F17") (pinfunction "PC14/NAND_DQ6/SDC2_D6_F17") (pintype "bidirectional"))
    )
    (net (code "44") (name "EMMC_D7") (class "Default")
      (node (ref "IC1") (pin "B6") (pinfunction "DAT7_B6") (pintype "bidirectional"))
      (node (ref "IC2") (pin "C19") (pinfunction "PC15/NAND_DQ7/SDC2_D7_C19") (pintype "bidirectional"))
    )
    (net (code "45") (name "EMMC_RST") (class "Default")
      (node (ref "IC1") (pin "K5") (pinfunction "RSTN_K5") (pintype "bidirectional"))
      (node (ref "IC2") (pin "H16") (pinfunction "PC16/NAND_DQS/SDC2_RST_H16") (pintype "bidirectional"))
    )
    (net (code "46") (name "GND") (class "Default")
      (node (ref "C1") (pin "1") (pinfunction "P$1_1") (pintype "bidirectional"))
      (node (ref "C10") (pin "2") (pinfunction "P$2_2") (pintype "bidirectional"))
      (node (ref "C100") (pin "2") (pinfunction "P$2_2") (pintype "bidirectional"))
      (node (ref "C101") (pin "2") (pinfunction "P$2_2") (pintype "bidirectional"))
      (node (ref "C102") (pin "2") (pinfunction "P$2_2") (pintype "bidirectional"))
      (node (ref "C104") (pin "2") (pinfunction "P$2_2") (pintype "bidirectional"))
      (node (ref "C105") (pin "2") (pinfunction "P$2_2") (pintype "bidirectional"))
      (node (ref "C106") (pin "2") (pinfunction "P$2_2") (pintype "bidirectional"))
      (node (ref "C107") (pin "2") (pinfunction "P$2_2") (pintype "bidirectional"))
      (node (ref "C108") (pin "2") (pinfunction "P$2_2") (pintype "bidirectional"))
      (node (ref "C11") (pin "2") (pinfunction "P$2_2") (pintype "bidirectional"))
      (node (ref "C12") (pin "2") (pinfunction "P$2_2") (pintype "bidirectional"))
      (node (ref "C13") (pin "2") (pinfunction "P$2_2") (pintype "bidirectional"))
      (node (ref "C14") (pin "1") (pinfunction "P$1_1") (pintype "bidirectional"))
      (node (ref "C15") (pin "1") (pinfunction "P$1_1") (pintype "bidirectional"))
      (node (ref "C16") (pin "2") (pinfunction "P$2_2") (pintype "bidirectional"))
      (node (ref "C17") (pin "2") (pinfunction "P$2_2") (pintype "bidirectional"))
      (node (ref "C18") (pin "2") (pinfunction "P$2_2") (pintype "bidirectional"))
      (node (ref "C19") (pin "2") (pinfunction "P$2_2") (pintype "bidirectional"))
      (node (ref "C2") (pin "2") (pinfunction "P$2_2") (pintype "bidirectional"))
      (node (ref "C20") (pin "2") (pinfunction "P$2_2") (pintype "bidirectional"))
      (node (ref "C21") (pin "2") (pinfunction "P$2_2") (pintype "bidirectional"))
      (node (ref "C22") (pin "1") (pinfunction "P$1_1") (pintype "bidirectional"))
      (node (ref "C23") (pin "2") (pinfunction "P$2_2") (pintype "bidirectional"))
      (node (ref "C24") (pin "2") (pinfunction "P$2_2") (pintype "bidirectional"))
      (node (ref "C25") (pin "2") (pinfunction "P$2_2") (pintype "bidirectional"))
      (node (ref "C26") (pin "2") (pinfunction "P$2_2") (pintype "bidirectional"))
      (node (ref "C27") (pin "1") (pinfunction "P$1_1") (pintype "bidirectional"))
      (node (ref "C28") (pin "2") (pinfunction "P$2_2") (pintype "bidirectional"))
      (node (ref "C29") (pin "2") (pinfunction "P$2_2") (pintype "bidirectional"))
      (node (ref "C3") (pin "1") (pinfunction "P$1_1") (pintype "bidirectional"))
      (node (ref "C30") (pin "2") (pinfunction "P$2_2") (pintype "bidirectional"))
      (node (ref "C31") (pin "2") (pinfunction "P$2_2") (pintype "bidirectional"))
      (node (ref "C32") (pin "2") (pinfunction "P$2_2") (pintype "bidirectional"))
      (node (ref "C33") (pin "2") (pinfunction "P$2_2") (pintype "bidirectional"))
      (node (ref "C34") (pin "2") (pinfunction "P$2_2") (pintype "bidirectional"))
      (node (ref "C35") (pin "2") (pinfunction "P$2_2") (pintype "bidirectional"))
      (node (ref "C36") (pin "1") (pinfunction "P$1_1") (pintype "bidirectional"))
      (node (ref "C38") (pin "2") (pinfunction "P$2_2") (pintype "bidirectional"))
      (node (ref "C39") (pin "2") (pinfunction "P$2_2") (pintype "bidirectional"))
      (node (ref "C4") (pin "2") (pinfunction "P$2_2") (pintype "bidirectional"))
      (node (ref "C40") (pin "2") (pinfunction "P$2_2") (pintype "bidirectional"))
      (node (ref "C41") (pin "2") (pinfunction "P$2_2") (pintype "bidirectional"))
      (node (ref "C42") (pin "2") (pinfunction "P$2_2") (pintype "bidirectional"))
      (node (ref "C43") (pin "2") (pinfunction "P$2_2") (pintype "bidirectional"))
      (node (ref "C44") (pin "2") (pinfunction "P$2_2") (pintype "bidirectional"))
      (node (ref "C45") (pin "2") (pinfunction "P$2_2") (pintype "bidirectional"))
      (node (ref "C46") (pin "2") (pinfunction "P$2_2") (pintype "bidirectional"))
      (node (ref "C47") (pin "2") (pinfunction "P$2_2") (pintype "bidirectional"))
      (node (ref "C48") (pin "2") (pinfunction "P$2_2") (pintype "bidirectional"))
      (node (ref "C49") (pin "2") (pinfunction "P$2_2") (pintype "bidirectional"))
      (node (ref "C5") (pin "2") (pinfunction "P$2_2") (pintype "bidirectional"))
      (node (ref "C50") (pin "2") (pinfunction "P$2_2") (pintype "bidirectional"))
      (node (ref "C51") (pin "2") (pinfunction "P$2_2") (pintype "bidirectional"))
      (node (ref "C52") (pin "2") (pinfunction "P$2_2") (pintype "bidirectional"))
      (node (ref "C53") (pin "2") (pinfunction "P$2_2") (pintype "bidirectional"))
      (node (ref "C54") (pin "2") (pinfunction "P$2_2") (pintype "bidirectional"))
      (node (ref "C55") (pin "2") (pinfunction "P$2_2") (pintype "bidirectional"))
      (node (ref "C56") (pin "2") (pinfunction "P$2_2") (pintype "bidirectional"))
      (node (ref "C57") (pin "2") (pinfunction "P$2_2") (pintype "bidirectional"))
      (node (ref "C58") (pin "2") (pinfunction "P$2_2") (pintype "bidirectional"))
      (node (ref "C59") (pin "2") (pinfunction "P$2_2") (pintype "bidirectional"))
      (node (ref "C6") (pin "2") (pinfunction "P$2_2") (pintype "bidirectional"))
      (node (ref "C60") (pin "2") (pinfunction "P$2_2") (pintype "bidirectional"))
      (node (ref "C61") (pin "2") (pinfunction "P$2_2") (pintype "bidirectional"))
      (node (ref "C62") (pin "2") (pinfunction "P$2_2") (pintype "bidirectional"))
      (node (ref "C63") (pin "2") (pinfunction "P$2_2") (pintype "bidirectional"))
      (node (ref "C64") (pin "2") (pinfunction "P$2_2") (pintype "bidirectional"))
      (node (ref "C65") (pin "2") (pinfunction "P$2_2") (pintype "bidirectional"))
      (node (ref "C66") (pin "2") (pinfunction "P$2_2") (pintype "bidirectional"))
      (node (ref "C67") (pin "2") (pinfunction "P$2_2") (pintype "bidirectional"))
      (node (ref "C68") (pin "2") (pinfunction "P$2_2") (pintype "bidirectional"))
      (node (ref "C69") (pin "2") (pinfunction "P$2_2") (pintype "bidirectional"))
      (node (ref "C7") (pin "1") (pinfunction "P$1_1") (pintype "bidirectional"))
      (node (ref "C70") (pin "2") (pinfunction "P$2_2") (pintype "bidirectional"))
      (node (ref "C71") (pin "2") (pinfunction "P$2_2") (pintype "bidirectional"))
      (node (ref "C72") (pin "2") (pinfunction "P$2_2") (pintype "bidirectional"))
      (node (ref "C73") (pin "2") (pinfunction "P$2_2") (pintype "bidirectional"))
      (node (ref "C74") (pin "2") (pinfunction "P$2_2") (pintype "bidirectional"))
      (node (ref "C75") (pin "2") (pinfunction "P$2_2") (pintype "bidirectional"))
      (node (ref "C76") (pin "2") (pinfunction "P$2_2") (pintype "bidirectional"))
      (node (ref "C77") (pin "2") (pinfunction "P$2_2") (pintype "bidirectional"))
      (node (ref "C78") (pin "2") (pinfunction "P$2_2") (pintype "bidirectional"))
      (node (ref "C79") (pin "2") (pinfunction "P$2_2") (pintype "bidirectional"))
      (node (ref "C8") (pin "2") (pinfunction "P$2_2") (pintype "bidirectional"))
      (node (ref "C80") (pin "2") (pinfunction "P$2_2") (pintype "bidirectional"))
      (node (ref "C81") (pin "2") (pinfunction "P$2_2") (pintype "bidirectional"))
      (node (ref "C82") (pin "2") (pinfunction "P$2_2") (pintype "bidirectional"))
      (node (ref "C83") (pin "2") (pinfunction "P$2_2") (pintype "bidirectional"))
      (node (ref "C84") (pin "2") (pinfunction "P$2_2") (pintype "bidirectional"))
      (node (ref "C85") (pin "2") (pinfunction "P$2_2") (pintype "bidirectional"))
      (node (ref "C86") (pin "2") (pinfunction "P$2_2") (pintype "bidirectional"))
      (node (ref "C87") (pin "1") (pinfunction "P$1_1") (pintype "bidirectional"))
      (node (ref "C88") (pin "1") (pinfunction "P$1_1") (pintype "bidirectional"))
      (node (ref "C89") (pin "2") (pinfunction "P$2_2") (pintype "bidirectional"))
      (node (ref "C9") (pin "2") (pinfunction "P$2_2") (pintype "bidirectional"))
      (node (ref "C90") (pin "2") (pinfunction "P$2_2") (pintype "bidirectional"))
      (node (ref "C91") (pin "2") (pinfunction "P$2_2") (pintype "bidirectional"))
      (node (ref "C92") (pin "2") (pinfunction "P$2_2") (pintype "bidirectional"))
      (node (ref "C93") (pin "2") (pinfunction "P$2_2") (pintype "bidirectional"))
      (node (ref "C94") (pin "2") (pinfunction "P$2_2") (pintype "bidirectional"))
      (node (ref "C95") (pin "2") (pinfunction "P$2_2") (pintype "bidirectional"))
      (node (ref "C96") (pin "2") (pinfunction "P$2_2") (pintype "bidirectional"))
      (node (ref "C97") (pin "2") (pinfunction "P$2_2") (pintype "bidirectional"))
      (node (ref "C98") (pin "2") (pinfunction "P$2_2") (pintype "bidirectional"))
      (node (ref "C99") (pin "2") (pinfunction "P$2_2") (pintype "bidirectional"))
      (node (ref "IC1") (pin "A6") (pinfunction "VSS_1_A6") (pintype "bidirectional"))
      (node (ref "IC1") (pin "C4") (pinfunction "VSS_2_C4") (pintype "bidirectional"))
      (node (ref "IC1") (pin "E7") (pinfunction "VSS_3_E7") (pintype "bidirectional"))
      (node (ref "IC1") (pin "G5") (pinfunction "VSS_4_G5") (pintype "bidirectional"))
      (node (ref "IC1") (pin "H10") (pinfunction "VSS_5_H10") (pintype "bidirectional"))
      (node (ref "IC1") (pin "J5") (pinfunction "VSS_6_J5") (pintype "bidirectional"))
      (node (ref "IC1") (pin "K8") (pinfunction "VSS_7_K8") (pintype "bidirectional"))
      (node (ref "IC1") (pin "N2") (pinfunction "VSS_8_N2") (pintype "bidirectional"))
      (node (ref "IC1") (pin "N5") (pinfunction "VSS_9_N5") (pintype "bidirectional"))
      (node (ref "IC1") (pin "P4") (pinfunction "VSS_10_P4") (pintype "bidirectional"))
      (node (ref "IC1") (pin "P6") (pinfunction "VSS_11_P6") (pintype "bidirectional"))
      (node (ref "IC10") (pin "4") (pinfunction "PGND_4") (pintype "bidirectional"))
      (node (ref "IC10") (pin "6") (pinfunction "AGND_6") (pintype "bidirectional"))
      (node (ref "IC2") (pin "A21") (pinfunction "GND0_A21") (pintype "bidirectional"))
      (node (ref "IC2") (pin "AA1") (pinfunction "GND1_AA1") (pintype "bidirectional"))
      (node (ref "IC2") (pin "G8") (pinfunction "GND2_G8") (pintype "bidirectional"))
      (node (ref "IC2") (pin "H12") (pinfunction "GND3_H12") (pintype "bidirectional"))
      (node (ref "IC2") (pin "H15") (pinfunction "GND4_H15") (pintype "bidirectional"))
      (node (ref "IC2") (pin "H8") (pinfunction "GND_TV_H8") (pintype "bidirectional"))
      (node (ref "IC2") (pin "J13") (pinfunction "GND5_J13") (pintype "bidirectional"))
      (node (ref "IC2") (pin "J16") (pinfunction "GND6_J16") (pintype "bidirectional"))
      (node (ref "IC2") (pin "J9") (pinfunction "GND7_J9") (pintype "bidirectional"))
      (node (ref "IC2") (pin "K13") (pinfunction "GND8_K13") (pintype "bidirectional"))
      (node (ref "IC2") (pin "K14") (pinfunction "GND9_K14") (pintype "bidirectional"))
      (node (ref "IC2") (pin "K15") (pinfunction "GND10_K15") (pintype "bidirectional"))
      (node (ref "IC2") (pin "K16") (pinfunction "GND11_K16") (pintype "bidirectional"))
      (node (ref "IC2") (pin "K7") (pinfunction "GND12_K7") (pintype "bidirectional"))
      (node (ref "IC2") (pin "K8") (pinfunction "GND13_K8") (pintype "bidirectional"))
      (node (ref "IC2") (pin "K9") (pinfunction "GND14_K9") (pintype "bidirectional"))
      (node (ref "IC2") (pin "L15") (pinfunction "GND15_L15") (pintype "bidirectional"))
      (node (ref "IC2") (pin "L8") (pinfunction "GND16_L8") (pintype "bidirectional"))
      (node (ref "IC2") (pin "L9") (pinfunction "GND17_L9") (pintype "bidirectional"))
      (node (ref "IC2") (pin "M10") (pinfunction "GND18_M10") (pintype "bidirectional"))
      (node (ref "IC2") (pin "M11") (pinfunction "GND19_M11") (pintype "bidirectional"))
      (node (ref "IC2") (pin "M12") (pinfunction "GND20_M12") (pintype "bidirectional"))
      (node (ref "IC2") (pin "M13") (pinfunction "GND21_M13") (pintype "bidirectional"))
      (node (ref "IC2") (pin "M14") (pinfunction "GND22_M14") (pintype "bidirectional"))
      (node (ref "IC2") (pin "M15") (pinfunction "GND23_M15") (pintype "bidirectional"))
      (node (ref "IC2") (pin "M5") (pinfunction "HGND_M5") (pintype "bidirectional"))
      (node (ref "IC2") (pin "M7") (pinfunction "GND24_M7") (pintype "bidirectional"))
      (node (ref "IC2") (pin "M8") (pinfunction "GND25_M8") (pintype "bidirectional"))
      (node (ref "IC2") (pin "M9") (pinfunction "GND26_M9") (pintype "bidirectional"))
      (node (ref "IC2") (pin "N10") (pinfunction "GND27_N10") (pintype "bidirectional"))
      (node (ref "IC2") (pin "N11") (pinfunction "GND28_N11") (pintype "bidirectional"))
      (node (ref "IC2") (pin "N12") (pinfunction "GND29_N12") (pintype "bidirectional"))
      (node (ref "IC2") (pin "N13") (pinfunction "GND30_N13") (pintype "bidirectional"))
      (node (ref "IC2") (pin "N14") (pinfunction "GND31_N14") (pintype "bidirectional"))
      (node (ref "IC2") (pin "N15") (pinfunction "GND32_N15") (pintype "bidirectional"))
      (node (ref "IC2") (pin "N7") (pinfunction "GND33_N7") (pintype "bidirectional"))
      (node (ref "IC2") (pin "N9") (pinfunction "GND34_N9") (pintype "bidirectional"))
      (node (ref "IC2") (pin "P10") (pinfunction "GND35_P10") (pintype "bidirectional"))
      (node (ref "IC2") (pin "P11") (pinfunction "GND36_P11") (pintype "bidirectional"))
      (node (ref "IC2") (pin "P12") (pinfunction "GND37_P12") (pintype "bidirectional"))
      (node (ref "IC2") (pin "P13") (pinfunction "GND38_P13") (pintype "bidirectional"))
      (node (ref "IC2") (pin "P14") (pinfunction "GND39_P14") (pintype "bidirectional"))
      (node (ref "IC2") (pin "P15") (pinfunction "GND40_P15") (pintype "bidirectional"))
      (node (ref "IC2") (pin "R10") (pinfunction "GND41_R10") (pintype "bidirectional"))
      (node (ref "IC2") (pin "R11") (pinfunction "GND42_R11") (pintype "bidirectional"))
      (node (ref "IC2") (pin "R12") (pinfunction "GND43_R12") (pintype "bidirectional"))
      (node (ref "IC2") (pin "R13") (pinfunction "GND44_R13") (pintype "bidirectional"))
      (node (ref "IC2") (pin "R14") (pinfunction "GND45_R14") (pintype "bidirectional"))
      (node (ref "IC2") (pin "R9") (pinfunction "GND46_R9") (pintype "bidirectional"))
      (node (ref "IC2") (pin "T11") (pinfunction "GND47_T11") (pintype "bidirectional"))
      (node (ref "IC2") (pin "T9") (pinfunction "GND_CPUXFB_T9") (pintype "bidirectional"))
      (node (ref "IC2") (pin "U3") (pinfunction "AGND_U3") (pintype "bidirectional"))
      (node (ref "IC3") (pin "2") (pinfunction "GND_2") (pintype "bidirectional"))
      (node (ref "IC4") (pin "A9") (pinfunction "VSS_1_A9") (pintype "bidirectional"))
      (node (ref "IC4") (pin "B1") (pinfunction "VSSQ_1_B1") (pintype "bidirectional"))
      (node (ref "IC4") (pin "B3") (pinfunction "VSS_2_B3") (pintype "bidirectional"))
      (node (ref "IC4") (pin "B9") (pinfunction "VSSQ_2_B9") (pintype "bidirectional"))
      (node (ref "IC4") (pin "D1") (pinfunction "VSSQ_3_D1") (pintype "bidirectional"))
      (node (ref "IC4") (pin "D8") (pinfunction "VSSQ_4_D8") (pintype "bidirectional"))
      (node (ref "IC4") (pin "E1") (pinfunction "VSS_3_E1") (pintype "bidirectional"))
      (node (ref "IC4") (pin "E2") (pinfunction "VSSQ_5_E2") (pintype "bidirectional"))
      (node (ref "IC4") (pin "E8") (pinfunction "VSSQ_6_E8") (pintype "bidirectional"))
      (node (ref "IC4") (pin "F9") (pinfunction "VSSQ_7_F9") (pintype "bidirectional"))
      (node (ref "IC4") (pin "G1") (pinfunction "VSSQ_8_G1") (pintype "bidirectional"))
      (node (ref "IC4") (pin "G8") (pinfunction "VSS_4_G8") (pintype "bidirectional"))
      (node (ref "IC4") (pin "G9") (pinfunction "VSSQ_9_G9") (pintype "bidirectional"))
      (node (ref "IC4") (pin "J2") (pinfunction "VSS_5_J2") (pintype "bidirectional"))
      (node (ref "IC4") (pin "J8") (pinfunction "VSS_6_J8") (pintype "bidirectional"))
      (node (ref "IC4") (pin "M1") (pinfunction "VSS_7_M1") (pintype "bidirectional"))
      (node (ref "IC4") (pin "M9") (pinfunction "VSS_8_M9") (pintype "bidirectional"))
      (node (ref "IC4") (pin "P1") (pinfunction "VSS_9_P1") (pintype "bidirectional"))
      (node (ref "IC4") (pin "P9") (pinfunction "VSS_10_P9") (pintype "bidirectional"))
      (node (ref "IC4") (pin "T1") (pinfunction "VSS_11_T1") (pintype "bidirectional"))
      (node (ref "IC4") (pin "T9") (pinfunction "VSS_12_T9") (pintype "bidirectional"))
      (node (ref "IC5") (pin "2") (pinfunction "GND_2") (pintype "bidirectional"))
      (node (ref "IC6") (pin "2") (pinfunction "GND_2") (pintype "bidirectional"))
      (node (ref "IC7") (pin "2") (pinfunction "GND_2") (pintype "bidirectional"))
      (node (ref "IC8") (pin "1") (pinfunction "GND_1") (pintype "power_in"))
      (node (ref "IC9") (pin "2") (pinfunction "GND_2") (pintype "bidirectional"))
      (node (ref "JP3") (pin "14") (pinfunction "14_14") (pintype "passive"))
      (node (ref "JP3") (pin "15") (pinfunction "15_15") (pintype "passive"))
      (node (ref "LED4") (pin "4") (pinfunction "VSS_4") (pintype "bidirectional"))
      (node (ref "Q4") (pin "2") (pinfunction "S_2") (pintype "bidirectional"))
      (node (ref "R10") (pin "1") (pinfunction "1_1") (pintype "bidirectional"))
      (node (ref "R12") (pin "1") (pinfunction "1_1") (pintype "bidirectional"))
      (node (ref "R13") (pin "1") (pinfunction "1_1") (pintype "bidirectional"))
      (node (ref "R14") (pin "1") (pinfunction "1_1") (pintype "bidirectional"))
      (node (ref "R15") (pin "1") (pinfunction "1_1") (pintype "bidirectional"))
      (node (ref "R17") (pin "1") (pinfunction "1_1") (pintype "bidirectional"))
      (node (ref "R20") (pin "2") (pinfunction "2_2") (pintype "bidirectional"))
      (node (ref "R21") (pin "2") (pinfunction "2_2") (pintype "bidirectional"))
      (node (ref "R25") (pin "1") (pinfunction "1_1") (pintype "bidirectional"))
      (node (ref "R27") (pin "2") (pinfunction "2_2") (pintype "bidirectional"))
      (node (ref "R28") (pin "2") (pinfunction "2_2") (pintype "bidirectional"))
      (node (ref "R29") (pin "1") (pinfunction "1_1") (pintype "bidirectional"))
      (node (ref "R30") (pin "1") (pinfunction "1_1") (pintype "bidirectional"))
      (node (ref "R37") (pin "2") (pinfunction "2_2") (pintype "bidirectional"))
      (node (ref "R41") (pin "2") (pinfunction "2_2") (pintype "bidirectional"))
      (node (ref "R42") (pin "2") (pinfunction "2_2") (pintype "bidirectional"))
      (node (ref "R43") (pin "1") (pinfunction "1_1") (pintype "bidirectional"))
      (node (ref "R44") (pin "1") (pinfunction "1_1") (pintype "bidirectional"))
      (node (ref "R46") (pin "1") (pinfunction "1_1") (pintype "bidirectional"))
      (node (ref "S1") (pin "3") (pinfunction "3_3") (pintype "passive"))
      (node (ref "S1") (pin "4") (pinfunction "4_4") (pintype "passive"))
      (node (ref "S2") (pin "3") (pinfunction "3_3") (pintype "passive"))
      (node (ref "S2") (pin "4") (pinfunction "4_4") (pintype "passive"))
      (node (ref "U1") (pin "1") (pinfunction "GND1_1") (pintype "bidirectional"))
      (node (ref "U1") (pin "20") (pinfunction "GND3_20") (pintype "bidirectional"))
      (node (ref "U1") (pin "3") (pinfunction "GND2_3") (pintype "bidirectional"))
      (node (ref "U1") (pin "31") (pinfunction "GND4_31") (pintype "bidirectional"))
      (node (ref "U1") (pin "33") (pinfunction "GND5_33") (pintype "bidirectional"))
      (node (ref "U1") (pin "36") (pinfunction "GND6_36") (pintype "bidirectional"))
      (node (ref "U2") (pin "20") (pinfunction "PB2_20") (pintype "bidirectional"))
      (node (ref "U2") (pin "23") (pinfunction "VSS_23") (pintype "bidirectional"))
      (node (ref "U2") (pin "35") (pinfunction "VSS_35") (pintype "bidirectional"))
      (node (ref "U2") (pin "47") (pinfunction "VSS_47") (pintype "bidirectional"))
      (node (ref "U2") (pin "49") (pinfunction "VSS_49") (pintype "bidirectional"))
      (node (ref "U2") (pin "8") (pinfunction "VSSA/VREF-_8") (pintype "bidirectional"))
      (node (ref "X1") (pin "CGND1") (pinfunction "SGND1_CGND1") (pintype "bidirectional"))
      (node (ref "X1") (pin "CGND2") (pinfunction "SGND2_CGND2") (pintype "bidirectional"))
      (node (ref "X1") (pin "CGND3") (pinfunction "SGND3_CGND3") (pintype "bidirectional"))
      (node (ref "X1") (pin "CGND4") (pinfunction "SGND4_CGND4") (pintype "bidirectional"))
      (node (ref "X1") (pin "CGND5") (pinfunction "SGND5_CGND5") (pintype "bidirectional"))
      (node (ref "X1") (pin "CGND6") (pinfunction "SGND6_CGND6") (pintype "bidirectional"))
      (node (ref "X1") (pin "GND") (pinfunction "GND_GND") (pintype "input"))
      (node (ref "Y1") (pin "2") (pinfunction "2_2") (pintype "passive"))
      (node (ref "Y1") (pin "4") (pinfunction "4_4") (pintype "passive"))
      (node (ref "Y2") (pin "2") (pinfunction "3_2") (pintype "passive"))
      (node (ref "Y2") (pin "4") (pinfunction "3_4") (pintype "passive"))
      (node (ref "Y3") (pin "GND") (pinfunction "GND_GND") (pintype "passive"))
      (node (ref "Z1") (pin "1") (pinfunction "1_1") (pintype "passive"))
      (node (ref "Z2") (pin "1") (pinfunction "1_1") (pintype "passive"))
      (node (ref "Z3") (pin "1") (pinfunction "1_1") (pintype "passive"))
      (node (ref "Z4") (pin "1") (pinfunction "1_1") (pintype "passive"))
    )
    (net (code "47") (name "GPIOA15{slash}SPI1_MOSI") (class "Default")
      (node (ref "IC2") (pin "F14") (pinfunction "PA15/SPI1_MOSI/UART3_RTS/PA_EINT15_F14") (pintype "bidirectional"))
      (node (ref "R39") (pin "1") (pinfunction "1_1") (pintype "bidirectional"))
    )
    (net (code "48") (name "H3_UART1_RX") (class "Default")
      (node (ref "IC2") (pin "D3") (pinfunction "PG7/UART1_RX/PG_EINT7_D3") (pintype "bidirectional"))
      (node (ref "U2") (pin "30") (pinfunction "PA9_30") (pintype "bidirectional"))
    )
    (net (code "49") (name "H3_UART1_TX") (class "Default")
      (node (ref "IC2") (pin "G4") (pinfunction "PG6/UART1_TX/PG_EINT6_G4") (pintype "bidirectional"))
      (node (ref "U2") (pin "31") (pinfunction "PA10_31") (pintype "bidirectional"))
    )
    (net (code "50") (name "KERNEL_LED") (class "Default")
      (node (ref "IC2") (pin "B21") (pinfunction "PD6/RGMII_NULL/MII_RXERR/RMII_RXER_B21") (pintype "bidirectional"))
      (node (ref "LED3") (pin "A") (pinfunction "A_A") (pintype "passive"))
    )
    (net (code "51") (name "MCU_3.3V") (class "Default")
      (node (ref "C58") (pin "1") (pinfunction "P$1_1") (pintype "bidirectional"))
      (node (ref "C59") (pin "1") (pinfunction "P$1_1") (pintype "bidirectional"))
      (node (ref "C64") (pin "1") (pinfunction "P$1_1") (pintype "bidirectional"))
      (node (ref "C67") (pin "1") (pinfunction "P$1_1") (pintype "bidirectional"))
      (node (ref "C70") (pin "1") (pinfunction "P$1_1") (pintype "bidirectional"))
      (node (ref "C79") (pin "1") (pinfunction "P$1_1") (pintype "bidirectional"))
      (node (ref "C82") (pin "1") (pinfunction "P$1_1") (pintype "bidirectional"))
      (node (ref "C86") (pin "1") (pinfunction "P$1_1") (pintype "bidirectional"))
      (node (ref "C91") (pin "1") (pinfunction "P$1_1") (pintype "bidirectional"))
      (node (ref "JP3") (pin "16") (pinfunction "16_16") (pintype "passive"))
      (node (ref "JP3") (pin "17") (pinfunction "17_17") (pintype "passive"))
      (node (ref "L3") (pin "2") (pinfunction "2_2") (pintype "bidirectional"))
      (node (ref "R19") (pin "1") (pinfunction "1_1") (pintype "bidirectional"))
      (node (ref "R32") (pin "2") (pinfunction "2_2") (pintype "bidirectional"))
      (node (ref "U2") (pin "1") (pinfunction "VBAT_1") (pintype "bidirectional"))
      (node (ref "U2") (pin "24") (pinfunction "VDD_24") (pintype "bidirectional"))
      (node (ref "U2") (pin "36") (pinfunction "VDD_36") (pintype "bidirectional"))
      (node (ref "U2") (pin "48") (pinfunction "VDD_48") (pintype "bidirectional"))
      (node (ref "U2") (pin "9") (pinfunction "VDDA/VREF+_9") (pintype "bidirectional"))
    )
    (net (code "52") (name "MCU_REG_EN") (class "Default")
      (node (ref "IC2") (pin "H17") (pinfunction "PD1/RGMII_RXD2/MII_RXD2/RMII_NULL/DI_RX_H17") (pintype "bidirectional"))
      (node (ref "IC5") (pin "1") (pinfunction "EN_1") (pintype "bidirectional"))
      (node (ref "R21") (pin "1") (pinfunction "1_1") (pintype "bidirectional"))
    )
    (net (code "53") (name "MCU_RST") (class "Default")
      (node (ref "C36") (pin "2") (pinfunction "P$2_2") (pintype "bidirectional"))
      (node (ref "IC2") (pin "B1") (pinfunction "PG13/PCM1_DIN/PG_EINT13_B1") (pintype "bidirectional"))
      (node (ref "JP3") (pin "11") (pinfunction "11_11") (pintype "passive"))
      (node (ref "R19") (pin "2") (pinfunction "2_2") (pintype "bidirectional"))
      (node (ref "U2") (pin "7") (pinfunction "NRST_7") (pintype "bidirectional"))
    )
    (net (code "54") (name "Net-(ANT1-FEED)") (class "Default")
      (node (ref "ANT1") (pin "1") (pinfunction "FEED_1") (pintype "input"))
      (node (ref "C27") (pin "2") (pinfunction "P$2_2") (pintype "bidirectional"))
      (node (ref "L2") (pin "2") (pinfunction "2_2") (pintype "passive"))
    )
    (net (code "55") (name "Net-(C14-P$2)") (class "Default")
      (node (ref "C14") (pin "2") (pinfunction "P$2_2") (pintype "bidirectional"))
      (node (ref "U1") (pin "10") (pinfunction "XTAL_IN_10") (pintype "bidirectional"))
      (node (ref "Y1") (pin "3") (pinfunction "3_3") (pintype "passive"))
    )
    (net (code "56") (name "Net-(C15-P$2)") (class "Default")
      (node (ref "C15") (pin "2") (pinfunction "P$2_2") (pintype "bidirectional"))
      (node (ref "U1") (pin "11") (pinfunction "XTAL_OUT_11") (pintype "bidirectional"))
      (node (ref "Y1") (pin "1") (pinfunction "1_1") (pintype "passive"))
    )
    (net (code "57") (name "Net-(C16-P$1)") (class "Default")
      (node (ref "C16") (pin "1") (pinfunction "P$1_1") (pintype "bidirectional"))
      (node (ref "IC3") (pin "1") (pinfunction "OUT_1") (pintype "bidirectional"))
      (node (ref "Q1") (pin "3") (pinfunction "D_3") (pintype "bidirectional"))
      (node (ref "Q2") (pin "1") (pinfunction "EMITTER_TR1_1") (pintype "bidirectional"))
      (node (ref "X1") (pin "VBUS") (pinfunction "VBUS_VBUS") (pintype "input"))
      (node (ref "Z4") (pin "2") (pinfunction "2_2") (pintype "passive"))
    )
    (net (code "58") (name "Net-(C22-P$2)") (class "Default")
      (node (ref "C22") (pin "2") (pinfunction "P$2_2") (pintype "bidirectional"))
      (node (ref "L2") (pin "1") (pinfunction "1_1") (pintype "passive"))
      (node (ref "U1") (pin "2") (pinfunction "WL_BT_ANT_2") (pintype "bidirectional"))
    )
    (net (code "59") (name "Net-(C25-P$1)") (class "Default")
      (node (ref "C25") (pin "1") (pinfunction "P$1_1") (pintype "bidirectional"))
      (node (ref "L1") (pin "2") (pinfunction "2_2") (pintype "bidirectional"))
      (node (ref "U1") (pin "23") (pinfunction "VIN_LDO_23") (pintype "bidirectional"))
    )
    (net (code "60") (name "Net-(C39-P$1)") (class "Default")
      (node (ref "C39") (pin "1") (pinfunction "P$1_1") (pintype "bidirectional"))
      (node (ref "U2") (pin "22") (pinfunction "VCAP1_22") (pintype "bidirectional"))
    )
    (net (code "61") (name "Net-(C49-P$1)") (class "Default")
      (node (ref "C49") (pin "1") (pinfunction "P$1_1") (pintype "bidirectional"))
      (node (ref "IC2") (pin "V5") (pinfunction "X32KIN_V5") (pintype "bidirectional"))
      (node (ref "Q3") (pin "1") (pinfunction "1_1") (pintype "passive"))
      (node (ref "R24") (pin "2") (pinfunction "2_2") (pintype "bidirectional"))
    )
    (net (code "62") (name "Net-(C50-P$1)") (class "Default")
      (node (ref "C50") (pin "1") (pinfunction "P$1_1") (pintype "bidirectional"))
      (node (ref "IC2") (pin "U4") (pinfunction "X32KOUT_U4") (pintype "bidirectional"))
      (node (ref "Q3") (pin "2") (pinfunction "2_2") (pintype "passive"))
      (node (ref "R24") (pin "1") (pinfunction "1_1") (pintype "bidirectional"))
    )
    (net (code "63") (name "Net-(C60-P$1)") (class "Default")
      (node (ref "C60") (pin "1") (pinfunction "P$1_1") (pintype "bidirectional"))
      (node (ref "IC2") (pin "H11") (pinfunction "VDD_EFUSEBP_H11") (pintype "bidirectional"))
    )
    (net (code "64") (name "Net-(C103-P$2)") (class "Default")
      (node (ref "C103") (pin "2") (pinfunction "P$2_2") (pintype "bidirectional"))
      (node (ref "IC10") (pin "7") (pinfunction "FB_7") (pintype "bidirectional"))
      (node (ref "R46") (pin "2") (pinfunction "2_2") (pintype "bidirectional"))
      (node (ref "R47") (pin "1") (pinfunction "1_1") (pintype "bidirectional"))
      (node (ref "R48") (pin "2") (pinfunction "2_2") (pintype "bidirectional"))
    )
    (net (code "65") (name "Net-(IC2C-SZQ)") (class "Default")
      (node (ref "IC2") (pin "V10") (pinfunction "SZQ_V10") (pintype "bidirectional"))
      (node (ref "R43") (pin "2") (pinfunction "2_2") (pintype "bidirectional"))
    )
    (net (code "66") (name "Net-(IC2G-KEYADC)") (class "Default")
      (node (ref "IC2") (pin "AA5") (pinfunction "KEYADC_AA5") (pintype "bidirectional"))
      (node (ref "R33") (pin "2") (pinfunction "2_2") (pintype "bidirectional"))
    )
    (net (code "67") (name "Net-(IC2G-NMI)") (class "Default")
      (node (ref "IC2") (pin "AA6") (pinfunction "NMI_AA6") (pintype "bidirectional"))
      (node (ref "R26") (pin "2") (pinfunction "2_2") (pintype "bidirectional"))
    )
    (net (code "68") (name "Net-(IC3-ISET)") (class "Default")
      (node (ref "IC3") (pin "3") (pinfunction "ISET_3") (pintype "bidirectional"))
      (node (ref "R14") (pin "2") (pinfunction "2_2") (pintype "bidirectional"))
    )
    (net (code "69") (name "Net-(IC4-NC_4)") (class "Default")
      (node (ref "IC4") (pin "L9") (pinfunction "NC_4_L9") (pintype "bidirectional"))
      (node (ref "R28") (pin "1") (pinfunction "1_1") (pintype "bidirectional"))
    )
    (net (code "70") (name "Net-(IC4-ZQ)") (class "Default")
      (node (ref "IC4") (pin "L8") (pinfunction "ZQ_L8") (pintype "bidirectional"))
      (node (ref "R27") (pin "1") (pinfunction "1_1") (pintype "bidirectional"))
    )
    (net (code "71") (name "Net-(IC5-FB)") (class "Default")
      (node (ref "IC5") (pin "5") (pinfunction "FB_5") (pintype "bidirectional"))
      (node (ref "R25") (pin "2") (pinfunction "2_2") (pintype "bidirectional"))
      (node (ref "R32") (pin "1") (pinfunction "1_1") (pintype "bidirectional"))
    )
    (net (code "72") (name "Net-(IC5-LX)") (class "Default")
      (node (ref "IC5") (pin "3") (pinfunction "LX_3") (pintype "bidirectional"))
      (node (ref "L3") (pin "1") (pinfunction "1_1") (pintype "bidirectional"))
    )
    (net (code "73") (name "Net-(IC6-FB)") (class "Default")
      (node (ref "IC6") (pin "5") (pinfunction "FB_5") (pintype "bidirectional"))
      (node (ref "R29") (pin "2") (pinfunction "2_2") (pintype "bidirectional"))
      (node (ref "R34") (pin "1") (pinfunction "1_1") (pintype "bidirectional"))
    )
    (net (code "74") (name "Net-(IC6-LX)") (class "Default")
      (node (ref "IC6") (pin "3") (pinfunction "LX_3") (pintype "bidirectional"))
      (node (ref "L4") (pin "1") (pinfunction "1_1") (pintype "bidirectional"))
    )
    (net (code "75") (name "Net-(IC7-FB)") (class "Default")
      (node (ref "IC7") (pin "5") (pinfunction "FB_5") (pintype "bidirectional"))
      (node (ref "R30") (pin "2") (pinfunction "2_2") (pintype "bidirectional"))
      (node (ref "R35") (pin "1") (pinfunction "1_1") (pintype "bidirectional"))
    )
    (net (code "76") (name "Net-(IC7-LX)") (class "Default")
      (node (ref "IC7") (pin "3") (pinfunction "LX_3") (pintype "bidirectional"))
      (node (ref "L5") (pin "1") (pinfunction "1_1") (pintype "bidirectional"))
    )
    (net (code "77") (name "Net-(IC9-FB)") (class "Default")
      (node (ref "IC9") (pin "5") (pinfunction "FB_5") (pintype "bidirectional"))
      (node (ref "R44") (pin "2") (pinfunction "2_2") (pintype "bidirectional"))
      (node (ref "R45") (pin "1") (pinfunction "1_1") (pintype "bidirectional"))
    )
    (net (code "78") (name "Net-(IC9-LX)") (class "Default")
      (node (ref "IC9") (pin "3") (pinfunction "LX_3") (pintype "bidirectional"))
      (node (ref "L6") (pin "1") (pinfunction "1_1") (pintype "bidirectional"))
    )
    (net (code "79") (name "Net-(IC10-SW)") (class "Default")
      (node (ref "IC10") (pin "3") (pinfunction "SW_3") (pintype "bidirectional"))
      (node (ref "L7") (pin "1") (pinfunction "1_1") (pintype "bidirectional"))
    )
    (net (code "80") (name "Net-(JP3-Pad12)") (class "Default")
      (node (ref "JP3") (pin "12") (pinfunction "12_12") (pintype "passive"))
      (node (ref "R51") (pin "2") (pinfunction "2_2") (pintype "bidirectional"))
    )
    (net (code "81") (name "Net-(JP3-Pad13)") (class "Default")
      (node (ref "JP3") (pin "13") (pinfunction "13_13") (pintype "passive"))
      (node (ref "R49") (pin "2") (pinfunction "2_2") (pintype "bidirectional"))
    )
    (net (code "82") (name "Net-(LED1-PadK)") (class "Default")
      (node (ref "LED1") (pin "K") (pinfunction "K_K") (pintype "passive"))
      (node (ref "R37") (pin "1") (pinfunction "1_1") (pintype "bidirectional"))
    )
    (net (code "83") (name "Net-(LED2-PadK)") (class "Default")
      (node (ref "LED2") (pin "K") (pinfunction "K_K") (pintype "passive"))
      (node (ref "R41") (pin "1") (pinfunction "1_1") (pintype "bidirectional"))
    )
    (net (code "84") (name "Net-(LED3-PadK)") (class "Default")
      (node (ref "LED3") (pin "K") (pinfunction "K_K") (pintype "passive"))
      (node (ref "R42") (pin "1") (pinfunction "1_1") (pintype "bidirectional"))
    )
    (net (code "85") (name "Net-(LED4-DIN)") (class "Default")
      (node (ref "LED4") (pin "2") (pinfunction "DIN_2") (pintype "bidirectional"))
      (node (ref "R39") (pin "2") (pinfunction "2_2") (pintype "bidirectional"))
    )
    (net (code "86") (name "Net-(Q1-G)") (class "Default")
      (node (ref "Q1") (pin "1") (pinfunction "G_1") (pintype "bidirectional"))
      (node (ref "Q2") (pin "3") (pinfunction "COLLECTOR_TR2_3") (pintype "bidirectional"))
      (node (ref "R12") (pin "2") (pinfunction "2_2") (pintype "bidirectional"))
    )
    (net (code "87") (name "Net-(Q2-BASE_TR1)") (class "Default")
      (node (ref "Q2") (pin "2") (pinfunction "BASE_TR1_2") (pintype "bidirectional"))
      (node (ref "Q2") (pin "5") (pinfunction "BASE_TR2_5") (pintype "bidirectional"))
      (node (ref "Q2") (pin "6") (pinfunction "COLLECTOR_TR1_6") (pintype "bidirectional"))
      (node (ref "R13") (pin "2") (pinfunction "2_2") (pintype "bidirectional"))
    )
    (net (code "88") (name "Net-(Q4-D)") (class "Default")
      (node (ref "Q4") (pin "3") (pinfunction "D_3") (pintype "bidirectional"))
      (node (ref "R48") (pin "1") (pinfunction "1_1") (pintype "bidirectional"))
    )
    (net (code "89") (name "Net-(U1-BT_RST_N)") (class "Default")
      (node (ref "R10") (pin "2") (pinfunction "2_2") (pintype "bidirectional"))
      (node (ref "U1") (pin "34") (pinfunction "BT_RST_N_34") (pintype "bidirectional"))
    )
    (net (code "90") (name "Net-(U1-SDIO_DATA_CLK)") (class "Default")
      (node (ref "R9") (pin "1") (pinfunction "1_1") (pintype "bidirectional"))
      (node (ref "U1") (pin "17") (pinfunction "SDIO_DATA_CLK_17") (pintype "bidirectional"))
    )
    (net (code "91") (name "Net-(U1-VIN_LDO_OUT)") (class "Default")
      (node (ref "L1") (pin "1") (pinfunction "1_1") (pintype "bidirectional"))
      (node (ref "U1") (pin "21") (pinfunction "VIN_LDO_OUT_21") (pintype "bidirectional"))
    )
    (net (code "92") (name "Net-(U2-PH0{slash}OSC_IN)") (class "Default")
      (node (ref "U2") (pin "5") (pinfunction "PH0/OSC_IN_5") (pintype "bidirectional"))
      (node (ref "Y3") (pin "IN") (pinfunction "IN_IN") (pintype "passive"))
    )
    (net (code "93") (name "Net-(U2-PH1{slash}OSC_OUT)") (class "Default")
      (node (ref "U2") (pin "6") (pinfunction "PH1/OSC_OUT_6") (pintype "bidirectional"))
      (node (ref "Y3") (pin "OUT") (pinfunction "OUT_OUT") (pintype "passive"))
    )
    (net (code "94") (name "PWR_DRAM") (class "Default")
      (node (ref "IC2") (pin "A14") (pinfunction "PA21/PCM0_DIN/SIM_VPPPP/PA_EINT21_A14") (pintype "bidirectional"))
      (node (ref "IC6") (pin "1") (pinfunction "EN_1") (pintype "bidirectional"))
      (node (ref "R22") (pin "1") (pinfunction "1_1") (pintype "bidirectional"))
    )
    (net (code "95") (name "PWR_STB") (class "Default")
      (node (ref "IC10") (pin "8") (pinfunction "EN_8") (pintype "bidirectional"))
      (node (ref "IC2") (pin "A20") (pinfunction "PD4/RGMII_RXCK/MII_RXCK/RMII_NULL_A20") (pintype "bidirectional"))
      (node (ref "IC7") (pin "1") (pinfunction "EN_1") (pintype "bidirectional"))
      (node (ref "R23") (pin "1") (pinfunction "1_1") (pintype "bidirectional"))
    )
    (net (code "96") (name "RESET_SW") (class "Default")
      (node (ref "IC2") (pin "F13") (pinfunction "PA8/SIM_DATA/PA_EINT8_F13") (pintype "bidirectional"))
      (node (ref "R52") (pin "2") (pinfunction "2_2") (pintype "bidirectional"))
      (node (ref "S2") (pin "1") (pinfunction "1_1") (pintype "passive"))
      (node (ref "S2") (pin "2") (pinfunction "2_2") (pintype "passive"))
    )
    (net (code "97") (name "SA0") (class "Default")
      (node (ref "IC2") (pin "T17") (pinfunction "SA0_T17") (pintype "bidirectional"))
      (node (ref "IC4") (pin "N3") (pinfunction "A0_N3") (pintype "bidirectional"))
    )
    (net (code "98") (name "SA1") (class "Default")
      (node (ref "IC2") (pin "U18") (pinfunction "SA1_U18") (pintype "bidirectional"))
      (node (ref "IC4") (pin "P7") (pinfunction "A1_P7") (pintype "bidirectional"))
    )
    (net (code "99") (name "SA2") (class "Default")
      (node (ref "IC2") (pin "V19") (pinfunction "SA2_V19") (pintype "bidirectional"))
      (node (ref "IC4") (pin "P3") (pinfunction "A2_P3") (pintype "bidirectional"))
    )
    (net (code "100") (name "SA3") (class "Default")
      (node (ref "IC2") (pin "V20") (pinfunction "SA3_V20") (pintype "bidirectional"))
      (node (ref "IC4") (pin "N2") (pinfunction "A3_N2") (pintype "bidirectional"))
    )
    (net (code "101") (name "SA4") (class "Default")
      (node (ref "IC2") (pin "V21") (pinfunction "SA4_V21") (pintype "bidirectional"))
      (node (ref "IC4") (pin "P8") (pinfunction "A4_P8") (pintype "bidirectional"))
    )
    (net (code "102") (name "SA5") (class "Default")
      (node (ref "IC2") (pin "Y19") (pinfunction "SA5_Y19") (pintype "bidirectional"))
      (node (ref "IC4") (pin "P2") (pinfunction "A5_P2") (pintype "bidirectional"))
    )
    (net (code "103") (name "SA6") (class "Default")
      (node (ref "IC2") (pin "Y20") (pinfunction "SA6_Y20") (pintype "bidirectional"))
      (node (ref "IC4") (pin "R8") (pinfunction "A6_R8") (pintype "bidirectional"))
    )
    (net (code "104") (name "SA7") (class "Default")
      (node (ref "IC2") (pin "V15") (pinfunction "SA7_V15") (pintype "bidirectional"))
      (node (ref "IC4") (pin "R2") (pinfunction "A7_R2") (pintype "bidirectional"))
    )
    (net (code "105") (name "SA8") (class "Default")
      (node (ref "IC2") (pin "W18") (pinfunction "SA8_W18") (pintype "bidirectional"))
      (node (ref "IC4") (pin "T8") (pinfunction "A8_T8") (pintype "bidirectional"))
    )
    (net (code "106") (name "SA9") (class "Default")
      (node (ref "IC2") (pin "Y18") (pinfunction "SA9_Y18") (pintype "bidirectional"))
      (node (ref "IC4") (pin "R3") (pinfunction "A9_R3") (pintype "bidirectional"))
    )
    (net (code "107") (name "SA10") (class "Default")
      (node (ref "IC2") (pin "P19") (pinfunction "SA10_P19") (pintype "bidirectional"))
      (node (ref "IC4") (pin "L7") (pinfunction "A10/AP_L7") (pintype "bidirectional"))
    )
    (net (code "108") (name "SA11") (class "Default")
      (node (ref "IC2") (pin "N19") (pinfunction "SA11_N19") (pintype "bidirectional"))
      (node (ref "IC4") (pin "R7") (pinfunction "A11_R7") (pintype "bidirectional"))
    )
    (net (code "109") (name "SA12") (class "Default")
      (node (ref "IC2") (pin "R18") (pinfunction "SA12_R18") (pintype "bidirectional"))
      (node (ref "IC4") (pin "N7") (pinfunction "A12/~{BC}_N7") (pintype "bidirectional"))
    )
    (net (code "110") (name "SA13") (class "Default")
      (node (ref "IC2") (pin "V12") (pinfunction "SA13_V12") (pintype "bidirectional"))
      (node (ref "IC4") (pin "T3") (pinfunction "A13_T3") (pintype "bidirectional"))
    )
    (net (code "111") (name "SA14") (class "Default")
      (node (ref "IC2") (pin "N17") (pinfunction "SA14_N17") (pintype "bidirectional"))
      (node (ref "IC4") (pin "T7") (pinfunction "A14_T7") (pintype "bidirectional"))
    )
    (net (code "112") (name "SA15") (class "Default")
      (node (ref "IC2") (pin "R17") (pinfunction "SA15_R17") (pintype "bidirectional"))
      (node (ref "IC4") (pin "M7") (pinfunction "NC_5_M7") (pintype "bidirectional"))
    )
    (net (code "113") (name "SBA0") (class "Default")
      (node (ref "IC2") (pin "W17") (pinfunction "SBA0_W17") (pintype "bidirectional"))
      (node (ref "IC4") (pin "M2") (pinfunction "BA0_M2") (pintype "bidirectional"))
    )
    (net (code "114") (name "SBA1") (class "Default")
      (node (ref "IC2") (pin "T18") (pinfunction "SBA1_T18") (pintype "bidirectional"))
      (node (ref "IC4") (pin "N8") (pinfunction "BA1_N8") (pintype "bidirectional"))
    )
    (net (code "115") (name "SBA2") (class "Default")
      (node (ref "IC2") (pin "V17") (pinfunction "SBA2_V17") (pintype "bidirectional"))
      (node (ref "IC4") (pin "M3") (pinfunction "BA2_M3") (pintype "bidirectional"))
    )
    (net (code "116") (name "SCAS") (class "Default")
      (node (ref "IC2") (pin "U15") (pinfunction "SCAS_U15") (pintype "bidirectional"))
      (node (ref "IC4") (pin "K3") (pinfunction "~{CAS}_K3") (pintype "bidirectional"))
    )
    (net (code "117") (name "SCKE0") (class "Default")
      (node (ref "IC2") (pin "AA21") (pinfunction "SCKE0_AA21") (pintype "bidirectional"))
      (node (ref "IC4") (pin "K9") (pinfunction "CKE_K9") (pintype "bidirectional"))
    )
    (net (code "118") (name "SCKE1") (class "Default")
      (node (ref "IC2") (pin "Y21") (pinfunction "SCKE1_Y21") (pintype "bidirectional"))
      (node (ref "IC4") (pin "J9") (pinfunction "NC_2_J9") (pintype "bidirectional"))
    )
    (net (code "119") (name "SCK_N") (class "Default")
      (node (ref "IC2") (pin "AA20") (pinfunction "SCKB_AA20") (pintype "bidirectional"))
      (node (ref "IC4") (pin "K7") (pinfunction "~{CK}_K7") (pintype "bidirectional"))
      (node (ref "R18") (pin "1") (pinfunction "1_1") (pintype "bidirectional"))
    )
    (net (code "120") (name "SCK_P") (class "Default")
      (node (ref "IC2") (pin "AA19") (pinfunction "SCK_AA19") (pintype "bidirectional"))
      (node (ref "IC4") (pin "J7") (pinfunction "CK_J7") (pintype "bidirectional"))
      (node (ref "R18") (pin "2") (pinfunction "2_2") (pintype "bidirectional"))
    )
    (net (code "121") (name "SCS0") (class "Default")
      (node (ref "IC2") (pin "W20") (pinfunction "SCS0_W20") (pintype "bidirectional"))
      (node (ref "IC4") (pin "L2") (pinfunction "~{CS}_L2") (pintype "bidirectional"))
    )
    (net (code "122") (name "SCS1") (class "Default")
      (node (ref "IC2") (pin "W21") (pinfunction "SCS1_W21") (pintype "bidirectional"))
      (node (ref "IC4") (pin "L1") (pinfunction "NC_3_L1") (pintype "bidirectional"))
    )
    (net (code "123") (name "SDC1_CLK") (class "Default")
      (node (ref "IC2") (pin "J3") (pinfunction "PG0/SDC1_CLK/PG_EINT0_J3") (pintype "bidirectional"))
      (node (ref "R9") (pin "2") (pinfunction "2_2") (pintype "bidirectional"))
    )
    (net (code "124") (name "SDC1_CMD") (class "Default")
      (node (ref "IC2") (pin "L2") (pinfunction "PG1/SDC1_CMD/PG_EINT1_L2") (pintype "bidirectional"))
      (node (ref "R7") (pin "2") (pinfunction "2_2") (pintype "bidirectional"))
      (node (ref "U1") (pin "16") (pinfunction "SDIO_DATA_CMD_16") (pintype "bidirectional"))
    )
    (net (code "125") (name "SDC1_D0") (class "Default")
      (node (ref "IC2") (pin "H4") (pinfunction "PG2/SDC1_D0/PG_EINT2_H4") (pintype "bidirectional"))
      (node (ref "R5") (pin "2") (pinfunction "2_2") (pintype "bidirectional"))
      (node (ref "U1") (pin "18") (pinfunction "SDIO_DATA_0_18") (pintype "bidirectional"))
    )
    (net (code "126") (name "SDC1_D1") (class "Default")
      (node (ref "IC2") (pin "F3") (pinfunction "PG3/SDC1_D1/PG_EINT3_F3") (pintype "bidirectional"))
      (node (ref "R4") (pin "2") (pinfunction "2_2") (pintype "bidirectional"))
      (node (ref "U1") (pin "19") (pinfunction "SDIO_DATA_1_19") (pintype "bidirectional"))
    )
    (net (code "127") (name "SDC1_D2") (class "Default")
      (node (ref "IC2") (pin "C2") (pinfunction "PG4/SDC1_D2/PG_EINT4_C2") (pintype "bidirectional"))
      (node (ref "R2") (pin "2") (pinfunction "2_2") (pintype "bidirectional"))
      (node (ref "U1") (pin "14") (pinfunction "SDIO_DATA_2_14") (pintype "bidirectional"))
    )
    (net (code "128") (name "SDC1_D3") (class "Default")
      (node (ref "IC2") (pin "C1") (pinfunction "PG5/SDC1_D3/PG_EINT5_C1") (pintype "bidirectional"))
      (node (ref "R1") (pin "2") (pinfunction "2_2") (pintype "bidirectional"))
      (node (ref "U1") (pin "15") (pinfunction "SDIO_DATA_3_15") (pintype "bidirectional"))
    )
    (net (code "129") (name "SDQ0") (class "Default")
      (node (ref "IC2") (pin "N20") (pinfunction "SDQ0_N20") (pintype "bidirectional"))
      (node (ref "IC4") (pin "F7") (pinfunction "DQL1_F7") (pintype "bidirectional"))
    )
    (net (code "130") (name "SDQ1") (class "Default")
      (node (ref "IC2") (pin "P21") (pinfunction "SDQ1_P21") (pintype "bidirectional"))
      (node (ref "IC4") (pin "H8") (pinfunction "DQL5_H8") (pintype "bidirectional"))
    )
    (net (code "131") (name "SDQ2") (class "Default")
      (node (ref "IC2") (pin "P20") (pinfunction "SDQ2_P20") (pintype "bidirectional"))
      (node (ref "IC4") (pin "F8") (pinfunction "DQL3_F8") (pintype "bidirectional"))
    )
    (net (code "132") (name "SDQ3") (class "Default")
      (node (ref "IC2") (pin "U21") (pinfunction "SDQ3_U21") (pintype "bidirectional"))
      (node (ref "IC4") (pin "H3") (pinfunction "DQL4_H3") (pintype "bidirectional"))
    )
    (net (code "133") (name "SDQ4") (class "Default")
      (node (ref "IC2") (pin "R19") (pinfunction "SDQ4_R19") (pintype "bidirectional"))
      (node (ref "IC4") (pin "H7") (pinfunction "DQL7_H7") (pintype "bidirectional"))
    )
    (net (code "134") (name "SDQ5") (class "Default")
      (node (ref "IC2") (pin "T20") (pinfunction "SDQ5_T20") (pintype "bidirectional"))
      (node (ref "IC4") (pin "E3") (pinfunction "DQL0_E3") (pintype "bidirectional"))
    )
    (net (code "135") (name "SDQ6") (class "Default")
      (node (ref "IC2") (pin "U19") (pinfunction "SDQ6_U19") (pintype "bidirectional"))
      (node (ref "IC4") (pin "G2") (pinfunction "DQL6_G2") (pintype "bidirectional"))
    )
    (net (code "136") (name "SDQ7") (class "Default")
      (node (ref "IC2") (pin "U20") (pinfunction "SDQ7_U20") (pintype "bidirectional"))
      (node (ref "IC4") (pin "F2") (pinfunction "DQL2_F2") (pintype "bidirectional"))
    )
    (net (code "137") (name "SDQ8") (class "Default")
      (node (ref "IC2") (pin "J19") (pinfunction "SDQ8_J19") (pintype "bidirectional"))
      (node (ref "IC4") (pin "A7") (pinfunction "DQU4_A7") (pintype "bidirectional"))
    )
    (net (code "138") (name "SDQ9") (class "Default")
      (node (ref "IC2") (pin "H20") (pinfunction "SDQ9_H20") (pintype "bidirectional"))
      (node (ref "IC4") (pin "A2") (pinfunction "DQU5_A2") (pintype "bidirectional"))
    )
    (net (code "139") (name "SDQ10") (class "Default")
      (node (ref "IC2") (pin "H21") (pinfunction "SDQ10_H21") (pintype "bidirectional"))
      (node (ref "IC4") (pin "A3") (pinfunction "DQU7_A3") (pintype "bidirectional"))
    )
    (net (code "140") (name "SDQ11") (class "Default")
      (node (ref "IC2") (pin "J21") (pinfunction "SDQ11_J21") (pintype "bidirectional"))
      (node (ref "IC4") (pin "B8") (pinfunction "DQU6_B8") (pintype "bidirectional"))
    )
    (net (code "141") (name "SDQ12") (class "Default")
      (node (ref "IC2") (pin "L20") (pinfunction "SDQ12_L20") (pintype "bidirectional"))
      (node (ref "IC4") (pin "C8") (pinfunction "DQU2_C8") (pintype "bidirectional"))
    )
    (net (code "142") (name "SDQ13") (class "Default")
      (node (ref "IC2") (pin "L21") (pinfunction "SDQ13_L21") (pintype "bidirectional"))
      (node (ref "IC4") (pin "D7") (pinfunction "DQU0_D7") (pintype "bidirectional"))
    )
    (net (code "143") (name "SDQ14") (class "Default")
      (node (ref "IC2") (pin "M21") (pinfunction "SDQ14_M21") (pintype "bidirectional"))
      (node (ref "IC4") (pin "C3") (pinfunction "DQU1_C3") (pintype "bidirectional"))
    )
    (net (code "144") (name "SDQ15") (class "Default")
      (node (ref "IC2") (pin "M19") (pinfunction "SDQ15_M19") (pintype "bidirectional"))
      (node (ref "IC4") (pin "C2") (pinfunction "DQU3_C2") (pintype "bidirectional"))
    )
    (net (code "145") (name "SDQM0") (class "Default")
      (node (ref "IC2") (pin "M20") (pinfunction "SDQM0_M20") (pintype "bidirectional"))
      (node (ref "IC4") (pin "E7") (pinfunction "DML_E7") (pintype "bidirectional"))
    )
    (net (code "146") (name "SDQM1") (class "Default")
      (node (ref "IC2") (pin "G20") (pinfunction "SDQM1_G20") (pintype "bidirectional"))
      (node (ref "IC4") (pin "D3") (pinfunction "DMU_D3") (pintype "bidirectional"))
    )
    (net (code "147") (name "SDQS0_N") (class "Default")
      (node (ref "IC2") (pin "R21") (pinfunction "SDQSB0_R21") (pintype "bidirectional"))
      (node (ref "IC4") (pin "G3") (pinfunction "~{DQSL}_G3") (pintype "bidirectional"))
    )
    (net (code "148") (name "SDQS0_P") (class "Default")
      (node (ref "IC2") (pin "R20") (pinfunction "SDQS0_R20") (pintype "bidirectional"))
      (node (ref "IC4") (pin "F3") (pinfunction "DQSL_F3") (pintype "bidirectional"))
    )
    (net (code "149") (name "SDQS1_N") (class "Default")
      (node (ref "IC2") (pin "J20") (pinfunction "SDQSB1_J20") (pintype "bidirectional"))
      (node (ref "IC4") (pin "B7") (pinfunction "~{DQSU}_B7") (pintype "bidirectional"))
    )
    (net (code "150") (name "SDQS1_P") (class "Default")
      (node (ref "IC2") (pin "K20") (pinfunction "SDQS1_K20") (pintype "bidirectional"))
      (node (ref "IC4") (pin "C7") (pinfunction "DQSU_C7") (pintype "bidirectional"))
    )
    (net (code "151") (name "SETUP_SW") (class "Default")
      (node (ref "IC2") (pin "A13") (pinfunction "PA20/PCM0_DOUT/SIM_VPPEN/PA_EINT20_A13") (pintype "bidirectional"))
      (node (ref "IC2") (pin "W6") (pinfunction "UBOOT_W6") (pintype "bidirectional"))
      (node (ref "R40") (pin "2") (pinfunction "2_2") (pintype "bidirectional"))
      (node (ref "S1") (pin "1") (pinfunction "1_1") (pintype "passive"))
      (node (ref "S1") (pin "2") (pinfunction "2_2") (pintype "passive"))
    )
    (net (code "152") (name "SODT0") (class "Default")
      (node (ref "IC2") (pin "W11") (pinfunction "SODT0_W11") (pintype "bidirectional"))
      (node (ref "IC4") (pin "K1") (pinfunction "ODT_K1") (pintype "bidirectional"))
    )
    (net (code "153") (name "SODT1") (class "Default")
      (node (ref "IC2") (pin "V11") (pinfunction "SODT1_V11") (pintype "bidirectional"))
      (node (ref "IC4") (pin "J1") (pinfunction "NC_1_J1") (pintype "bidirectional"))
    )
    (net (code "154") (name "SRAS") (class "Default")
      (node (ref "IC2") (pin "V13") (pinfunction "SRAS_V13") (pintype "bidirectional"))
      (node (ref "IC4") (pin "J3") (pinfunction "~{RAS}_J3") (pintype "bidirectional"))
    )
    (net (code "155") (name "SRST") (class "Default")
      (node (ref "IC2") (pin "U16") (pinfunction "SRST_U16") (pintype "bidirectional"))
      (node (ref "IC4") (pin "T2") (pinfunction "~{RESET}_T2") (pintype "bidirectional"))
    )
    (net (code "156") (name "SVREF") (class "Default")
      (node (ref "C104") (pin "1") (pinfunction "P$1_1") (pintype "bidirectional"))
      (node (ref "C37") (pin "2") (pinfunction "P$2_2") (pintype "bidirectional"))
      (node (ref "C38") (pin "1") (pinfunction "P$1_1") (pintype "bidirectional"))
      (node (ref "C51") (pin "1") (pinfunction "P$1_1") (pintype "bidirectional"))
      (node (ref "IC2") (pin "T16") (pinfunction "SVREF_T16") (pintype "bidirectional"))
      (node (ref "IC4") (pin "H1") (pinfunction "VREFDQ_H1") (pintype "bidirectional"))
      (node (ref "IC4") (pin "M8") (pinfunction "VREFCA_M8") (pintype "bidirectional"))
      (node (ref "R16") (pin "1") (pinfunction "1_1") (pintype "bidirectional"))
      (node (ref "R17") (pin "2") (pinfunction "2_2") (pintype "bidirectional"))
    )
    (net (code "157") (name "SWE") (class "Default")
      (node (ref "IC2") (pin "W13") (pinfunction "SWE_W13") (pintype "bidirectional"))
      (node (ref "IC4") (pin "L3") (pinfunction "~{WE}_L3") (pintype "bidirectional"))
    )
    (net (code "158") (name "UART0_RX") (class "Default")
      (node (ref "IC2") (pin "H6") (pinfunction "PA5/UART0_RX/PWM0/PA_EINT5_H6") (pintype "bidirectional"))
      (node (ref "R51") (pin "1") (pinfunction "1_1") (pintype "bidirectional"))
    )
    (net (code "159") (name "UART0_TX") (class "Default")
      (node (ref "IC2") (pin "F5") (pinfunction "PA4/UART0_TX/PA_EINT4_F5") (pintype "bidirectional"))
      (node (ref "R49") (pin "1") (pinfunction "1_1") (pintype "bidirectional"))
    )
    (net (code "160") (name "USB0_DRVVBUS") (class "Default")
      (node (ref "IC2") (pin "B16") (pinfunction "PC2/NAND_CLE/SPI0_CLK_B16") (pintype "bidirectional"))
      (node (ref "IC3") (pin "4") (pinfunction "EN_4") (pintype "bidirectional"))
      (node (ref "R15") (pin "2") (pinfunction "2_2") (pintype "bidirectional"))
    )
    (net (code "161") (name "USB0_N") (class "Default")
      (node (ref "IC2") (pin "B5") (pinfunction "USB_DM0_B5") (pintype "bidirectional"))
      (node (ref "X1") (pin "D-") (pinfunction "D-_D-") (pintype "input"))
      (node (ref "Z3") (pin "2") (pinfunction "2_2") (pintype "passive"))
    )
    (net (code "162") (name "USB0_OTGID") (class "Default")
      (node (ref "IC2") (pin "D1") (pinfunction "PG12/PCM1_DOUT/PG_EINT12_D1") (pintype "bidirectional"))
      (node (ref "R6") (pin "1") (pinfunction "1_1") (pintype "bidirectional"))
      (node (ref "X1") (pin "ID") (pinfunction "ID_ID") (pintype "input"))
      (node (ref "Z1") (pin "2") (pinfunction "2_2") (pintype "passive"))
    )
    (net (code "163") (name "USB0_P") (class "Default")
      (node (ref "IC2") (pin "A5") (pinfunction "USB_DP0_A5") (pintype "bidirectional"))
      (node (ref "X1") (pin "D+") (pinfunction "D+_D+") (pintype "input"))
      (node (ref "Z2") (pin "2") (pinfunction "2_2") (pintype "passive"))
    )
    (net (code "164") (name "VDDI_EMMC") (class "Default")
      (node (ref "C3") (pin "2") (pinfunction "P$2_2") (pintype "bidirectional"))
      (node (ref "C7") (pin "2") (pinfunction "P$2_2") (pintype "bidirectional"))
      (node (ref "IC1") (pin "C2") (pinfunction "VDDI_C2") (pintype "bidirectional"))
    )
    (net (code "165") (name "VDD_CPUFB") (class "Default")
      (node (ref "C103") (pin "1") (pinfunction "P$1_1") (pintype "bidirectional"))
      (node (ref "IC2") (pin "T10") (pinfunction "VDD_CPUXFB_T10") (pintype "bidirectional"))
      (node (ref "R47") (pin "2") (pinfunction "2_2") (pintype "bidirectional"))
    )
    (net (code "166") (name "VDD_CPUS") (class "Default")
      (node (ref "C2") (pin "1") (pinfunction "P$1_1") (pintype "bidirectional"))
      (node (ref "C4") (pin "1") (pinfunction "P$1_1") (pintype "bidirectional"))
      (node (ref "C53") (pin "1") (pinfunction "P$1_1") (pintype "bidirectional"))
      (node (ref "IC2") (pin "J7") (pinfunction "VDD_CPUS0_J7") (pintype "bidirectional"))
      (node (ref "IC2") (pin "J8") (pinfunction "VDD_CPUS1_J8") (pintype "bidirectional"))
      (node (ref "IC2") (pin "M4") (pinfunction "RTC_VIO_M4") (pintype "bidirectional"))
    )
    (net (code "167") (name "VDD_CPUX") (class "Default")
      (node (ref "C105") (pin "1") (pinfunction "P$1_1") (pintype "bidirectional"))
      (node (ref "C106") (pin "1") (pinfunction "P$1_1") (pintype "bidirectional"))
      (node (ref "C107") (pin "1") (pinfunction "P$1_1") (pintype "bidirectional"))
      (node (ref "C17") (pin "1") (pinfunction "P$1_1") (pintype "bidirectional"))
      (node (ref "C18") (pin "1") (pinfunction "P$1_1") (pintype "bidirectional"))
      (node (ref "C21") (pin "1") (pinfunction "P$1_1") (pintype "bidirectional"))
      (node (ref "C24") (pin "1") (pinfunction "P$1_1") (pintype "bidirectional"))
      (node (ref "C28") (pin "1") (pinfunction "P$1_1") (pintype "bidirectional"))
      (node (ref "C31") (pin "1") (pinfunction "P$1_1") (pintype "bidirectional"))
      (node (ref "IC10") (pin "5") (pinfunction "OUT_5") (pintype "bidirectional"))
      (node (ref "IC2") (pin "N8") (pinfunction "VDD_CPUX0_N8") (pintype "bidirectional"))
      (node (ref "IC2") (pin "P6") (pinfunction "VDD_CPUX1_P6") (pintype "bidirectional"))
      (node (ref "IC2") (pin "P7") (pinfunction "VDD_CPUX2_P7") (pintype "bidirectional"))
      (node (ref "IC2") (pin "P8") (pinfunction "VDD_CPUX3_P8") (pintype "bidirectional"))
      (node (ref "IC2") (pin "P9") (pinfunction "VDD_CPUX4_P9") (pintype "bidirectional"))
      (node (ref "IC2") (pin "R6") (pinfunction "VDD_CPUX5_R6") (pintype "bidirectional"))
      (node (ref "IC2") (pin "R7") (pinfunction "VDD_CPUX6_R7") (pintype "bidirectional"))
      (node (ref "IC2") (pin "R8") (pinfunction "VDD_CPUX7_R8") (pintype "bidirectional"))
      (node (ref "IC2") (pin "T6") (pinfunction "VDD_CPUX8_T6") (pintype "bidirectional"))
      (node (ref "IC2") (pin "T7") (pinfunction "VDD_CPUX9_T7") (pintype "bidirectional"))
      (node (ref "IC2") (pin "T8") (pinfunction "VDD_CPUX10_T8") (pintype "bidirectional"))
      (node (ref "IC2") (pin "U6") (pinfunction "VDD_CPUX11_U6") (pintype "bidirectional"))
      (node (ref "IC2") (pin "U9") (pinfunction "VDD_CPUX12_U9") (pintype "bidirectional"))
      (node (ref "L7") (pin "2") (pinfunction "2_2") (pintype "bidirectional"))
    )
    (net (code "168") (name "VIN") (class "Default")
      (node (ref "C32") (pin "1") (pinfunction "P$1_1") (pintype "bidirectional"))
      (node (ref "C40") (pin "1") (pinfunction "P$1_1") (pintype "bidirectional"))
      (node (ref "C41") (pin "1") (pinfunction "P$1_1") (pintype "bidirectional"))
      (node (ref "C42") (pin "1") (pinfunction "P$1_1") (pintype "bidirectional"))
      (node (ref "C43") (pin "1") (pinfunction "P$1_1") (pintype "bidirectional"))
      (node (ref "C44") (pin "1") (pinfunction "P$1_1") (pintype "bidirectional"))
      (node (ref "C45") (pin "1") (pinfunction "P$1_1") (pintype "bidirectional"))
      (node (ref "C46") (pin "1") (pinfunction "P$1_1") (pintype "bidirectional"))
      (node (ref "C47") (pin "1") (pinfunction "P$1_1") (pintype "bidirectional"))
      (node (ref "C48") (pin "1") (pinfunction "P$1_1") (pintype "bidirectional"))
      (node (ref "C93") (pin "1") (pinfunction "P$1_1") (pintype "bidirectional"))
      (node (ref "C94") (pin "1") (pinfunction "P$1_1") (pintype "bidirectional"))
      (node (ref "C95") (pin "1") (pinfunction "P$1_1") (pintype "bidirectional"))
      (node (ref "C96") (pin "1") (pinfunction "P$1_1") (pintype "bidirectional"))
      (node (ref "C97") (pin "1") (pinfunction "P$1_1") (pintype "bidirectional"))
      (node (ref "C98") (pin "1") (pinfunction "P$1_1") (pintype "bidirectional"))
      (node (ref "C99") (pin "1") (pinfunction "P$1_1") (pintype "bidirectional"))
      (node (ref "IC10") (pin "2") (pinfunction "VIN_2") (pintype "bidirectional"))
      (node (ref "IC3") (pin "5") (pinfunction "IN_5") (pintype "bidirectional"))
      (node (ref "IC5") (pin "4") (pinfunction "VIN_4") (pintype "bidirectional"))
      (node (ref "IC6") (pin "4") (pinfunction "VIN_4") (pintype "bidirectional"))
      (node (ref "IC7") (pin "4") (pinfunction "IN_4") (pintype "bidirectional"))
      (node (ref "IC9") (pin "1") (pinfunction "EN_1") (pintype "bidirectional"))
      (node (ref "IC9") (pin "4") (pinfunction "VIN_4") (pintype "bidirectional"))
      (node (ref "JP3") (pin "18") (pinfunction "18_18") (pintype "passive"))
      (node (ref "LED4") (pin "1") (pinfunction "VDD_1") (pintype "bidirectional"))
      (node (ref "Q1") (pin "2") (pinfunction "S_2") (pintype "bidirectional"))
      (node (ref "Q2") (pin "4") (pinfunction "EMITTER_TR2_4") (pintype "bidirectional"))
    )
    (net (code "169") (name "WIFI_32K") (class "Default")
      (node (ref "IC2") (pin "P3") (pinfunction "X32KFOUT_P3") (pintype "bidirectional"))
      (node (ref "R31") (pin "2") (pinfunction "2_2") (pintype "bidirectional"))
      (node (ref "U1") (pin "24") (pinfunction "LPO_24") (pintype "bidirectional"))
    )
    (net (code "170") (name "WL_REG_ON") (class "Default")
      (node (ref "IC2") (pin "T3") (pinfunction "PL7/S_JTAG_SI/S_PL_EINT7_T3") (pintype "bidirectional"))
      (node (ref "R11") (pin "2") (pinfunction "2_2") (pintype "bidirectional"))
      (node (ref "U1") (pin "12") (pinfunction "WL_REG_ON_12") (pintype "bidirectional"))
    )
    (net (code "171") (name "WL_WAKE_HOST") (class "Default")
      (node (ref "IC2") (pin "M3") (pinfunction "PG10/PCM1_SYNC/PG_EINT10_M3") (pintype "bidirectional"))
      (node (ref "R8") (pin "2") (pinfunction "2_2") (pintype "bidirectional"))
      (node (ref "U1") (pin "13") (pinfunction "WL_HOST_WAKE_13") (pintype "bidirectional"))
    )
    (net (code "172") (name "X24_IN") (class "Default")
      (node (ref "C87") (pin "2") (pinfunction "P$2_2") (pintype "bidirectional"))
      (node (ref "IC2") (pin "K2") (pinfunction "X24MIN_K2") (pintype "bidirectional"))
      (node (ref "Y2") (pin "3") (pinfunction "2_3") (pintype "passive"))
    )
    (net (code "173") (name "X24_OUT") (class "Default")
      (node (ref "C88") (pin "2") (pinfunction "P$2_2") (pintype "bidirectional"))
      (node (ref "IC2") (pin "K1") (pinfunction "X24MOUT_K1") (pintype "bidirectional"))
      (node (ref "Y2") (pin "1") (pinfunction "1_1") (pintype "passive"))
    )
    (net (code "174") (name "unconnected-(ANT1-NC-Pad2)") (class "Default")
      (node (ref "ANT1") (pin "2") (pinfunction "NC_2") (pintype "no_connect"))
    )
    (net (code "175") (name "unconnected-(IC1-DATA_STROBE-PadH5)") (class "Default")
      (node (ref "IC1") (pin "H5") (pinfunction "DATA_STROBE_H5") (pintype "bidirectional"))
    )
    (net (code "176") (name "unconnected-(IC1-NC_1-PadA1)") (class "Default")
      (node (ref "IC1") (pin "A1") (pinfunction "NC_1_A1") (pintype "bidirectional"))
    )
    (net (code "177") (name "unconnected-(IC1-NC_2-PadA2)") (class "Default")
      (node (ref "IC1") (pin "A2") (pinfunction "NC_2_A2") (pintype "bidirectional"))
    )
    (net (code "178") (name "unconnected-(IC1-NC_3-PadA7)") (class "Default")
      (node (ref "IC1") (pin "A7") (pinfunction "NC_3_A7") (pintype "bidirectional"))
    )
    (net (code "179") (name "unconnected-(IC1-NC_4-PadA8)") (class "Default")
      (node (ref "IC1") (pin "A8") (pinfunction "NC_4_A8") (pintype "bidirectional"))
    )
    (net (code "180") (name "unconnected-(IC1-NC_5-PadA9)") (class "Default")
      (node (ref "IC1") (pin "A9") (pinfunction "NC_5_A9") (pintype "bidirectional"))
    )
    (net (code "181") (name "unconnected-(IC1-NC_6-PadA10)") (class "Default")
      (node (ref "IC1") (pin "A10") (pinfunction "NC_6_A10") (pintype "bidirectional"))
    )
    (net (code "182") (name "unconnected-(IC1-NC_7-PadA11)") (class "Default")
      (node (ref "IC1") (pin "A11") (pinfunction "NC_7_A11") (pintype "bidirectional"))
    )
    (net (code "183") (name "unconnected-(IC1-NC_8-PadA12)") (class "Default")
      (node (ref "IC1") (pin "A12") (pinfunction "NC_8_A12") (pintype "bidirectional"))
    )
    (net (code "184") (name "unconnected-(IC1-NC_9-PadA13)") (class "Default")
      (node (ref "IC1") (pin "A13") (pinfunction "NC_9_A13") (pintype "bidirectional"))
    )
    (net (code "185") (name "unconnected-(IC1-NC_10-PadA14)") (class "Default")
      (node (ref "IC1") (pin "A14") (pinfunction "NC_10_A14") (pintype "bidirectional"))
    )
    (net (code "186") (name "unconnected-(IC1-NC_11-PadB1)") (class "Default")
      (node (ref "IC1") (pin "B1") (pinfunction "NC_11_B1") (pintype "bidirectional"))
    )
    (net (code "187") (name "unconnected-(IC1-NC_12-PadB7)") (class "Default")
      (node (ref "IC1") (pin "B7") (pinfunction "NC_12_B7") (pintype "bidirectional"))
    )
    (net (code "188") (name "unconnected-(IC1-NC_13-PadB8)") (class "Default")
      (node (ref "IC1") (pin "B8") (pinfunction "NC_13_B8") (pintype "bidirectional"))
    )
    (net (code "189") (name "unconnected-(IC1-NC_14-PadB9)") (class "Default")
      (node (ref "IC1") (pin "B9") (pinfunction "NC_14_B9") (pintype "bidirectional"))
    )
    (net (code "190") (name "unconnected-(IC1-NC_15-PadB10)") (class "Default")
      (node (ref "IC1") (pin "B10") (pinfunction "NC_15_B10") (pintype "bidirectional"))
    )
    (net (code "191") (name "unconnected-(IC1-NC_16-PadB11)") (class "Default")
      (node (ref "IC1") (pin "B11") (pinfunction "NC_16_B11") (pintype "bidirectional"))
    )
    (net (code "192") (name "unconnected-(IC1-NC_17-PadB12)") (class "Default")
      (node (ref "IC1") (pin "B12") (pinfunction "NC_17_B12") (pintype "bidirectional"))
    )
    (net (code "193") (name "unconnected-(IC1-NC_18-PadB13)") (class "Default")
      (node (ref "IC1") (pin "B13") (pinfunction "NC_18_B13") (pintype "bidirectional"))
    )
    (net (code "194") (name "unconnected-(IC1-NC_19-PadB14)") (class "Default")
      (node (ref "IC1") (pin "B14") (pinfunction "NC_19_B14") (pintype "bidirectional"))
    )
    (net (code "195") (name "unconnected-(IC1-NC_20-PadC1)") (class "Default")
      (node (ref "IC1") (pin "C1") (pinfunction "NC_20_C1") (pintype "bidirectional"))
    )
    (net (code "196") (name "unconnected-(IC1-NC_21-PadC3)") (class "Default")
      (node (ref "IC1") (pin "C3") (pinfunction "NC_21_C3") (pintype "bidirectional"))
    )
    (net (code "197") (name "unconnected-(IC1-NC_22-PadC5)") (class "Default")
      (node (ref "IC1") (pin "C5") (pinfunction "NC_22_C5") (pintype "bidirectional"))
    )
    (net (code "198") (name "unconnected-(IC1-NC_23-PadC7)") (class "Default")
      (node (ref "IC1") (pin "C7") (pinfunction "NC_23_C7") (pintype "bidirectional"))
    )
    (net (code "199") (name "unconnected-(IC1-NC_24-PadC8)") (class "Default")
      (node (ref "IC1") (pin "C8") (pinfunction "NC_24_C8") (pintype "bidirectional"))
    )
    (net (code "200") (name "unconnected-(IC1-NC_25-PadC9)") (class "Default")
      (node (ref "IC1") (pin "C9") (pinfunction "NC_25_C9") (pintype "bidirectional"))
    )
    (net (code "201") (name "unconnected-(IC1-NC_26-PadC10)") (class "Default")
      (node (ref "IC1") (pin "C10") (pinfunction "NC_26_C10") (pintype "bidirectional"))
    )
    (net (code "202") (name "unconnected-(IC1-NC_27-PadC11)") (class "Default")
      (node (ref "IC1") (pin "C11") (pinfunction "NC_27_C11") (pintype "bidirectional"))
    )
    (net (code "203") (name "unconnected-(IC1-NC_28-PadC12)") (class "Default")
      (node (ref "IC1") (pin "C12") (pinfunction "NC_28_C12") (pintype "bidirectional"))
    )
    (net (code "204") (name "unconnected-(IC1-NC_29-PadC13)") (class "Default")
      (node (ref "IC1") (pin "C13") (pinfunction "NC_29_C13") (pintype "bidirectional"))
    )
    (net (code "205") (name "unconnected-(IC1-NC_30-PadC14)") (class "Default")
      (node (ref "IC1") (pin "C14") (pinfunction "NC_30_C14") (pintype "bidirectional"))
    )
    (net (code "206") (name "unconnected-(IC1-NC_31-PadD1)") (class "Default")
      (node (ref "IC1") (pin "D1") (pinfunction "NC_31_D1") (pintype "bidirectional"))
    )
    (net (code "207") (name "unconnected-(IC1-NC_32-PadD2)") (class "Default")
      (node (ref "IC1") (pin "D2") (pinfunction "NC_32_D2") (pintype "bidirectional"))
    )
    (net (code "208") (name "unconnected-(IC1-NC_33-PadD3)") (class "Default")
      (node (ref "IC1") (pin "D3") (pinfunction "NC_33_D3") (pintype "bidirectional"))
    )
    (net (code "209") (name "unconnected-(IC1-NC_34-PadD4)") (class "Default")
      (node (ref "IC1") (pin "D4") (pinfunction "NC_34_D4") (pintype "bidirectional"))
    )
    (net (code "210") (name "unconnected-(IC1-NC_35-PadD12)") (class "Default")
      (node (ref "IC1") (pin "D12") (pinfunction "NC_35_D12") (pintype "bidirectional"))
    )
    (net (code "211") (name "unconnected-(IC1-NC_36-PadD13)") (class "Default")
      (node (ref "IC1") (pin "D13") (pinfunction "NC_36_D13") (pintype "bidirectional"))
    )
    (net (code "212") (name "unconnected-(IC1-NC_37-PadD14)") (class "Default")
      (node (ref "IC1") (pin "D14") (pinfunction "NC_37_D14") (pintype "bidirectional"))
    )
    (net (code "213") (name "unconnected-(IC1-NC_38-PadE1)") (class "Default")
      (node (ref "IC1") (pin "E1") (pinfunction "NC_38_E1") (pintype "bidirectional"))
    )
    (net (code "214") (name "unconnected-(IC1-NC_39-PadE2)") (class "Default")
      (node (ref "IC1") (pin "E2") (pinfunction "NC_39_E2") (pintype "bidirectional"))
    )
    (net (code "215") (name "unconnected-(IC1-NC_40-PadE3)") (class "Default")
      (node (ref "IC1") (pin "E3") (pinfunction "NC_40_E3") (pintype "bidirectional"))
    )
    (net (code "216") (name "unconnected-(IC1-NC_41-PadE5)") (class "Default")
      (node (ref "IC1") (pin "E5") (pinfunction "NC_41_E5") (pintype "bidirectional"))
    )
    (net (code "217") (name "unconnected-(IC1-NC_42-PadE8)") (class "Default")
      (node (ref "IC1") (pin "E8") (pinfunction "NC_42_E8") (pintype "bidirectional"))
    )
    (net (code "218") (name "unconnected-(IC1-NC_43-PadE9)") (class "Default")
      (node (ref "IC1") (pin "E9") (pinfunction "NC_43_E9") (pintype "bidirectional"))
    )
    (net (code "219") (name "unconnected-(IC1-NC_44-PadE10)") (class "Default")
      (node (ref "IC1") (pin "E10") (pinfunction "NC_44_E10") (pintype "bidirectional"))
    )
    (net (code "220") (name "unconnected-(IC1-NC_45-PadE12)") (class "Default")
      (node (ref "IC1") (pin "E12") (pinfunction "NC_45_E12") (pintype "bidirectional"))
    )
    (net (code "221") (name "unconnected-(IC1-NC_46-PadE13)") (class "Default")
      (node (ref "IC1") (pin "E13") (pinfunction "NC_46_E13") (pintype "bidirectional"))
    )
    (net (code "222") (name "unconnected-(IC1-NC_47-PadE14)") (class "Default")
      (node (ref "IC1") (pin "E14") (pinfunction "NC_47_E14") (pintype "bidirectional"))
    )
    (net (code "223") (name "unconnected-(IC1-NC_48-PadF1)") (class "Default")
      (node (ref "IC1") (pin "F1") (pinfunction "NC_48_F1") (pintype "bidirectional"))
    )
    (net (code "224") (name "unconnected-(IC1-NC_49-PadF2)") (class "Default")
      (node (ref "IC1") (pin "F2") (pinfunction "NC_49_F2") (pintype "bidirectional"))
    )
    (net (code "225") (name "unconnected-(IC1-NC_50-PadF3)") (class "Default")
      (node (ref "IC1") (pin "F3") (pinfunction "NC_50_F3") (pintype "bidirectional"))
    )
    (net (code "226") (name "unconnected-(IC1-NC_51-PadF10)") (class "Default")
      (node (ref "IC1") (pin "F10") (pinfunction "NC_51_F10") (pintype "bidirectional"))
    )
    (net (code "227") (name "unconnected-(IC1-NC_52-PadF12)") (class "Default")
      (node (ref "IC1") (pin "F12") (pinfunction "NC_52_F12") (pintype "bidirectional"))
    )
    (net (code "228") (name "unconnected-(IC1-NC_53-PadF13)") (class "Default")
      (node (ref "IC1") (pin "F13") (pinfunction "NC_53_F13") (pintype "bidirectional"))
    )
    (net (code "229") (name "unconnected-(IC1-NC_54-PadF14)") (class "Default")
      (node (ref "IC1") (pin "F14") (pinfunction "NC_54_F14") (pintype "bidirectional"))
    )
    (net (code "230") (name "unconnected-(IC1-NC_55-PadG1)") (class "Default")
      (node (ref "IC1") (pin "G1") (pinfunction "NC_55_G1") (pintype "bidirectional"))
    )
    (net (code "231") (name "unconnected-(IC1-NC_56-PadG2)") (class "Default")
      (node (ref "IC1") (pin "G2") (pinfunction "NC_56_G2") (pintype "bidirectional"))
    )
    (net (code "232") (name "unconnected-(IC1-NC_57-PadG3)") (class "Default")
      (node (ref "IC1") (pin "G3") (pinfunction "NC_57_G3") (pintype "bidirectional"))
    )
    (net (code "233") (name "unconnected-(IC1-NC_58-PadG10)") (class "Default")
      (node (ref "IC1") (pin "G10") (pinfunction "NC_58_G10") (pintype "bidirectional"))
    )
    (net (code "234") (name "unconnected-(IC1-NC_59-PadG12)") (class "Default")
      (node (ref "IC1") (pin "G12") (pinfunction "NC_59_G12") (pintype "bidirectional"))
    )
    (net (code "235") (name "unconnected-(IC1-NC_60-PadG13)") (class "Default")
      (node (ref "IC1") (pin "G13") (pinfunction "NC_60_G13") (pintype "bidirectional"))
    )
    (net (code "236") (name "unconnected-(IC1-NC_61-PadG14)") (class "Default")
      (node (ref "IC1") (pin "G14") (pinfunction "NC_61_G14") (pintype "bidirectional"))
    )
    (net (code "237") (name "unconnected-(IC1-NC_62-PadH1)") (class "Default")
      (node (ref "IC1") (pin "H1") (pinfunction "NC_62_H1") (pintype "bidirectional"))
    )
    (net (code "238") (name "unconnected-(IC1-NC_63-PadH2)") (class "Default")
      (node (ref "IC1") (pin "H2") (pinfunction "NC_63_H2") (pintype "bidirectional"))
    )
    (net (code "239") (name "unconnected-(IC1-NC_64-PadH3)") (class "Default")
      (node (ref "IC1") (pin "H3") (pinfunction "NC_64_H3") (pintype "bidirectional"))
    )
    (net (code "240") (name "unconnected-(IC1-NC_65-PadH12)") (class "Default")
      (node (ref "IC1") (pin "H12") (pinfunction "NC_65_H12") (pintype "bidirectional"))
    )
    (net (code "241") (name "unconnected-(IC1-NC_66-PadH13)") (class "Default")
      (node (ref "IC1") (pin "H13") (pinfunction "NC_66_H13") (pintype "bidirectional"))
    )
    (net (code "242") (name "unconnected-(IC1-NC_67-PadH14)") (class "Default")
      (node (ref "IC1") (pin "H14") (pinfunction "NC_67_H14") (pintype "bidirectional"))
    )
    (net (code "243") (name "unconnected-(IC1-NC_68-PadJ1)") (class "Default")
      (node (ref "IC1") (pin "J1") (pinfunction "NC_68_J1") (pintype "bidirectional"))
    )
    (net (code "244") (name "unconnected-(IC1-NC_69-PadJ2)") (class "Default")
      (node (ref "IC1") (pin "J2") (pinfunction "NC_69_J2") (pintype "bidirectional"))
    )
    (net (code "245") (name "unconnected-(IC1-NC_70-PadJ3)") (class "Default")
      (node (ref "IC1") (pin "J3") (pinfunction "NC_70_J3") (pintype "bidirectional"))
    )
    (net (code "246") (name "unconnected-(IC1-NC_71-PadJ12)") (class "Default")
      (node (ref "IC1") (pin "J12") (pinfunction "NC_71_J12") (pintype "bidirectional"))
    )
    (net (code "247") (name "unconnected-(IC1-NC_72-PadJ13)") (class "Default")
      (node (ref "IC1") (pin "J13") (pinfunction "NC_72_J13") (pintype "bidirectional"))
    )
    (net (code "248") (name "unconnected-(IC1-NC_73-PadJ14)") (class "Default")
      (node (ref "IC1") (pin "J14") (pinfunction "NC_73_J14") (pintype "bidirectional"))
    )
    (net (code "249") (name "unconnected-(IC1-NC_74-PadK1)") (class "Default")
      (node (ref "IC1") (pin "K1") (pinfunction "NC_74_K1") (pintype "bidirectional"))
    )
    (net (code "250") (name "unconnected-(IC1-NC_75-PadK2)") (class "Default")
      (node (ref "IC1") (pin "K2") (pinfunction "NC_75_K2") (pintype "bidirectional"))
    )
    (net (code "251") (name "unconnected-(IC1-NC_76-PadK3)") (class "Default")
      (node (ref "IC1") (pin "K3") (pinfunction "NC_76_K3") (pintype "bidirectional"))
    )
    (net (code "252") (name "unconnected-(IC1-NC_77-PadK6)") (class "Default")
      (node (ref "IC1") (pin "K6") (pinfunction "NC_77_K6") (pintype "bidirectional"))
    )
    (net (code "253") (name "unconnected-(IC1-NC_78-PadK7)") (class "Default")
      (node (ref "IC1") (pin "K7") (pinfunction "NC_78_K7") (pintype "bidirectional"))
    )
    (net (code "254") (name "unconnected-(IC1-NC_79-PadK10)") (class "Default")
      (node (ref "IC1") (pin "K10") (pinfunction "NC_79_K10") (pintype "bidirectional"))
    )
    (net (code "255") (name "unconnected-(IC1-NC_80-PadK12)") (class "Default")
      (node (ref "IC1") (pin "K12") (pinfunction "NC_80_K12") (pintype "bidirectional"))
    )
    (net (code "256") (name "unconnected-(IC1-NC_81-PadK13)") (class "Default")
      (node (ref "IC1") (pin "K13") (pinfunction "NC_81_K13") (pintype "bidirectional"))
    )
    (net (code "257") (name "unconnected-(IC1-NC_82-PadK14)") (class "Default")
      (node (ref "IC1") (pin "K14") (pinfunction "NC_82_K14") (pintype "bidirectional"))
    )
    (net (code "258") (name "unconnected-(IC1-NC_83-PadL1)") (class "Default")
      (node (ref "IC1") (pin "L1") (pinfunction "NC_83_L1") (pintype "bidirectional"))
    )
    (net (code "259") (name "unconnected-(IC1-NC_84-PadL2)") (class "Default")
      (node (ref "IC1") (pin "L2") (pinfunction "NC_84_L2") (pintype "bidirectional"))
    )
    (net (code "260") (name "unconnected-(IC1-NC_85-PadL3)") (class "Default")
      (node (ref "IC1") (pin "L3") (pinfunction "NC_85_L3") (pintype "bidirectional"))
    )
    (net (code "261") (name "unconnected-(IC1-NC_86-PadL12)") (class "Default")
      (node (ref "IC1") (pin "L12") (pinfunction "NC_86_L12") (pintype "bidirectional"))
    )
    (net (code "262") (name "unconnected-(IC1-NC_87-PadL13)") (class "Default")
      (node (ref "IC1") (pin "L13") (pinfunction "NC_87_L13") (pintype "bidirectional"))
    )
    (net (code "263") (name "unconnected-(IC1-NC_88-PadL14)") (class "Default")
      (node (ref "IC1") (pin "L14") (pinfunction "NC_88_L14") (pintype "bidirectional"))
    )
    (net (code "264") (name "unconnected-(IC1-NC_89-PadM1)") (class "Default")
      (node (ref "IC1") (pin "M1") (pinfunction "NC_89_M1") (pintype "bidirectional"))
    )
    (net (code "265") (name "unconnected-(IC1-NC_90-PadM2)") (class "Default")
      (node (ref "IC1") (pin "M2") (pinfunction "NC_90_M2") (pintype "bidirectional"))
    )
    (net (code "266") (name "unconnected-(IC1-NC_91-PadM3)") (class "Default")
      (node (ref "IC1") (pin "M3") (pinfunction "NC_91_M3") (pintype "bidirectional"))
    )
    (net (code "267") (name "unconnected-(IC1-NC_92-PadM7)") (class "Default")
      (node (ref "IC1") (pin "M7") (pinfunction "NC_92_M7") (pintype "bidirectional"))
    )
    (net (code "268") (name "unconnected-(IC1-NC_93-PadM8)") (class "Default")
      (node (ref "IC1") (pin "M8") (pinfunction "NC_93_M8") (pintype "bidirectional"))
    )
    (net (code "269") (name "unconnected-(IC1-NC_94-PadM9)") (class "Default")
      (node (ref "IC1") (pin "M9") (pinfunction "NC_94_M9") (pintype "bidirectional"))
    )
    (net (code "270") (name "unconnected-(IC1-NC_95-PadM10)") (class "Default")
      (node (ref "IC1") (pin "M10") (pinfunction "NC_95_M10") (pintype "bidirectional"))
    )
    (net (code "271") (name "unconnected-(IC1-NC_96-PadM11)") (class "Default")
      (node (ref "IC1") (pin "M11") (pinfunction "NC_96_M11") (pintype "bidirectional"))
    )
    (net (code "272") (name "unconnected-(IC1-NC_97-PadM12)") (class "Default")
      (node (ref "IC1") (pin "M12") (pinfunction "NC_97_M12") (pintype "bidirectional"))
    )
    (net (code "273") (name "unconnected-(IC1-NC_98-PadM13)") (class "Default")
      (node (ref "IC1") (pin "M13") (pinfunction "NC_98_M13") (pintype "bidirectional"))
    )
    (net (code "274") (name "unconnected-(IC1-NC_99-PadM14)") (class "Default")
      (node (ref "IC1") (pin "M14") (pinfunction "NC_99_M14") (pintype "bidirectional"))
    )
    (net (code "275") (name "unconnected-(IC1-NC_100-PadN1)") (class "Default")
      (node (ref "IC1") (pin "N1") (pinfunction "NC_100_N1") (pintype "bidirectional"))
    )
    (net (code "276") (name "unconnected-(IC1-NC_101-PadN3)") (class "Default")
      (node (ref "IC1") (pin "N3") (pinfunction "NC_101_N3") (pintype "bidirectional"))
    )
    (net (code "277") (name "unconnected-(IC1-NC_102-PadN6)") (class "Default")
      (node (ref "IC1") (pin "N6") (pinfunction "NC_102_N6") (pintype "bidirectional"))
    )
    (net (code "278") (name "unconnected-(IC1-NC_103-PadN7)") (class "Default")
      (node (ref "IC1") (pin "N7") (pinfunction "NC_103_N7") (pintype "bidirectional"))
    )
    (net (code "279") (name "unconnected-(IC1-NC_104-PadN8)") (class "Default")
      (node (ref "IC1") (pin "N8") (pinfunction "NC_104_N8") (pintype "bidirectional"))
    )
    (net (code "280") (name "unconnected-(IC1-NC_105-PadN9)") (class "Default")
      (node (ref "IC1") (pin "N9") (pinfunction "NC_105_N9") (pintype "bidirectional"))
    )
    (net (code "281") (name "unconnected-(IC1-NC_106-PadN10)") (class "Default")
      (node (ref "IC1") (pin "N10") (pinfunction "NC_106_N10") (pintype "bidirectional"))
    )
    (net (code "282") (name "unconnected-(IC1-NC_107-PadN11)") (class "Default")
      (node (ref "IC1") (pin "N11") (pinfunction "NC_107_N11") (pintype "bidirectional"))
    )
    (net (code "283") (name "unconnected-(IC1-NC_108-PadN12)") (class "Default")
      (node (ref "IC1") (pin "N12") (pinfunction "NC_108_N12") (pintype "bidirectional"))
    )
    (net (code "284") (name "unconnected-(IC1-NC_109-PadN13)") (class "Default")
      (node (ref "IC1") (pin "N13") (pinfunction "NC_109_N13") (pintype "bidirectional"))
    )
    (net (code "285") (name "unconnected-(IC1-NC_110-PadN14)") (class "Default")
      (node (ref "IC1") (pin "N14") (pinfunction "NC_110_N14") (pintype "bidirectional"))
    )
    (net (code "286") (name "unconnected-(IC1-NC_111-PadP1)") (class "Default")
      (node (ref "IC1") (pin "P1") (pinfunction "NC_111_P1") (pintype "bidirectional"))
    )
    (net (code "287") (name "unconnected-(IC1-NC_112-PadP2)") (class "Default")
      (node (ref "IC1") (pin "P2") (pinfunction "NC_112_P2") (pintype "bidirectional"))
    )
    (net (code "288") (name "unconnected-(IC1-NC_113-PadP7)") (class "Default")
      (node (ref "IC1") (pin "P7") (pinfunction "NC_113_P7") (pintype "bidirectional"))
    )
    (net (code "289") (name "unconnected-(IC1-NC_114-PadP8)") (class "Default")
      (node (ref "IC1") (pin "P8") (pinfunction "NC_114_P8") (pintype "bidirectional"))
    )
    (net (code "290") (name "unconnected-(IC1-NC_115-PadP9)") (class "Default")
      (node (ref "IC1") (pin "P9") (pinfunction "NC_115_P9") (pintype "bidirectional"))
    )
    (net (code "291") (name "unconnected-(IC1-NC_116-PadP10)") (class "Default")
      (node (ref "IC1") (pin "P10") (pinfunction "NC_116_P10") (pintype "bidirectional"))
    )
    (net (code "292") (name "unconnected-(IC1-NC_117-PadP11)") (class "Default")
      (node (ref "IC1") (pin "P11") (pinfunction "NC_117_P11") (pintype "bidirectional"))
    )
    (net (code "293") (name "unconnected-(IC1-NC_118-PadP12)") (class "Default")
      (node (ref "IC1") (pin "P12") (pinfunction "NC_118_P12") (pintype "bidirectional"))
    )
    (net (code "294") (name "unconnected-(IC1-NC_119-PadP13)") (class "Default")
      (node (ref "IC1") (pin "P13") (pinfunction "NC_119_P13") (pintype "bidirectional"))
    )
    (net (code "295") (name "unconnected-(IC1-NC_120-PadP14)") (class "Default")
      (node (ref "IC1") (pin "P14") (pinfunction "NC_120_P14") (pintype "bidirectional"))
    )
    (net (code "296") (name "unconnected-(IC2A-PA0{slash}UART2_TX{slash}JTAG_MS0{slash}PA_EINT0-PadD11)") (class "Default")
      (node (ref "IC2") (pin "D11") (pinfunction "PA0/UART2_TX/JTAG_MS0/PA_EINT0_D11") (pintype "bidirectional"))
    )
    (net (code "297") (name "unconnected-(IC2A-PA1{slash}UART2_RX{slash}JTAG_CK0{slash}PA_EINT1-PadD5)") (class "Default")
      (node (ref "IC2") (pin "D5") (pinfunction "PA1/UART2_RX/JTAG_CK0/PA_EINT1_D5") (pintype "bidirectional"))
    )
    (net (code "298") (name "unconnected-(IC2A-PA2{slash}UART2_RTS{slash}JTAG_DO0{slash}PA_EINT2-PadD6)") (class "Default")
      (node (ref "IC2") (pin "D6") (pinfunction "PA2/UART2_RTS/JTAG_DO0/PA_EINT2_D6") (pintype "bidirectional"))
    )
    (net (code "299") (name "unconnected-(IC2A-PA3{slash}UART2_CTS{slash}JTAG_DI0{slash}PA_EINT3-PadE13)") (class "Default")
      (node (ref "IC2") (pin "E13") (pinfunction "PA3/UART2_CTS/JTAG_DI0/PA_EINT3_E13") (pintype "bidirectional"))
    )
    (net (code "300") (name "unconnected-(IC2A-PA6{slash}SIM_PWREN{slash}PWM1{slash}PA_EINT6-PadE14)") (class "Default")
      (node (ref "IC2") (pin "E14") (pinfunction "PA6/SIM_PWREN/PWM1/PA_EINT6_E14") (pintype "bidirectional"))
    )
    (net (code "301") (name "unconnected-(IC2A-PA7{slash}SIM_CLK{slash}PA_EINT7-PadD8)") (class "Default")
      (node (ref "IC2") (pin "D8") (pinfunction "PA7/SIM_CLK/PA_EINT7_D8") (pintype "bidirectional"))
    )
    (net (code "302") (name "unconnected-(IC2A-PA9{slash}SIM_RST{slash}PA_EINT9-PadD13)") (class "Default")
      (node (ref "IC2") (pin "D13") (pinfunction "PA9/SIM_RST/PA_EINT9_D13") (pintype "bidirectional"))
    )
    (net (code "303") (name "unconnected-(IC2A-PA10{slash}SIM_DET{slash}PA_EINT10-PadE11)") (class "Default")
      (node (ref "IC2") (pin "E11") (pinfunction "PA10/SIM_DET/PA_EINT10_E11") (pintype "bidirectional"))
    )
    (net (code "304") (name "unconnected-(IC2A-PA11{slash}TWI0_SCK{slash}DI_TX{slash}PA_EINT11-PadF11)") (class "Default")
      (node (ref "IC2") (pin "F11") (pinfunction "PA11/TWI0_SCK/DI_TX/PA_EINT11_F11") (pintype "bidirectional"))
    )
    (net (code "305") (name "unconnected-(IC2A-PA12{slash}TWI0_SDA{slash}DI_RX{slash}PA_EINT12-PadC13)") (class "Default")
      (node (ref "IC2") (pin "C13") (pinfunction "PA12/TWI0_SDA/DI_RX/PA_EINT12_C13") (pintype "bidirectional"))
    )
    (net (code "306") (name "unconnected-(IC2A-PA13{slash}SPI1_CS{slash}UART3_TX{slash}PA_EINT13-PadE15)") (class "Default")
      (node (ref "IC2") (pin "E15") (pinfunction "PA13/SPI1_CS/UART3_TX/PA_EINT13_E15") (pintype "bidirectional"))
    )
    (net (code "307") (name "unconnected-(IC2A-PA14{slash}SPI1_CLK{slash}UART3_RX{slash}PA_EINT14-PadG12)") (class "Default")
      (node (ref "IC2") (pin "G12") (pinfunction "PA14/SPI1_CLK/UART3_RX/PA_EINT14_G12") (pintype "bidirectional"))
    )
    (net (code "308") (name "unconnected-(IC2A-PA16{slash}SPI1_MISO{slash}UART3_CTS{slash}PA_EINT16-PadD15)") (class "Default")
      (node (ref "IC2") (pin "D15") (pinfunction "PA16/SPI1_MISO/UART3_CTS/PA_EINT16_D15") (pintype "bidirectional"))
    )
    (net (code "309") (name "unconnected-(IC2A-PA17{slash}SPDIF_OUT{slash}PA_EINT17-PadC14)") (class "Default")
      (node (ref "IC2") (pin "C14") (pinfunction "PA17/SPDIF_OUT/PA_EINT17_C14") (pintype "bidirectional"))
    )
    (net (code "310") (name "unconnected-(IC2A-PA18{slash}PCM0_SYNC{slash}TWI1_SCK{slash}PA_EINT18-PadB13)") (class "Default")
      (node (ref "IC2") (pin "B13") (pinfunction "PA18/PCM0_SYNC/TWI1_SCK/PA_EINT18_B13") (pintype "bidirectional"))
    )
    (net (code "311") (name "unconnected-(IC2A-PA19{slash}PCM0_CLK{slash}TWI1_SDA{slash}PA_EINT19-PadB14)") (class "Default")
      (node (ref "IC2") (pin "B14") (pinfunction "PA19/PCM0_CLK/TWI1_SDA/PA_EINT19_B14") (pintype "bidirectional"))
    )
    (net (code "312") (name "unconnected-(IC2A-PD0{slash}RGMII_RXD3{slash}MII_RXD3{slash}RMII_NULL{slash}DI_TX-PadC21)") (class "Default")
      (node (ref "IC2") (pin "C21") (pinfunction "PD0/RGMII_RXD3/MII_RXD3/RMII_NULL/DI_TX_C21") (pintype "bidirectional"))
    )
    (net (code "313") (name "unconnected-(IC2A-PD2{slash}RGMII_RXD1{slash}MII_RXD1{slash}RMII_RXD1-PadB20)") (class "Default")
      (node (ref "IC2") (pin "B20") (pinfunction "PD2/RGMII_RXD1/MII_RXD1/RMII_RXD1_B20") (pintype "bidirectional"))
    )
    (net (code "314") (name "unconnected-(IC2A-PD3{slash}RGMII_RXD0{slash}MII_RXD0{slash}RMII_RXD0-PadH18)") (class "Default")
      (node (ref "IC2") (pin "H18") (pinfunction "PD3/RGMII_RXD0/MII_RXD0/RMII_RXD0_H18") (pintype "bidirectional"))
    )
    (net (code "315") (name "unconnected-(IC2A-PD5{slash}RGMII_RXCTL{slash}MII_RXDV{slash}RMII_CRS_D-PadF19)") (class "Default")
      (node (ref "IC2") (pin "F19") (pinfunction "PD5/RGMII_RXCTL/MII_RXDV/RMII_CRS_D_F19") (pintype "bidirectional"))
    )
    (net (code "316") (name "unconnected-(IC2A-PD7{slash}RGMII_TXD3{slash}MII_TXD3{slash}RMII_NULL-PadE18)") (class "Default")
      (node (ref "IC2") (pin "E18") (pinfunction "PD7/RGMII_TXD3/MII_TXD3/RMII_NULL_E18") (pintype "bidirectional"))
    )
    (net (code "317") (name "unconnected-(IC2A-PD8{slash}RGMII_TXD2{slash}MII_TXD2{slash}RMII_NULL-PadE20)") (class "Default")
      (node (ref "IC2") (pin "E20") (pinfunction "PD8/RGMII_TXD2/MII_TXD2/RMII_NULL_E20") (pintype "bidirectional"))
    )
    (net (code "318") (name "unconnected-(IC2A-PD9{slash}RGMII_TXD1{slash}MII_TXD1{slash}RMII_TXD1-PadF21)") (class "Default")
      (node (ref "IC2") (pin "F21") (pinfunction "PD9/RGMII_TXD1/MII_TXD1/RMII_TXD1_F21") (pintype "bidirectional"))
    )
    (net (code "319") (name "unconnected-(IC2A-PD10{slash}RGMII_TXD0{slash}MII_TXD0{slash}RMII_TXD0-PadH19)") (class "Default")
      (node (ref "IC2") (pin "H19") (pinfunction "PD10/RGMII_TXD0/MII_TXD0/RMII_TXD0_H19") (pintype "bidirectional"))
    )
    (net (code "320") (name "unconnected-(IC2A-PD11{slash}RGMII_NULL{slash}MII_CRS{slash}RMII_NULL-PadF20)") (class "Default")
      (node (ref "IC2") (pin "F20") (pinfunction "PD11/RGMII_NULL/MII_CRS/RMII_NULL_F20") (pintype "bidirectional"))
    )
    (net (code "321") (name "unconnected-(IC2A-PD12{slash}RGMII_TXCK{slash}MII_TXCK{slash}RMII_TXCK-PadE19)") (class "Default")
      (node (ref "IC2") (pin "E19") (pinfunction "PD12/RGMII_TXCK/MII_TXCK/RMII_TXCK_E19") (pintype "bidirectional"))
    )
    (net (code "322") (name "unconnected-(IC2A-PD13{slash}RGMII_TXCTL{slash}MII_TXEN{slash}RMII_TXEN-PadK17)") (class "Default")
      (node (ref "IC2") (pin "K17") (pinfunction "PD13/RGMII_TXCTL/MII_TXEN/RMII_TXEN_K17") (pintype "bidirectional"))
    )
    (net (code "323") (name "unconnected-(IC2A-PD14{slash}RGMII_NULL{slash}MII_TXERR{slash}RMII_NULL-PadL17)") (class "Default")
      (node (ref "IC2") (pin "L17") (pinfunction "PD14/RGMII_NULL/MII_TXERR/RMII_NULL_L17") (pintype "bidirectional"))
    )
    (net (code "324") (name "unconnected-(IC2A-PD15{slash}RGMII_CLKIN{slash}MII_COL{slash}RMII_NULL-PadK18)") (class "Default")
      (node (ref "IC2") (pin "K18") (pinfunction "PD15/RGMII_CLKIN/MII_COL/RMII_NULL_K18") (pintype "bidirectional"))
    )
    (net (code "325") (name "unconnected-(IC2A-PD16{slash}MDC-PadL18)") (class "Default")
      (node (ref "IC2") (pin "L18") (pinfunction "PD16/MDC_L18") (pintype "bidirectional"))
    )
    (net (code "326") (name "unconnected-(IC2A-PD17{slash}MDIO-PadL19)") (class "Default")
      (node (ref "IC2") (pin "L19") (pinfunction "PD17/MDIO_L19") (pintype "bidirectional"))
    )
    (net (code "327") (name "unconnected-(IC2A-PE0{slash}CSI_PCLK{slash}TS_CLK-PadB10)") (class "Default")
      (node (ref "IC2") (pin "B10") (pinfunction "PE0/CSI_PCLK/TS_CLK_B10") (pintype "bidirectional"))
    )
    (net (code "328") (name "unconnected-(IC2A-PE1{slash}CSI_MCLK{slash}TS_ERR-PadA10)") (class "Default")
      (node (ref "IC2") (pin "A10") (pinfunction "PE1/CSI_MCLK/TS_ERR_A10") (pintype "bidirectional"))
    )
    (net (code "329") (name "unconnected-(IC2A-PE2{slash}CSI_HSYNC{slash}TS_SYNC-PadB11)") (class "Default")
      (node (ref "IC2") (pin "B11") (pinfunction "PE2/CSI_HSYNC/TS_SYNC_B11") (pintype "bidirectional"))
    )
    (net (code "330") (name "unconnected-(IC2A-PE3{slash}CSI_VSYNC{slash}TS_DVLD-PadC10)") (class "Default")
      (node (ref "IC2") (pin "C10") (pinfunction "PE3/CSI_VSYNC/TS_DVLD_C10") (pintype "bidirectional"))
    )
    (net (code "331") (name "unconnected-(IC2A-PE4{slash}CSI_D0{slash}TS_D0-PadC9)") (class "Default")
      (node (ref "IC2") (pin "C9") (pinfunction "PE4/CSI_D0/TS_D0_C9") (pintype "bidirectional"))
    )
    (net (code "332") (name "unconnected-(IC2A-PE5{slash}CSI_D1{slash}TS_D1-PadE10)") (class "Default")
      (node (ref "IC2") (pin "E10") (pinfunction "PE5/CSI_D1/TS_D1_E10") (pintype "bidirectional"))
    )
    (net (code "333") (name "unconnected-(IC2A-PE6{slash}CSI_D2{slash}TS_D2-PadD10)") (class "Default")
      (node (ref "IC2") (pin "D10") (pinfunction "PE6/CSI_D2/TS_D2_D10") (pintype "bidirectional"))
    )
    (net (code "334") (name "unconnected-(IC2A-PE7{slash}CSI_D3{slash}TS_D3-PadC8)") (class "Default")
      (node (ref "IC2") (pin "C8") (pinfunction "PE7/CSI_D3/TS_D3_C8") (pintype "bidirectional"))
    )
    (net (code "335") (name "unconnected-(IC2A-PE8{slash}CSI_D4{slash}TS_D4-PadC11)") (class "Default")
      (node (ref "IC2") (pin "C11") (pinfunction "PE8/CSI_D4/TS_D4_C11") (pintype "bidirectional"))
    )
    (net (code "336") (name "unconnected-(IC2A-PE9{slash}CSI_D5{slash}TS_D5-PadC12)") (class "Default")
      (node (ref "IC2") (pin "C12") (pinfunction "PE9/CSI_D5/TS_D5_C12") (pintype "bidirectional"))
    )
    (net (code "337") (name "unconnected-(IC2A-PE10{slash}CSI_D6{slash}TS_D6-PadE8)") (class "Default")
      (node (ref "IC2") (pin "E8") (pinfunction "PE10/CSI_D6/TS_D6_E8") (pintype "bidirectional"))
    )
    (net (code "338") (name "unconnected-(IC2A-PE11{slash}CSI_D7{slash}TS_D7-PadA11)") (class "Default")
      (node (ref "IC2") (pin "A11") (pinfunction "PE11/CSI_D7/TS_D7_A11") (pintype "bidirectional"))
    )
    (net (code "339") (name "unconnected-(IC2A-PE12{slash}CSI_SCK{slash}TWI2_SCK-PadB12)") (class "Default")
      (node (ref "IC2") (pin "B12") (pinfunction "PE12/CSI_SCK/TWI2_SCK_B12") (pintype "bidirectional"))
    )
    (net (code "340") (name "unconnected-(IC2A-PE13{slash}CSI_SDA{slash}TWI2_SDA-PadC7)") (class "Default")
      (node (ref "IC2") (pin "C7") (pinfunction "PE13/CSI_SDA/TWI2_SDA_C7") (pintype "bidirectional"))
    )
    (net (code "341") (name "unconnected-(IC2A-PE14-PadC6)") (class "Default")
      (node (ref "IC2") (pin "C6") (pinfunction "PE14_C6") (pintype "bidirectional"))
    )
    (net (code "342") (name "unconnected-(IC2A-PE15-PadC5)") (class "Default")
      (node (ref "IC2") (pin "C5") (pinfunction "PE15_C5") (pintype "bidirectional"))
    )
    (net (code "343") (name "unconnected-(IC2A-PF0{slash}SDC0_D1{slash}JTAG_MS0-PadD19)") (class "Default")
      (node (ref "IC2") (pin "D19") (pinfunction "PF0/SDC0_D1/JTAG_MS0_D19") (pintype "bidirectional"))
    )
    (net (code "344") (name "unconnected-(IC2A-PF1{slash}SDC0_D0{slash}JTAG_DI0-PadA19)") (class "Default")
      (node (ref "IC2") (pin "A19") (pinfunction "PF1/SDC0_D0/JTAG_DI0_A19") (pintype "bidirectional"))
    )
    (net (code "345") (name "unconnected-(IC2A-PF2{slash}SDC0_CLK{slash}UART0_TX-PadD20)") (class "Default")
      (node (ref "IC2") (pin "D20") (pinfunction "PF2/SDC0_CLK/UART0_TX_D20") (pintype "bidirectional"))
    )
    (net (code "346") (name "unconnected-(IC2A-PF3{slash}SDC0_CMD{slash}JTAG_DO0-PadF18)") (class "Default")
      (node (ref "IC2") (pin "F18") (pinfunction "PF3/SDC0_CMD/JTAG_DO0_F18") (pintype "bidirectional"))
    )
    (net (code "347") (name "unconnected-(IC2A-PF4{slash}SDC0_D3{slash}UART0_RX-PadE21)") (class "Default")
      (node (ref "IC2") (pin "E21") (pinfunction "PF4/SDC0_D3/UART0_RX_E21") (pintype "bidirectional"))
    )
    (net (code "348") (name "unconnected-(IC2A-PF5{slash}SDC0_D2{slash}JTAG_CK0-PadC20)") (class "Default")
      (node (ref "IC2") (pin "C20") (pinfunction "PF5/SDC0_D2/JTAG_CK0_C20") (pintype "bidirectional"))
    )
    (net (code "349") (name "unconnected-(IC2A-PF6-PadG18)") (class "Default")
      (node (ref "IC2") (pin "G18") (pinfunction "PF6_G18") (pintype "bidirectional"))
    )
    (net (code "350") (name "unconnected-(IC2B-EPHY_LINK_LED-PadA2)") (class "Default")
      (node (ref "IC2") (pin "A2") (pinfunction "EPHY_LINK_LED_A2") (pintype "bidirectional"))
    )
    (net (code "351") (name "unconnected-(IC2B-EPHY_RTX-PadF6)") (class "Default")
      (node (ref "IC2") (pin "F6") (pinfunction "EPHY_RTX_F6") (pintype "bidirectional"))
    )
    (net (code "352") (name "unconnected-(IC2B-EPHY_RXN-PadA4)") (class "Default")
      (node (ref "IC2") (pin "A4") (pinfunction "EPHY_RXN_A4") (pintype "bidirectional"))
    )
    (net (code "353") (name "unconnected-(IC2B-EPHY_RXP-PadB4)") (class "Default")
      (node (ref "IC2") (pin "B4") (pinfunction "EPHY_RXP_B4") (pintype "bidirectional"))
    )
    (net (code "354") (name "unconnected-(IC2B-EPHY_SPD_LED-PadF7)") (class "Default")
      (node (ref "IC2") (pin "F7") (pinfunction "EPHY_SPD_LED_F7") (pintype "bidirectional"))
    )
    (net (code "355") (name "unconnected-(IC2B-EPHY_TXN-PadA3)") (class "Default")
      (node (ref "IC2") (pin "A3") (pinfunction "EPHY_TXN_A3") (pintype "bidirectional"))
    )
    (net (code "356") (name "unconnected-(IC2B-EPHY_TXP-PadB3)") (class "Default")
      (node (ref "IC2") (pin "B3") (pinfunction "EPHY_TXP_B3") (pintype "bidirectional"))
    )
    (net (code "357") (name "unconnected-(IC2B-HCEC-PadG5)") (class "Default")
      (node (ref "IC2") (pin "G5") (pinfunction "HCEC_G5") (pintype "bidirectional"))
    )
    (net (code "358") (name "unconnected-(IC2B-HHPD-PadM2)") (class "Default")
      (node (ref "IC2") (pin "M2") (pinfunction "HHPD_M2") (pintype "bidirectional"))
    )
    (net (code "359") (name "unconnected-(IC2B-HSCL-PadH3)") (class "Default")
      (node (ref "IC2") (pin "H3") (pinfunction "HSCL_H3") (pintype "bidirectional"))
    )
    (net (code "360") (name "unconnected-(IC2B-HSDA-PadK3)") (class "Default")
      (node (ref "IC2") (pin "K3") (pinfunction "HSDA_K3") (pintype "bidirectional"))
    )
    (net (code "361") (name "unconnected-(IC2B-HTX0N-PadF1)") (class "Default")
      (node (ref "IC2") (pin "F1") (pinfunction "HTX0N_F1") (pintype "bidirectional"))
    )
    (net (code "362") (name "unconnected-(IC2B-HTX0P-PadG1)") (class "Default")
      (node (ref "IC2") (pin "G1") (pinfunction "HTX0P_G1") (pintype "bidirectional"))
    )
    (net (code "363") (name "unconnected-(IC2B-HTX1N-PadG2)") (class "Default")
      (node (ref "IC2") (pin "G2") (pinfunction "HTX1N_G2") (pintype "bidirectional"))
    )
    (net (code "364") (name "unconnected-(IC2B-HTX1P-PadH2)") (class "Default")
      (node (ref "IC2") (pin "H2") (pinfunction "HTX1P_H2") (pintype "bidirectional"))
    )
    (net (code "365") (name "unconnected-(IC2B-HTX2N-PadJ2)") (class "Default")
      (node (ref "IC2") (pin "J2") (pinfunction "HTX2N_J2") (pintype "bidirectional"))
    )
    (net (code "366") (name "unconnected-(IC2B-HTX2P-PadJ1)") (class "Default")
      (node (ref "IC2") (pin "J1") (pinfunction "HTX2P_J1") (pintype "bidirectional"))
    )
    (net (code "367") (name "unconnected-(IC2B-HTXCN-PadE2)") (class "Default")
      (node (ref "IC2") (pin "E2") (pinfunction "HTXCN_E2") (pintype "bidirectional"))
    )
    (net (code "368") (name "unconnected-(IC2B-HTXCP-PadF2)") (class "Default")
      (node (ref "IC2") (pin "F2") (pinfunction "HTXCP_F2") (pintype "bidirectional"))
    )
    (net (code "369") (name "unconnected-(IC2B-LINEINL-PadV1)") (class "Default")
      (node (ref "IC2") (pin "V1") (pinfunction "LINEINL_V1") (pintype "bidirectional"))
    )
    (net (code "370") (name "unconnected-(IC2B-LINEINR-PadW1)") (class "Default")
      (node (ref "IC2") (pin "W1") (pinfunction "LINEINR_W1") (pintype "bidirectional"))
    )
    (net (code "371") (name "unconnected-(IC2B-LINEOUTL-PadAA3)") (class "Default")
      (node (ref "IC2") (pin "AA3") (pinfunction "LINEOUTL_AA3") (pintype "bidirectional"))
    )
    (net (code "372") (name "unconnected-(IC2B-LINEOUTR-PadY3)") (class "Default")
      (node (ref "IC2") (pin "Y3") (pinfunction "LINEOUTR_Y3") (pintype "bidirectional"))
    )
    (net (code "373") (name "unconnected-(IC2B-MBIAS-PadW3)") (class "Default")
      (node (ref "IC2") (pin "W3") (pinfunction "MBIAS_W3") (pintype "bidirectional"))
    )
    (net (code "374") (name "unconnected-(IC2B-MICIN1N-PadY1)") (class "Default")
      (node (ref "IC2") (pin "Y1") (pinfunction "MICIN1N_Y1") (pintype "bidirectional"))
    )
    (net (code "375") (name "unconnected-(IC2B-MICIN1P-PadW2)") (class "Default")
      (node (ref "IC2") (pin "W2") (pinfunction "MICIN1P_W2") (pintype "bidirectional"))
    )
    (net (code "376") (name "unconnected-(IC2B-MICIN2N-PadAA2)") (class "Default")
      (node (ref "IC2") (pin "AA2") (pinfunction "MICIN2N_AA2") (pintype "bidirectional"))
    )
    (net (code "377") (name "unconnected-(IC2B-MICIN2P-PadY2)") (class "Default")
      (node (ref "IC2") (pin "Y2") (pinfunction "MICIN2P_Y2") (pintype "bidirectional"))
    )
    (net (code "378") (name "unconnected-(IC2B-TVOUT-PadF10)") (class "Default")
      (node (ref "IC2") (pin "F10") (pinfunction "TVOUT_F10") (pintype "bidirectional"))
    )
    (net (code "379") (name "unconnected-(IC2B-VRA1-PadY4)") (class "Default")
      (node (ref "IC2") (pin "Y4") (pinfunction "VRA1_Y4") (pintype "bidirectional"))
    )
    (net (code "380") (name "unconnected-(IC2B-VRA2-PadW5)") (class "Default")
      (node (ref "IC2") (pin "W5") (pinfunction "VRA2_W5") (pintype "bidirectional"))
    )
    (net (code "381") (name "unconnected-(IC2B-VRP-PadV4)") (class "Default")
      (node (ref "IC2") (pin "V4") (pinfunction "VRP_V4") (pintype "bidirectional"))
    )
    (net (code "382") (name "unconnected-(IC2C-SDQ16-PadY17)") (class "Default")
      (node (ref "IC2") (pin "Y17") (pinfunction "SDQ16_Y17") (pintype "bidirectional"))
    )
    (net (code "383") (name "unconnected-(IC2C-SDQ17-PadAA17)") (class "Default")
      (node (ref "IC2") (pin "AA17") (pinfunction "SDQ17_AA17") (pintype "bidirectional"))
    )
    (net (code "384") (name "unconnected-(IC2C-SDQ18-PadY16)") (class "Default")
      (node (ref "IC2") (pin "Y16") (pinfunction "SDQ18_Y16") (pintype "bidirectional"))
    )
    (net (code "385") (name "unconnected-(IC2C-SDQ19-PadW15)") (class "Default")
      (node (ref "IC2") (pin "W15") (pinfunction "SDQ19_W15") (pintype "bidirectional"))
    )
    (net (code "386") (name "unconnected-(IC2C-SDQ20-PadY14)") (class "Default")
      (node (ref "IC2") (pin "Y14") (pinfunction "SDQ20_Y14") (pintype "bidirectional"))
    )
    (net (code "387") (name "unconnected-(IC2C-SDQ21-PadAA14)") (class "Default")
      (node (ref "IC2") (pin "AA14") (pinfunction "SDQ21_AA14") (pintype "bidirectional"))
    )
    (net (code "388") (name "unconnected-(IC2C-SDQ22-PadY13)") (class "Default")
      (node (ref "IC2") (pin "Y13") (pinfunction "SDQ22_Y13") (pintype "bidirectional"))
    )
    (net (code "389") (name "unconnected-(IC2C-SDQ23-PadY12)") (class "Default")
      (node (ref "IC2") (pin "Y12") (pinfunction "SDQ23_Y12") (pintype "bidirectional"))
    )
    (net (code "390") (name "unconnected-(IC2C-SDQ24-PadW12)") (class "Default")
      (node (ref "IC2") (pin "W12") (pinfunction "SDQ24_W12") (pintype "bidirectional"))
    )
    (net (code "391") (name "unconnected-(IC2C-SDQ25-PadAA11)") (class "Default")
      (node (ref "IC2") (pin "AA11") (pinfunction "SDQ25_AA11") (pintype "bidirectional"))
    )
    (net (code "392") (name "unconnected-(IC2C-SDQ26-PadY11)") (class "Default")
      (node (ref "IC2") (pin "Y11") (pinfunction "SDQ26_Y11") (pintype "bidirectional"))
    )
    (net (code "393") (name "unconnected-(IC2C-SDQ27-PadY10)") (class "Default")
      (node (ref "IC2") (pin "Y10") (pinfunction "SDQ27_Y10") (pintype "bidirectional"))
    )
    (net (code "394") (name "unconnected-(IC2C-SDQ28-PadW9)") (class "Default")
      (node (ref "IC2") (pin "W9") (pinfunction "SDQ28_W9") (pintype "bidirectional"))
    )
    (net (code "395") (name "unconnected-(IC2C-SDQ29-PadAA8)") (class "Default")
      (node (ref "IC2") (pin "AA8") (pinfunction "SDQ29_AA8") (pintype "bidirectional"))
    )
    (net (code "396") (name "unconnected-(IC2C-SDQ30-PadY8)") (class "Default")
      (node (ref "IC2") (pin "Y8") (pinfunction "SDQ30_Y8") (pintype "bidirectional"))
    )
    (net (code "397") (name "unconnected-(IC2C-SDQ31-PadY7)") (class "Default")
      (node (ref "IC2") (pin "Y7") (pinfunction "SDQ31_Y7") (pintype "bidirectional"))
    )
    (net (code "398") (name "unconnected-(IC2C-SDQM2-PadAA18)") (class "Default")
      (node (ref "IC2") (pin "AA18") (pinfunction "SDQM2_AA18") (pintype "bidirectional"))
    )
    (net (code "399") (name "unconnected-(IC2C-SDQM3-PadAA12)") (class "Default")
      (node (ref "IC2") (pin "AA12") (pinfunction "SDQM3_AA12") (pintype "bidirectional"))
    )
    (net (code "400") (name "unconnected-(IC2C-SDQS2-PadAA15)") (class "Default")
      (node (ref "IC2") (pin "AA15") (pinfunction "SDQS2_AA15") (pintype "bidirectional"))
    )
    (net (code "401") (name "unconnected-(IC2C-SDQS3-PadAA9)") (class "Default")
      (node (ref "IC2") (pin "AA9") (pinfunction "SDQS3_AA9") (pintype "bidirectional"))
    )
    (net (code "402") (name "unconnected-(IC2C-SDQSB2-PadY15)") (class "Default")
      (node (ref "IC2") (pin "Y15") (pinfunction "SDQSB2_Y15") (pintype "bidirectional"))
    )
    (net (code "403") (name "unconnected-(IC2C-SDQSB3-PadY9)") (class "Default")
      (node (ref "IC2") (pin "Y9") (pinfunction "SDQSB3_Y9") (pintype "bidirectional"))
    )
    (net (code "404") (name "unconnected-(IC2D-PC0{slash}NAND_WE{slash}SPI0_MOSI-PadC15)") (class "Default")
      (node (ref "IC2") (pin "C15") (pinfunction "PC0/NAND_WE/SPI0_MOSI_C15") (pintype "bidirectional"))
    )
    (net (code "405") (name "unconnected-(IC2D-PC1{slash}NAND_ALE{slash}SPI0_MISO-PadC16)") (class "Default")
      (node (ref "IC2") (pin "C16") (pinfunction "PC1/NAND_ALE/SPI0_MISO_C16") (pintype "bidirectional"))
    )
    (net (code "406") (name "unconnected-(IC2D-PC3{slash}NAND_CE1{slash}SPI0_CS-PadB15)") (class "Default")
      (node (ref "IC2") (pin "B15") (pinfunction "PC3/NAND_CE1/SPI0_CS_B15") (pintype "bidirectional"))
    )
    (net (code "407") (name "unconnected-(IC2D-PC4{slash}NAND_CE0-PadF16)") (class "Default")
      (node (ref "IC2") (pin "F16") (pinfunction "PC4/NAND_CE0_F16") (pintype "bidirectional"))
    )
    (net (code "408") (name "unconnected-(IC2E-PG9{slash}UART1_CTS{slash}PG_EINT9-PadE3)") (class "Default")
      (node (ref "IC2") (pin "E3") (pinfunction "PG9/UART1_CTS/PG_EINT9_E3") (pintype "bidirectional"))
    )
    (net (code "409") (name "unconnected-(IC2E-PG11{slash}PCM1_CLK{slash}PG_EINT11-PadD2)") (class "Default")
      (node (ref "IC2") (pin "D2") (pinfunction "PG11/PCM1_CLK/PG_EINT11_D2") (pintype "bidirectional"))
    )
    (net (code "410") (name "unconnected-(IC2G-JTAG_SEL0-PadA1)") (class "Default")
      (node (ref "IC2") (pin "A1") (pinfunction "JTAG_SEL0_A1") (pintype "bidirectional"))
    )
    (net (code "411") (name "unconnected-(IC2G-JTAG_SEL1-PadB2)") (class "Default")
      (node (ref "IC2") (pin "B2") (pinfunction "JTAG_SEL1_B2") (pintype "bidirectional"))
    )
    (net (code "412") (name "unconnected-(IC2G-PLLTEST-PadL5)") (class "Default")
      (node (ref "IC2") (pin "L5") (pinfunction "PLLTEST_L5") (pintype "bidirectional"))
    )
    (net (code "413") (name "unconnected-(IC2G-TEST-PadT5)") (class "Default")
      (node (ref "IC2") (pin "T5") (pinfunction "TEST_T5") (pintype "bidirectional"))
    )
    (net (code "414") (name "unconnected-(IC2G-USB_DM1-PadB7)") (class "Default")
      (node (ref "IC2") (pin "B7") (pinfunction "USB_DM1_B7") (pintype "bidirectional"))
    )
    (net (code "415") (name "unconnected-(IC2G-USB_DM2-PadA8)") (class "Default")
      (node (ref "IC2") (pin "A8") (pinfunction "USB_DM2_A8") (pintype "bidirectional"))
    )
    (net (code "416") (name "unconnected-(IC2G-USB_DM3-PadB9)") (class "Default")
      (node (ref "IC2") (pin "B9") (pinfunction "USB_DM3_B9") (pintype "bidirectional"))
    )
    (net (code "417") (name "unconnected-(IC2G-USB_DP1-PadB6)") (class "Default")
      (node (ref "IC2") (pin "B6") (pinfunction "USB_DP1_B6") (pintype "bidirectional"))
    )
    (net (code "418") (name "unconnected-(IC2G-USB_DP2-PadA7)") (class "Default")
      (node (ref "IC2") (pin "A7") (pinfunction "USB_DP2_A7") (pintype "bidirectional"))
    )
    (net (code "419") (name "unconnected-(IC2G-USB_DP3-PadB8)") (class "Default")
      (node (ref "IC2") (pin "B8") (pinfunction "USB_DP3_B8") (pintype "bidirectional"))
    )
    (net (code "420") (name "unconnected-(IC2G-X24MFOUT-PadK4)") (class "Default")
      (node (ref "IC2") (pin "K4") (pinfunction "X24MFOUT_K4") (pintype "bidirectional"))
    )
    (net (code "421") (name "unconnected-(IC2I-PL0{slash}S_TWI_SCK{slash}S_PL_EINT0-PadN1)") (class "Default")
      (node (ref "IC2") (pin "N1") (pinfunction "PL0/S_TWI_SCK/S_PL_EINT0_N1") (pintype "bidirectional"))
    )
    (net (code "422") (name "unconnected-(IC2I-PL1{slash}S_TWI_SDA{slash}S_PL_EINT1-PadM1)") (class "Default")
      (node (ref "IC2") (pin "M1") (pinfunction "PL1/S_TWI_SDA/S_PL_EINT1_M1") (pintype "bidirectional"))
    )
    (net (code "423") (name "unconnected-(IC2I-PL2{slash}S_UART_TX{slash}S_PL_EINT2-PadP2)") (class "Default")
      (node (ref "IC2") (pin "P2") (pinfunction "PL2/S_UART_TX/S_PL_EINT2_P2") (pintype "bidirectional"))
    )
    (net (code "424") (name "unconnected-(IC2I-PL3{slash}S_UART_RX{slash}S_PL_EINT3-PadR1)") (class "Default")
      (node (ref "IC2") (pin "R1") (pinfunction "PL3/S_UART_RX/S_PL_EINT3_R1") (pintype "bidirectional"))
    )
    (net (code "425") (name "unconnected-(IC2I-PL4{slash}S_JTAG_MS{slash}S_PL_EINT4-PadN2)") (class "Default")
      (node (ref "IC2") (pin "N2") (pinfunction "PL4/S_JTAG_MS/S_PL_EINT4_N2") (pintype "bidirectional"))
    )
    (net (code "426") (name "unconnected-(IC2I-PL5{slash}S_JTAG_CK{slash}S_PL_EINT5-PadR2)") (class "Default")
      (node (ref "IC2") (pin "R2") (pinfunction "PL5/S_JTAG_CK/S_PL_EINT5_R2") (pintype "bidirectional"))
    )
    (net (code "427") (name "unconnected-(IC2I-PL6{slash}S_JTAG_DO{slash}S_PL_EINT6-PadT4)") (class "Default")
      (node (ref "IC2") (pin "T4") (pinfunction "PL6/S_JTAG_DO/S_PL_EINT6_T4") (pintype "bidirectional"))
    )
    (net (code "428") (name "unconnected-(IC2I-PL8{slash}S_PL_EINT8-PadT2)") (class "Default")
      (node (ref "IC2") (pin "T2") (pinfunction "PL8/S_PL_EINT8_T2") (pintype "bidirectional"))
    )
    (net (code "429") (name "unconnected-(IC2I-PL9{slash}S_PL_EINT9-PadM6)") (class "Default")
      (node (ref "IC2") (pin "M6") (pinfunction "PL9/S_PL_EINT9_M6") (pintype "bidirectional"))
    )
    (net (code "430") (name "unconnected-(IC2I-PL10{slash}S_PWM{slash}S_PL_EINT10-PadV2)") (class "Default")
      (node (ref "IC2") (pin "V2") (pinfunction "PL10/S_PWM/S_PL_EINT10_V2") (pintype "bidirectional"))
    )
    (net (code "431") (name "unconnected-(IC2I-PL11{slash}S_CIR_RX{slash}S_PL_EINT11-PadU2)") (class "Default")
      (node (ref "IC2") (pin "U2") (pinfunction "PL11/S_CIR_RX/S_PL_EINT11_U2") (pintype "bidirectional"))
    )
    (net (code "432") (name "unconnected-(IC10-PG-Pad1)") (class "Default")
      (node (ref "IC10") (pin "1") (pinfunction "PG_1") (pintype "bidirectional"))
    )
    (net (code "433") (name "unconnected-(LED4-DOUT-Pad3)") (class "Default")
      (node (ref "LED4") (pin "3") (pinfunction "DOUT_3") (pintype "bidirectional"))
    )
    (net (code "434") (name "unconnected-(U1-BT_HOST_WAKE-Pad7)") (class "Default")
      (node (ref "U1") (pin "7") (pinfunction "BT_HOST_WAKE_7") (pintype "bidirectional"))
    )
    (net (code "435") (name "unconnected-(U1-BT_WAKE-Pad6)") (class "Default")
      (node (ref "U1") (pin "6") (pinfunction "BT_WAKE_6") (pintype "bidirectional"))
    )
    (net (code "436") (name "unconnected-(U1-FM_RX-Pad4)") (class "Default")
      (node (ref "U1") (pin "4") (pinfunction "FM_RX_4") (pintype "bidirectional"))
    )
    (net (code "437") (name "unconnected-(U1-GPIO1-Pad40)") (class "Default")
      (node (ref "U1") (pin "40") (pinfunction "GPIO1_40") (pintype "bidirectional"))
    )
    (net (code "438") (name "unconnected-(U1-GPIO2-Pad39)") (class "Default")
      (node (ref "U1") (pin "39") (pinfunction "GPIO2_39") (pintype "bidirectional"))
    )
    (net (code "439") (name "unconnected-(U1-GPIO3-Pad38)") (class "Default")
      (node (ref "U1") (pin "38") (pinfunction "GPIO3_38") (pintype "bidirectional"))
    )
    (net (code "440") (name "unconnected-(U1-GPIO4-Pad37)") (class "Default")
      (node (ref "U1") (pin "37") (pinfunction "GPIO4_37") (pintype "bidirectional"))
    )
    (net (code "441") (name "unconnected-(U1-NC1-Pad5)") (class "Default")
      (node (ref "U1") (pin "5") (pinfunction "NC1_5") (pintype "bidirectional"))
    )
    (net (code "442") (name "unconnected-(U1-NC2-Pad8)") (class "Default")
      (node (ref "U1") (pin "8") (pinfunction "NC2_8") (pintype "bidirectional"))
    )
    (net (code "443") (name "unconnected-(U1-NC3-Pad29)") (class "Default")
      (node (ref "U1") (pin "29") (pinfunction "NC3_29") (pintype "bidirectional"))
    )
    (net (code "444") (name "unconnected-(U1-NC4-Pad30)") (class "Default")
      (node (ref "U1") (pin "30") (pinfunction "NC4_30") (pintype "bidirectional"))
    )
    (net (code "445") (name "unconnected-(U1-NC5-Pad32)") (class "Default")
      (node (ref "U1") (pin "32") (pinfunction "NC5_32") (pintype "bidirectional"))
    )
    (net (code "446") (name "unconnected-(U1-NC6-Pad35)") (class "Default")
      (node (ref "U1") (pin "35") (pinfunction "NC6_35") (pintype "bidirectional"))
    )
    (net (code "447") (name "unconnected-(U1-PCM_CLK-Pad26)") (class "Default")
      (node (ref "U1") (pin "26") (pinfunction "PCM_CLK_26") (pintype "bidirectional"))
    )
    (net (code "448") (name "unconnected-(U1-PCM_IN-Pad27)") (class "Default")
      (node (ref "U1") (pin "27") (pinfunction "PCM_IN_27") (pintype "bidirectional"))
    )
    (net (code "449") (name "unconnected-(U1-PCM_OUT-Pad25)") (class "Default")
      (node (ref "U1") (pin "25") (pinfunction "PCM_OUT_25") (pintype "bidirectional"))
    )
    (net (code "450") (name "unconnected-(U1-PCM_SYNC-Pad28)") (class "Default")
      (node (ref "U1") (pin "28") (pinfunction "PCM_SYNC_28") (pintype "bidirectional"))
    )
    (net (code "451") (name "unconnected-(U1-PadTP1)") (class "Default")
      (node (ref "U1") (pin "TP1") (pinfunction "TP1_TP1") (pintype "bidirectional"))
    )
    (net (code "452") (name "unconnected-(U1-PadTP2)") (class "Default")
      (node (ref "U1") (pin "TP2") (pinfunction "TP2_TP2") (pintype "bidirectional"))
    )
    (net (code "453") (name "unconnected-(U1-PadTP3)") (class "Default")
      (node (ref "U1") (pin "TP3") (pinfunction "TP3_TP3") (pintype "bidirectional"))
    )
    (net (code "454") (name "unconnected-(U1-UART_CTS_N-Pad44)") (class "Default")
      (node (ref "U1") (pin "44") (pinfunction "UART_CTS_N_44") (pintype "bidirectional"))
    )
    (net (code "455") (name "unconnected-(U1-UART_RTS_N-Pad41)") (class "Default")
      (node (ref "U1") (pin "41") (pinfunction "UART_RTS_N_41") (pintype "bidirectional"))
    )
    (net (code "456") (name "unconnected-(U1-UART_RXD-Pad43)") (class "Default")
      (node (ref "U1") (pin "43") (pinfunction "UART_RXD_43") (pintype "bidirectional"))
    )
    (net (code "457") (name "unconnected-(U1-UART_TXD-Pad42)") (class "Default")
      (node (ref "U1") (pin "42") (pinfunction "UART_TXD_42") (pintype "bidirectional"))
    )
    (net (code "458") (name "unconnected-(U2-PC13-Pad2)") (class "Default")
      (node (ref "U2") (pin "2") (pinfunction "PC13_2") (pintype "bidirectional"))
    )
    (net (code "459") (name "unconnected-(U2-PC14{slash}OSC32_IN-Pad3)") (class "Default")
      (node (ref "U2") (pin "3") (pinfunction "PC14/OSC32_IN_3") (pintype "bidirectional"))
    )
    (net (code "460") (name "unconnected-(U2-PC15{slash}OSC32_OUT-Pad4)") (class "Default")
      (node (ref "U2") (pin "4") (pinfunction "PC15/OSC32_OUT_4") (pintype "bidirectional"))
    )
  )
)
